# design_main.net
KiCad netlist of a schematic drawn in EAGLE
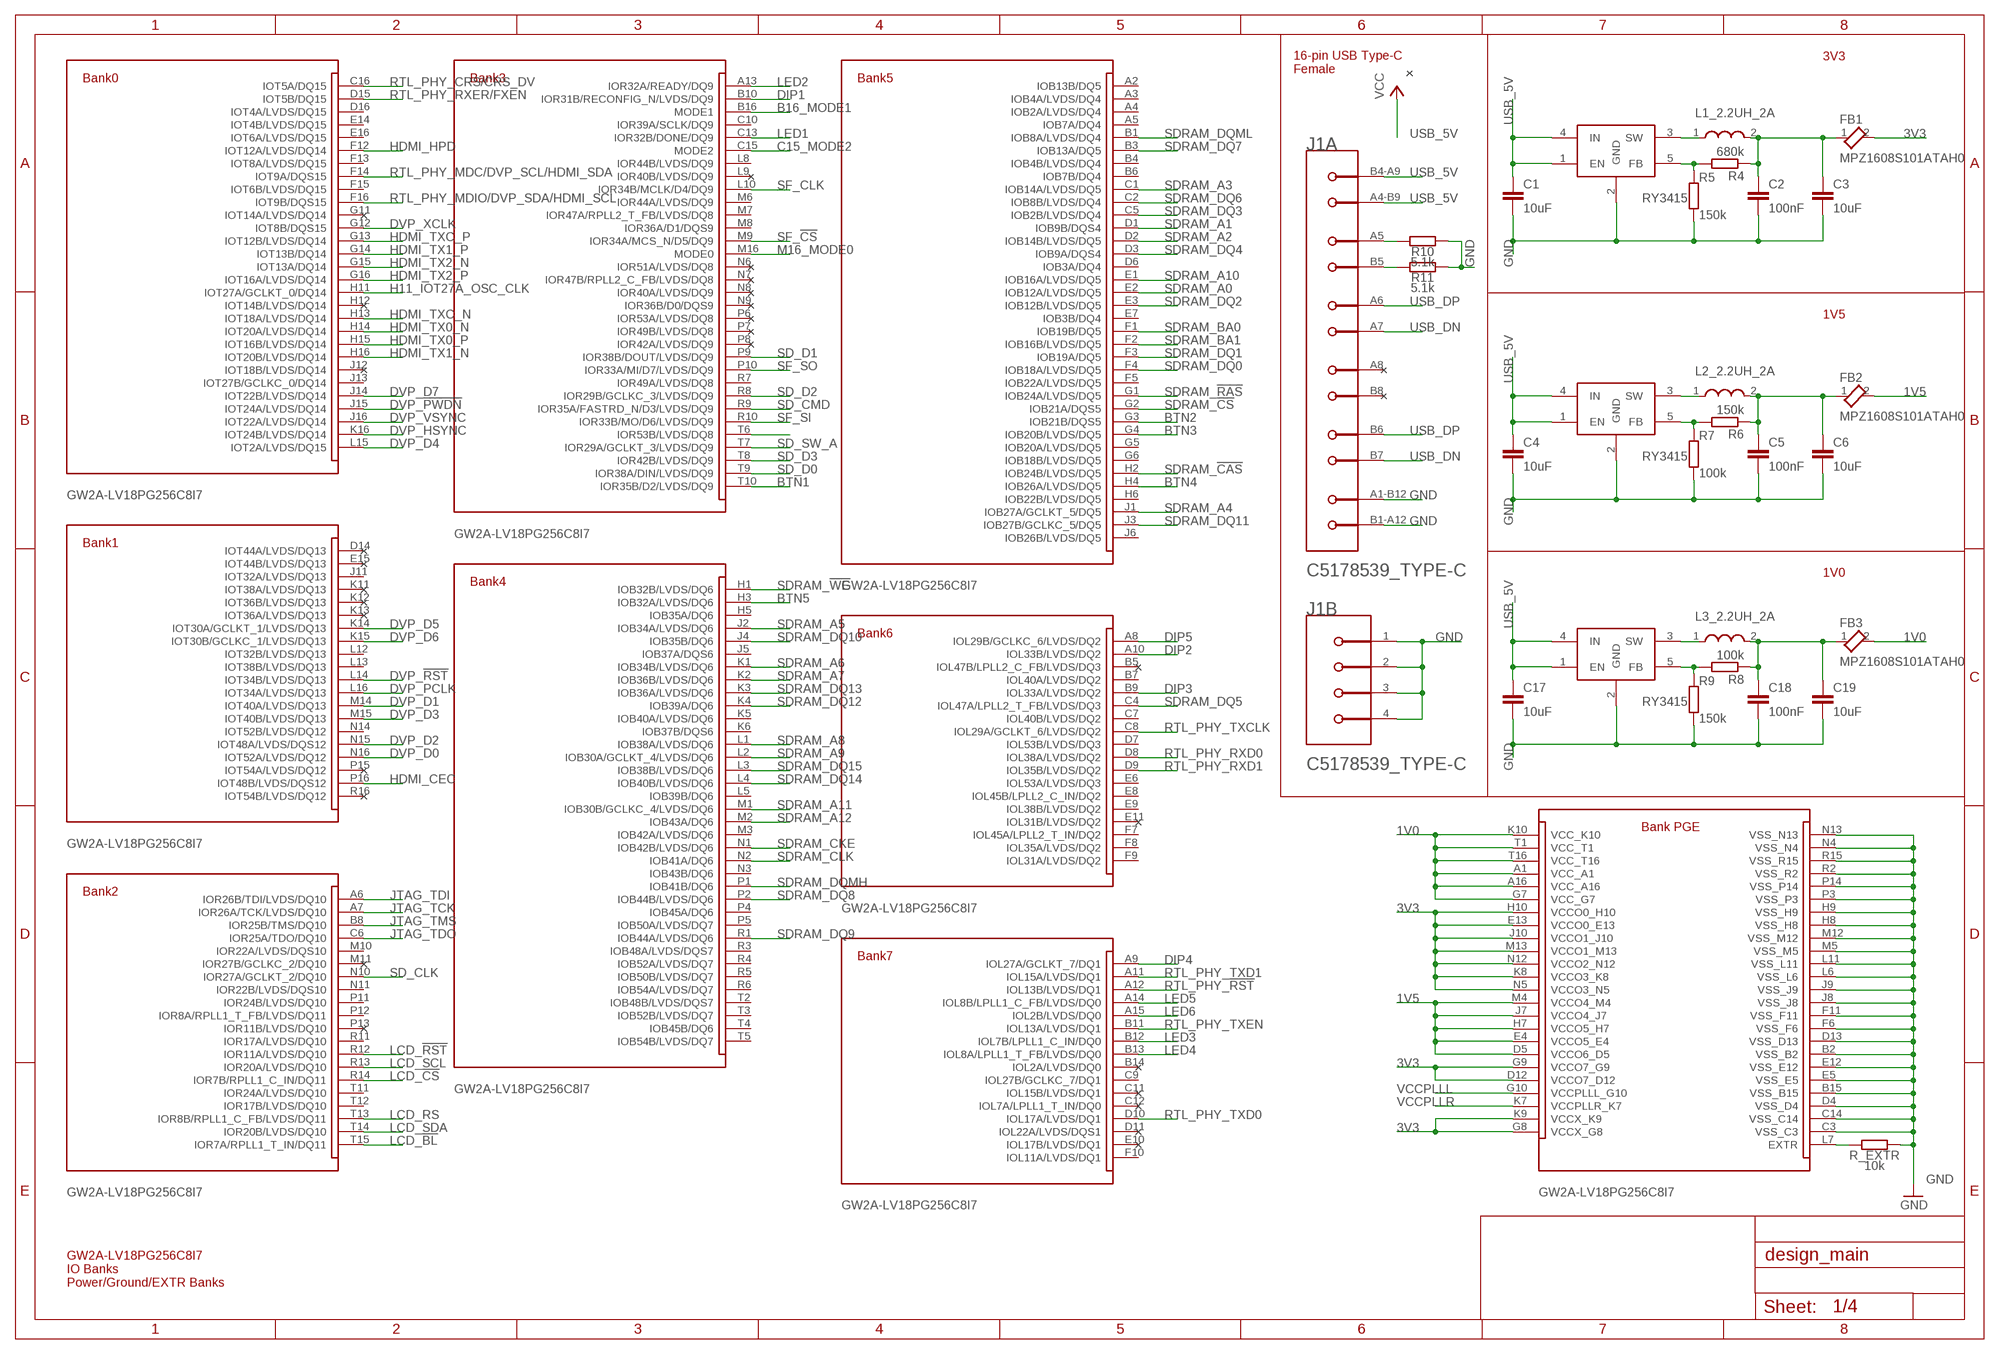
[diagram p0: schematic, sheet 1]
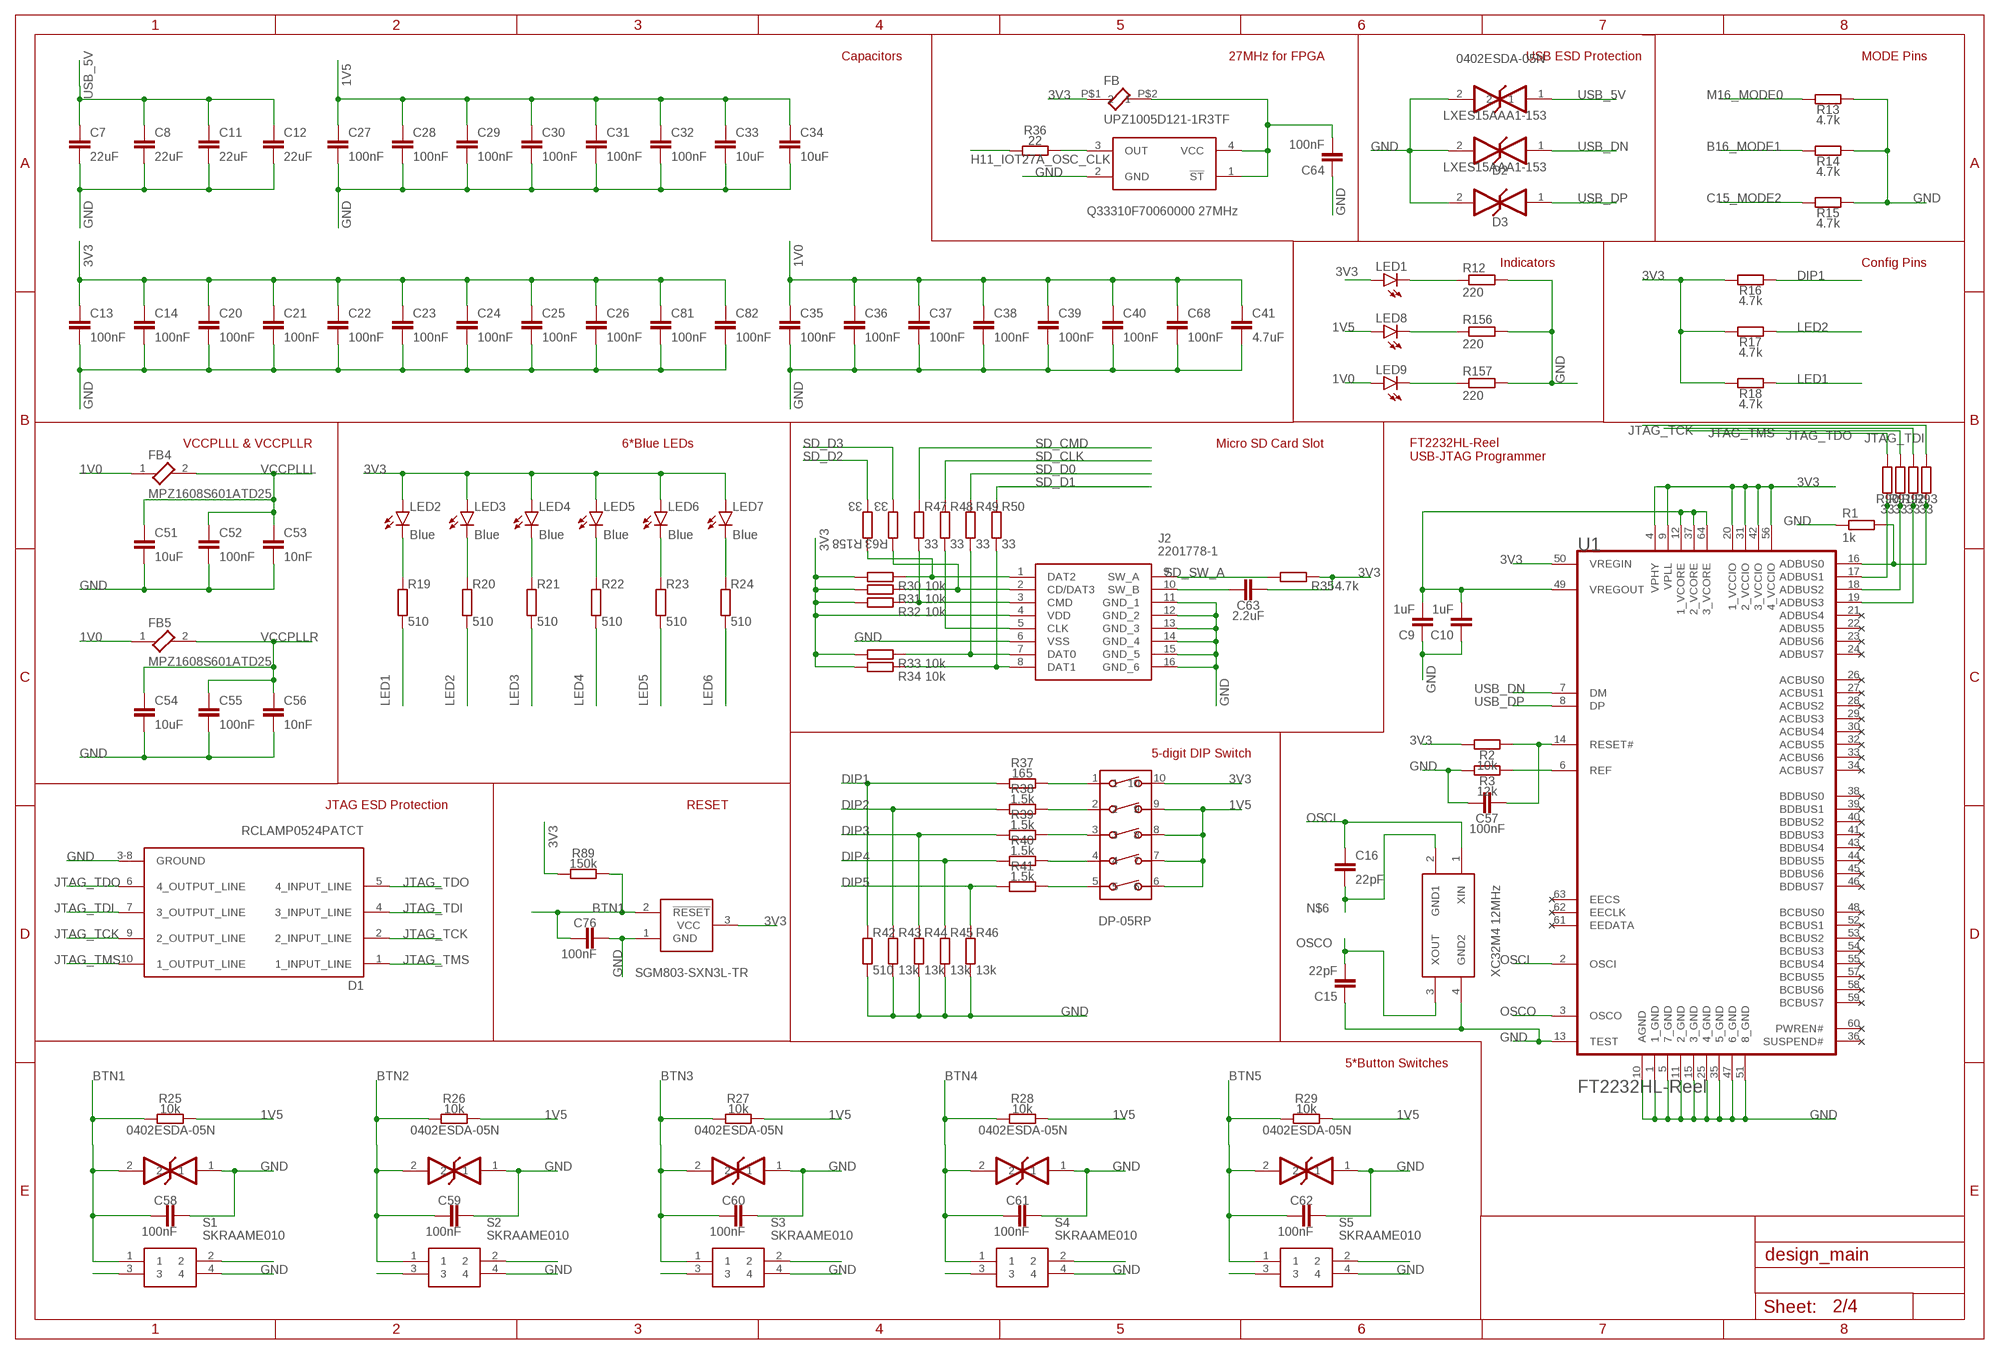
[diagram p1: schematic, sheet 2]
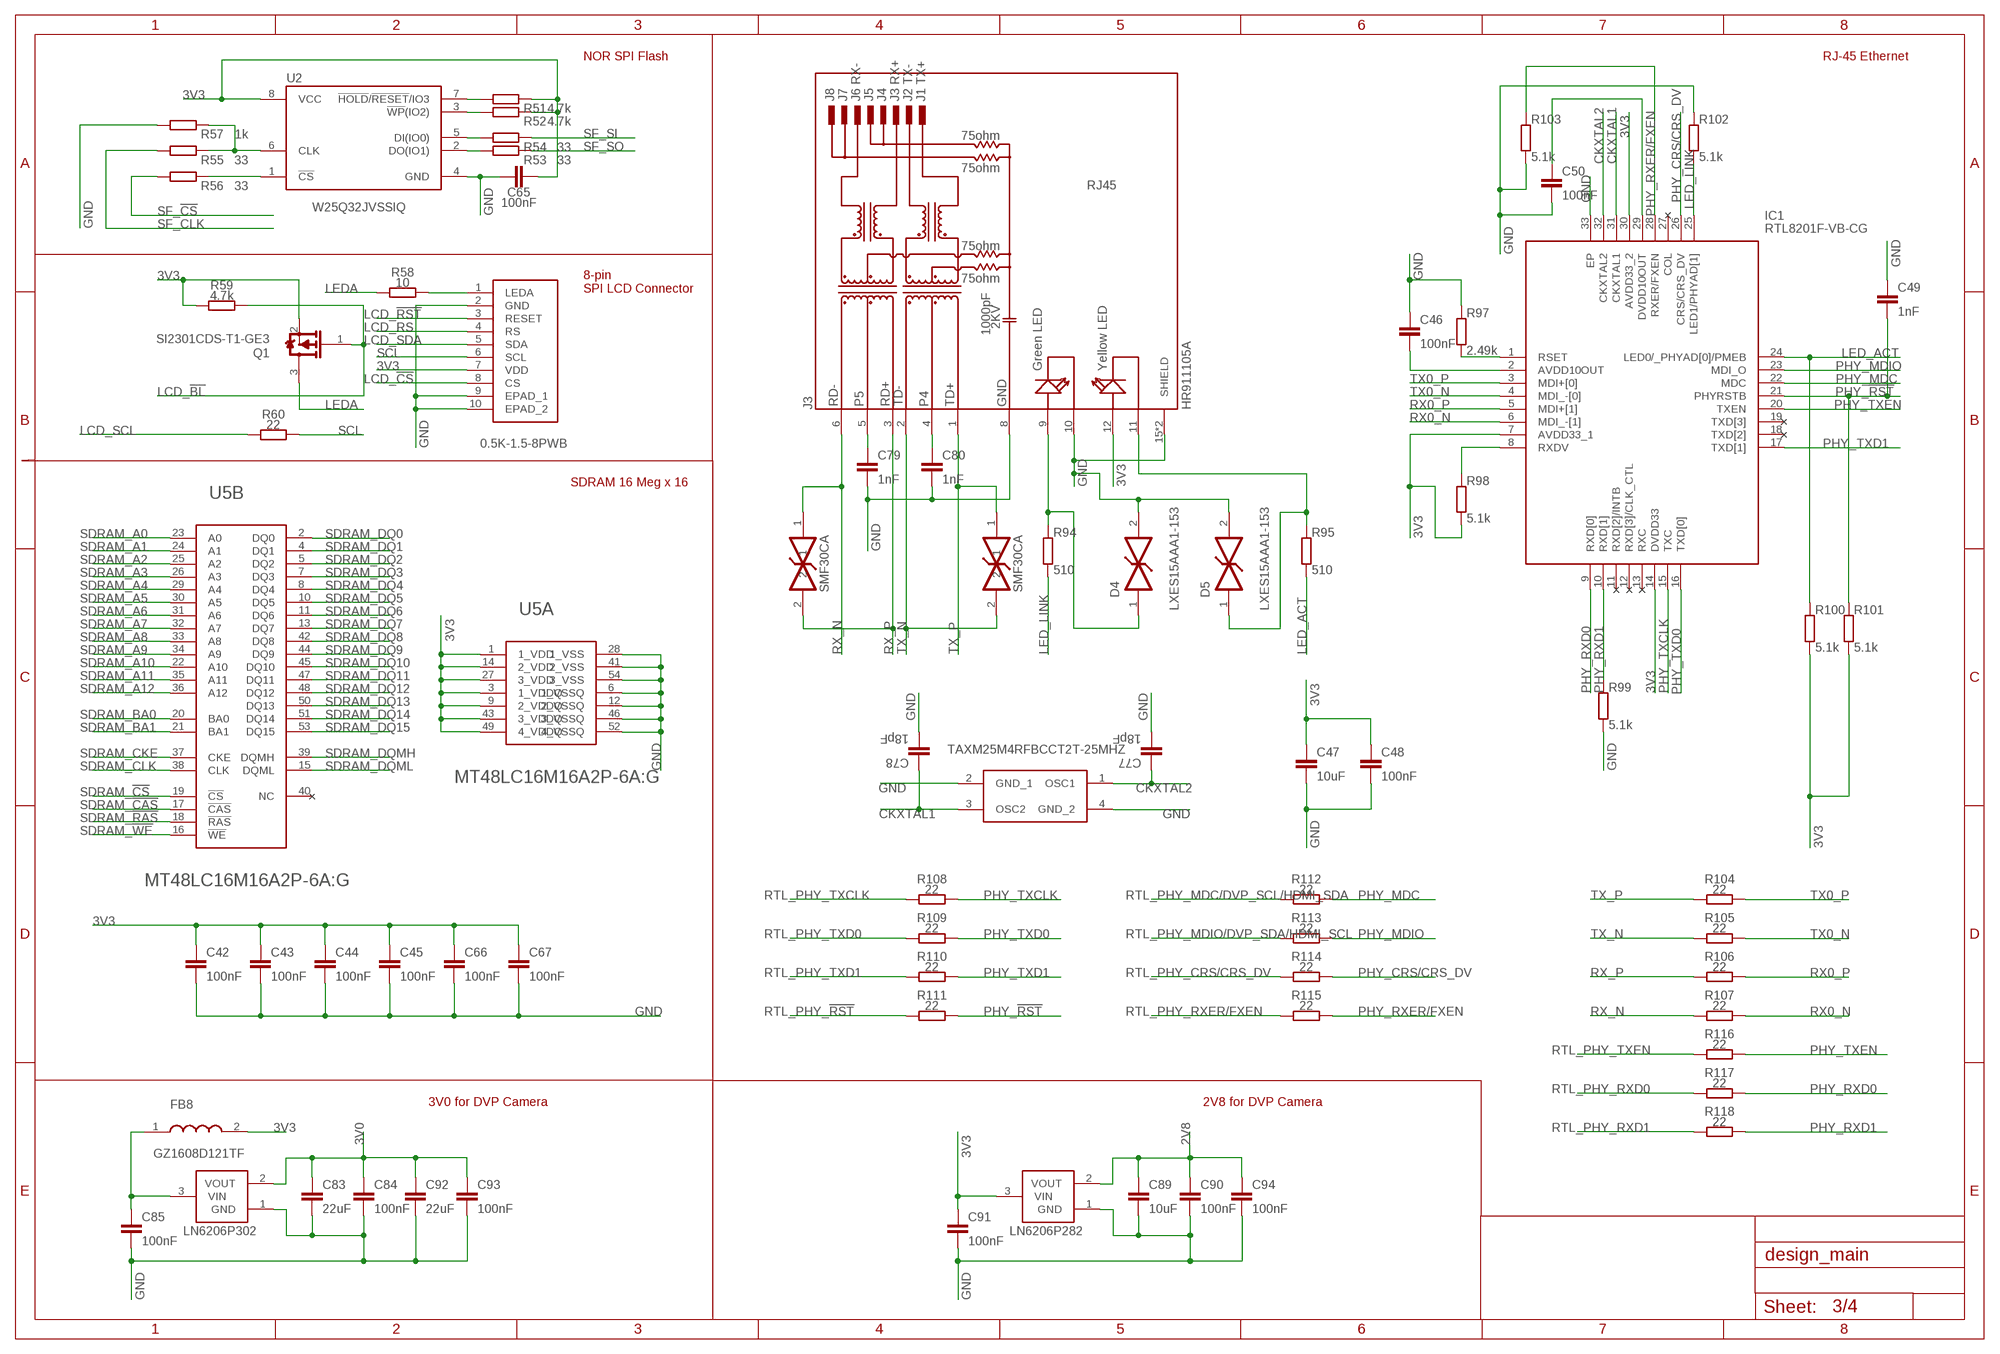
[diagram p2: schematic, sheet 3]
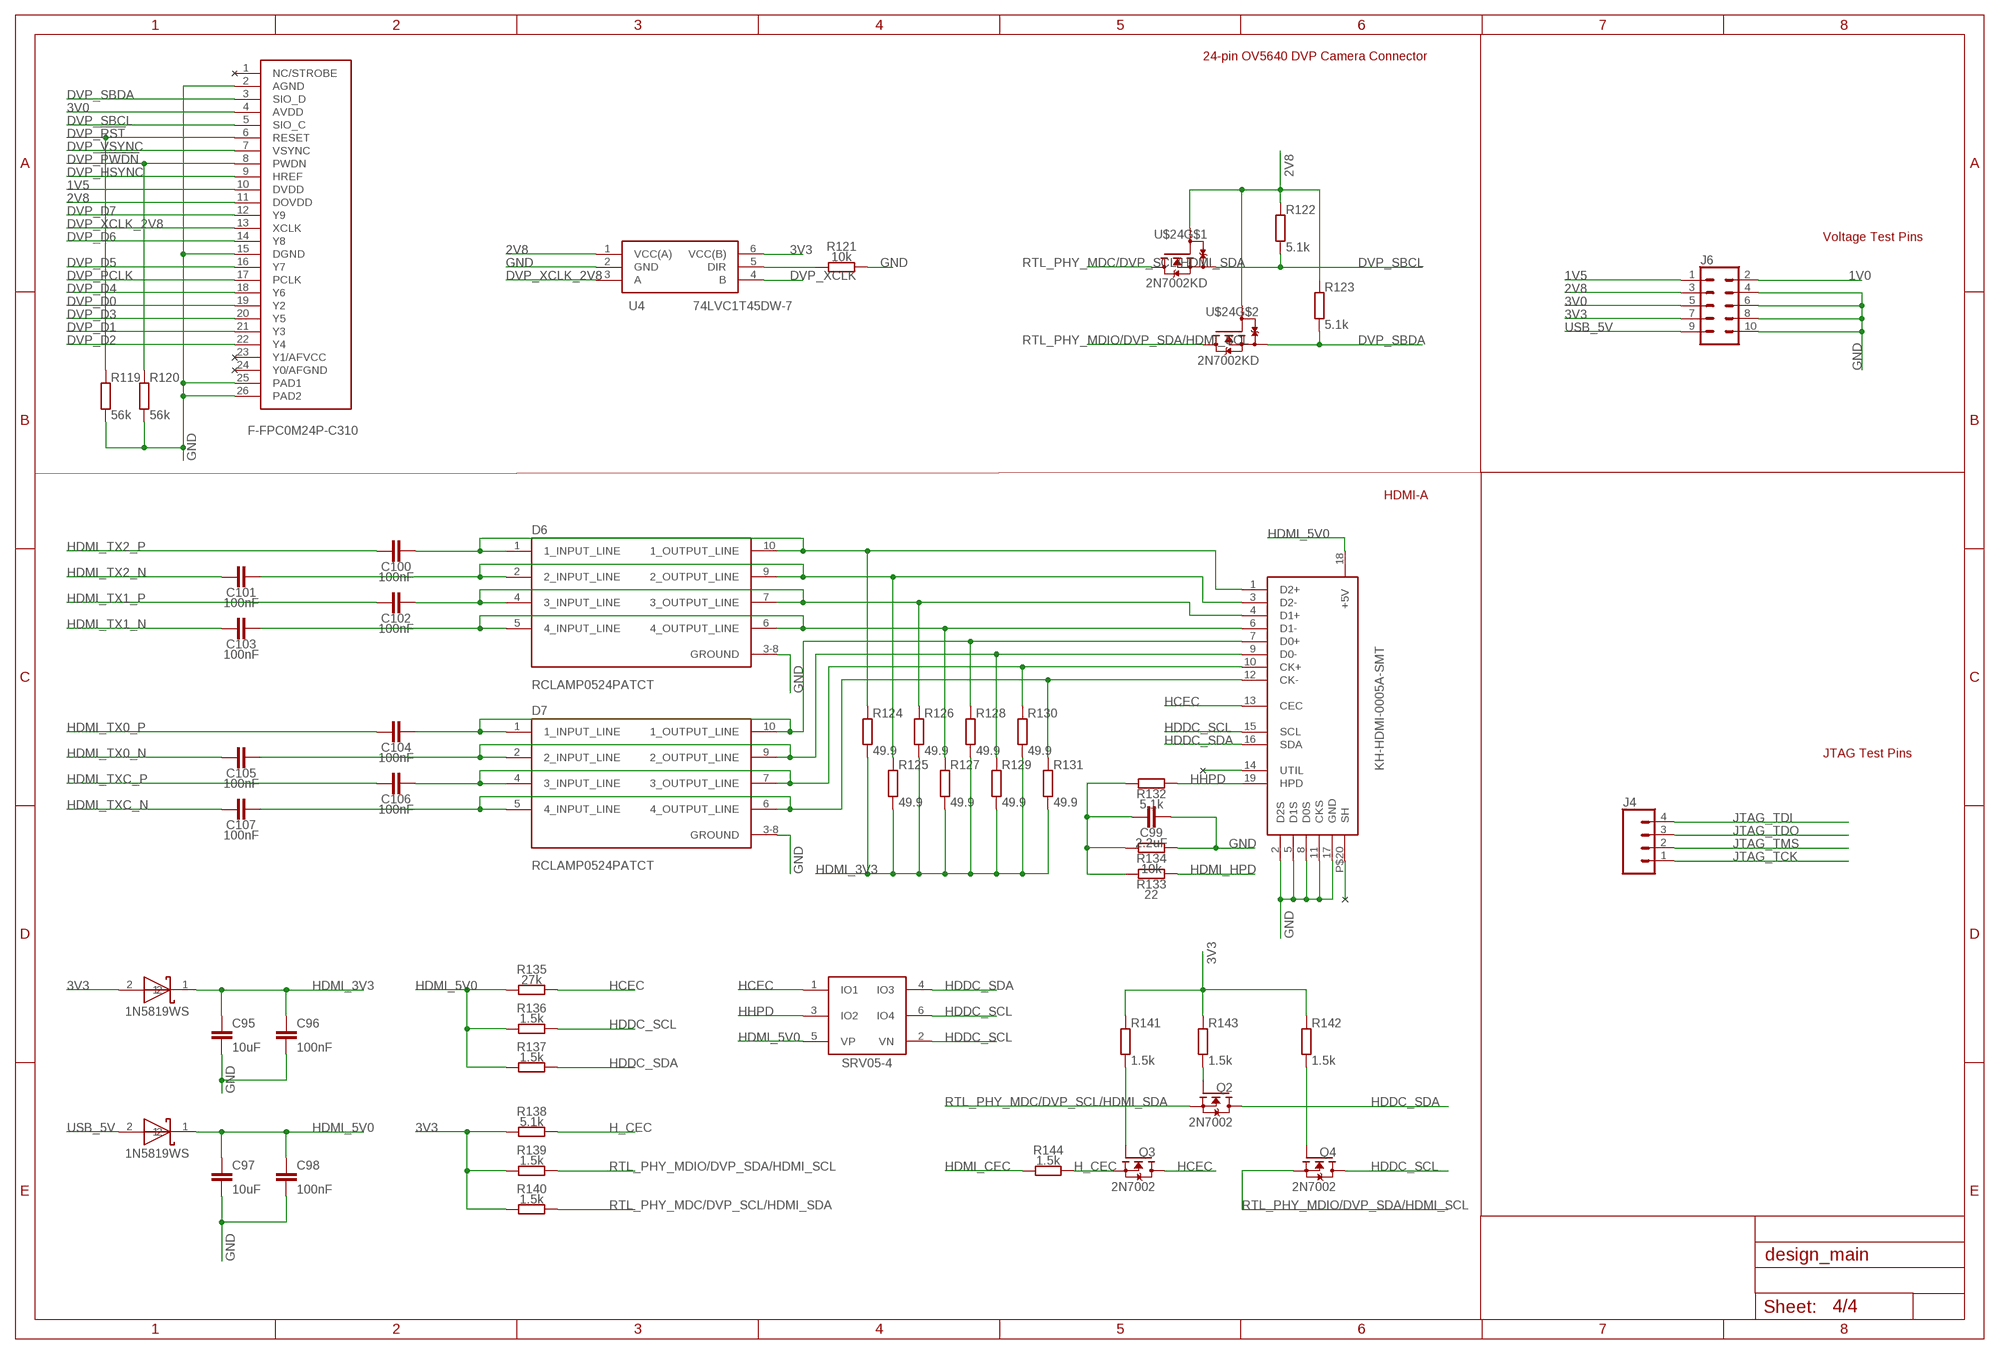
[diagram p3: schematic, sheet 4]

(export (version "E")
  (design (tool "Eeschema 10.0.6"))
  (components
    (comp (ref "C42")
      (value "100nF")
      (footprint "eagle-import:C0805")
      (libsource (lib "eagle-import") (part "C-EUC0805"))
    )
    (comp (ref "C43")
      (value "100nF")
      (footprint "eagle-import:C0805")
      (libsource (lib "eagle-import") (part "C-EUC0805"))
    )
    (comp (ref "C44")
      (value "100nF")
      (footprint "eagle-import:C0805")
      (libsource (lib "eagle-import") (part "C-EUC0805"))
    )
    (comp (ref "C45")
      (value "100nF")
      (footprint "eagle-import:C0805")
      (libsource (lib "eagle-import") (part "C-EUC0805"))
    )
    (comp (ref "C46")
      (value "100nF")
      (footprint "eagle-import:C0805")
      (libsource (lib "eagle-import") (part "C-EUC0805"))
    )
    (comp (ref "C47")
      (value "10uF")
      (footprint "eagle-import:C0805")
      (libsource (lib "eagle-import") (part "C-EUC0805"))
    )
    (comp (ref "C48")
      (value "100nF")
      (footprint "eagle-import:C0805")
      (libsource (lib "eagle-import") (part "C-EUC0805"))
    )
    (comp (ref "C49")
      (value "1nF")
      (footprint "eagle-import:C0805")
      (libsource (lib "eagle-import") (part "C-EUC0805"))
    )
    (comp (ref "C50")
      (value "100nF")
      (footprint "eagle-import:C0805")
      (libsource (lib "eagle-import") (part "C-EUC0805"))
    )
    (comp (ref "C65")
      (value "100nF")
      (footprint "eagle-import:C0805")
      (libsource (lib "eagle-import") (part "C-EUC0805"))
    )
    (comp (ref "C66")
      (value "100nF")
      (footprint "eagle-import:C0805")
      (libsource (lib "eagle-import") (part "C-EUC0805"))
    )
    (comp (ref "C67")
      (value "100nF")
      (footprint "eagle-import:C0805")
      (libsource (lib "eagle-import") (part "C-EUC0805"))
    )
    (comp (ref "C77")
      (value "18pF")
      (footprint "eagle-import:C0805")
      (libsource (lib "eagle-import") (part "C-EUC0805"))
    )
    (comp (ref "C78")
      (value "18pF")
      (footprint "eagle-import:C0805")
      (libsource (lib "eagle-import") (part "C-EUC0805"))
    )
    (comp (ref "C79")
      (value "1nF")
      (footprint "eagle-import:C0805")
      (libsource (lib "eagle-import") (part "C-EUC0805"))
    )
    (comp (ref "C80")
      (value "1nF")
      (footprint "eagle-import:C0805")
      (libsource (lib "eagle-import") (part "C-EUC0805"))
    )
    (comp (ref "C83")
      (value "22uF")
      (footprint "eagle-import:C0805")
      (libsource (lib "eagle-import") (part "C-EUC0805"))
    )
    (comp (ref "C84")
      (value "100nF")
      (footprint "eagle-import:C0805")
      (libsource (lib "eagle-import") (part "C-EUC0805"))
    )
    (comp (ref "C85")
      (value "100nF")
      (footprint "eagle-import:C0805")
      (libsource (lib "eagle-import") (part "C-EUC0805"))
    )
    (comp (ref "C89")
      (value "10uF")
      (footprint "eagle-import:C0805")
      (libsource (lib "eagle-import") (part "C-EUC0805"))
    )
    (comp (ref "C90")
      (value "100nF")
      (footprint "eagle-import:C0805")
      (libsource (lib "eagle-import") (part "C-EUC0805"))
    )
    (comp (ref "C91")
      (value "100nF")
      (footprint "eagle-import:C0805")
      (libsource (lib "eagle-import") (part "C-EUC0805"))
    )
    (comp (ref "C92")
      (value "22uF")
      (footprint "eagle-import:C0805")
      (libsource (lib "eagle-import") (part "C-EUC0805"))
    )
    (comp (ref "C93")
      (value "100nF")
      (footprint "eagle-import:C0805")
      (libsource (lib "eagle-import") (part "C-EUC0805"))
    )
    (comp (ref "C94")
      (value "100nF")
      (footprint "eagle-import:C0805")
      (libsource (lib "eagle-import") (part "C-EUC0805"))
    )
    (comp (ref "D4")
      (value "MURATA_LXES15AAA1-153MURATA_LXES15AAA1-153_0_0")
      (footprint "eagle-import:MURATA_LXES15AAA1-153_0")
      (fields
        (field (name "DIGIKEY_PART_NUMBER") "490-13210-1-ND")
        (field (name "MF") "Murata")
        (field (name "MOUSER_PART_NUMBER") "81-LXES15AAA1-153")
      )
      (libsource (lib "eagle-import") (part "MURATA_LXES15AAA1-153MURATA_LXES15AAA1-153_0_0"))
    )
    (comp (ref "D5")
      (value "MURATA_LXES15AAA1-153MURATA_LXES15AAA1-153_0_0")
      (footprint "eagle-import:MURATA_LXES15AAA1-153_0")
      (fields
        (field (name "DIGIKEY_PART_NUMBER") "490-13210-1-ND")
        (field (name "MF") "Murata")
        (field (name "MOUSER_PART_NUMBER") "81-LXES15AAA1-153")
      )
      (libsource (lib "eagle-import") (part "MURATA_LXES15AAA1-153MURATA_LXES15AAA1-153_0_0"))
    )
    (comp (ref "FB8")
      (value "SUNLORD_GZ1608D121TFSUNLORD_GZ1608D121TF_0_0")
      (footprint "eagle-import:SUNLORD_GZ1608D121TF_0")
      (fields (field (name "MF") "Sunlord") (field (name "MPN") "GZ1608D121TF"))
      (libsource (lib "eagle-import") (part "SUNLORD_GZ1608D121TFSUNLORD_GZ1608D121TF_0_0"))
    )
    (comp (ref "IC1")
      (value "RTL8201F-VB-CG")
      (footprint "eagle-import:QFN50P500X500X100-33N")
      (libsource (lib "eagle-import") (part "RTL8201F-VB-CG"))
    )
    (comp (ref "J3")
      (value "HR911105A")
      (footprint "eagle-import:HANRUN_HR911105A")
      (fields (field (name "MF") "hanrun"))
      (libsource (lib "eagle-import") (part "HR911105A"))
    )
    (comp (ref "Q1")
      (value "VISHAY_SI2301CDS-T1-GE3VISHAY_SI2301CDS-T1-GE3_0_0")
      (footprint "eagle-import:VISHAY_SI2301CDS-T1-GE3_0")
      (fields
        (field (name "DIGIKEY_PART_NUMBER") "SI2301CDS-T1-GE3CT-ND")
        (field (name "MF") "Vishay")
        (field (name "MOUSER_PART_NUMBER") "781-SI2301CDS-T1-GE3")
      )
      (libsource (lib "eagle-import") (part "VISHAY_SI2301CDS-T1-GE3VISHAY_SI2301CDS-T1-GE3_0_0"))
    )
    (comp (ref "R51")
      (value "4.7k")
      (footprint "eagle-import:R0805")
      (libsource (lib "eagle-import") (part "R-EU_R0805"))
    )
    (comp (ref "R52")
      (value "4.7k")
      (footprint "eagle-import:R0805")
      (libsource (lib "eagle-import") (part "R-EU_R0805"))
    )
    (comp (ref "R53")
      (value "33")
      (footprint "eagle-import:R0805")
      (libsource (lib "eagle-import") (part "R-EU_R0805"))
    )
    (comp (ref "R54")
      (value "33")
      (footprint "eagle-import:R0805")
      (libsource (lib "eagle-import") (part "R-EU_R0805"))
    )
    (comp (ref "R55")
      (value "33")
      (footprint "eagle-import:R0805")
      (libsource (lib "eagle-import") (part "R-EU_R0805"))
    )
    (comp (ref "R56")
      (value "33")
      (footprint "eagle-import:R0805")
      (libsource (lib "eagle-import") (part "R-EU_R0805"))
    )
    (comp (ref "R57")
      (value "1k")
      (footprint "eagle-import:R0805")
      (libsource (lib "eagle-import") (part "R-EU_R0805"))
    )
    (comp (ref "R58")
      (value "10")
      (footprint "eagle-import:R0805")
      (libsource (lib "eagle-import") (part "R-EU_R0805"))
    )
    (comp (ref "R59")
      (value "4.7k")
      (footprint "eagle-import:R0805")
      (libsource (lib "eagle-import") (part "R-EU_R0805"))
    )
    (comp (ref "R60")
      (value "22")
      (footprint "eagle-import:R0805")
      (libsource (lib "eagle-import") (part "R-EU_R0805"))
    )
    (comp (ref "R94")
      (value "510")
      (footprint "eagle-import:R0805")
      (libsource (lib "eagle-import") (part "R-EU_R0805"))
    )
    (comp (ref "R95")
      (value "510")
      (footprint "eagle-import:R0805")
      (libsource (lib "eagle-import") (part "R-EU_R0805"))
    )
    (comp (ref "R97")
      (value "2.49k")
      (footprint "eagle-import:R0805")
      (libsource (lib "eagle-import") (part "R-EU_R0805"))
    )
    (comp (ref "R98")
      (value "5.1k")
      (footprint "eagle-import:R0805")
      (libsource (lib "eagle-import") (part "R-EU_R0805"))
    )
    (comp (ref "R99")
      (value "5.1k")
      (footprint "eagle-import:R0805")
      (libsource (lib "eagle-import") (part "R-EU_R0805"))
    )
    (comp (ref "R100")
      (value "5.1k")
      (footprint "eagle-import:R0805")
      (libsource (lib "eagle-import") (part "R-EU_R0805"))
    )
    (comp (ref "R101")
      (value "5.1k")
      (footprint "eagle-import:R0805")
      (libsource (lib "eagle-import") (part "R-EU_R0805"))
    )
    (comp (ref "R102")
      (value "5.1k")
      (footprint "eagle-import:R0805")
      (libsource (lib "eagle-import") (part "R-EU_R0805"))
    )
    (comp (ref "R103")
      (value "5.1k")
      (footprint "eagle-import:R0805")
      (libsource (lib "eagle-import") (part "R-EU_R0805"))
    )
    (comp (ref "R104")
      (value "22")
      (footprint "eagle-import:R0805")
      (libsource (lib "eagle-import") (part "R-EU_R0805"))
    )
    (comp (ref "R105")
      (value "22")
      (footprint "eagle-import:R0805")
      (libsource (lib "eagle-import") (part "R-EU_R0805"))
    )
    (comp (ref "R106")
      (value "22")
      (footprint "eagle-import:R0805")
      (libsource (lib "eagle-import") (part "R-EU_R0805"))
    )
    (comp (ref "R107")
      (value "22")
      (footprint "eagle-import:R0805")
      (libsource (lib "eagle-import") (part "R-EU_R0805"))
    )
    (comp (ref "R108")
      (value "22")
      (footprint "eagle-import:R0805")
      (libsource (lib "eagle-import") (part "R-EU_R0805"))
    )
    (comp (ref "R109")
      (value "22")
      (footprint "eagle-import:R0805")
      (libsource (lib "eagle-import") (part "R-EU_R0805"))
    )
    (comp (ref "R110")
      (value "22")
      (footprint "eagle-import:R0805")
      (libsource (lib "eagle-import") (part "R-EU_R0805"))
    )
    (comp (ref "R111")
      (value "22")
      (footprint "eagle-import:R0805")
      (libsource (lib "eagle-import") (part "R-EU_R0805"))
    )
    (comp (ref "R112")
      (value "22")
      (footprint "eagle-import:R0805")
      (libsource (lib "eagle-import") (part "R-EU_R0805"))
    )
    (comp (ref "R113")
      (value "22")
      (footprint "eagle-import:R0805")
      (libsource (lib "eagle-import") (part "R-EU_R0805"))
    )
    (comp (ref "R114")
      (value "22")
      (footprint "eagle-import:R0805")
      (libsource (lib "eagle-import") (part "R-EU_R0805"))
    )
    (comp (ref "R115")
      (value "22")
      (footprint "eagle-import:R0805")
      (libsource (lib "eagle-import") (part "R-EU_R0805"))
    )
    (comp (ref "R116")
      (value "22")
      (footprint "eagle-import:R0805")
      (libsource (lib "eagle-import") (part "R-EU_R0805"))
    )
    (comp (ref "R117")
      (value "22")
      (footprint "eagle-import:R0805")
      (libsource (lib "eagle-import") (part "R-EU_R0805"))
    )
    (comp (ref "R118")
      (value "22")
      (footprint "eagle-import:R0805")
      (libsource (lib "eagle-import") (part "R-EU_R0805"))
    )
    (comp (ref "U$14")
      (value "0.5K-1.5-8PWB")
      (footprint "eagle-import:0.5K-1.5-8PWB")
      (libsource (lib "eagle-import") (part "0.5K-1.5-8PWB"))
    )
    (comp (ref "U$17")
      (value "TAXM25M4RFBCCT2T-25MHZ")
      (footprint "eagle-import:TAXM25M4RFBCCT2T-25MHZ")
      (libsource (lib "eagle-import") (part "TAXM25M4RFBCCT2T-25MHZ"))
    )
    (comp (ref "U$18")
      (value "SMF30CA")
      (footprint "eagle-import:SMF30CA")
      (libsource (lib "eagle-import") (part "SMF30CA"))
    )
    (comp (ref "U$19")
      (value "SMF30CA")
      (footprint "eagle-import:SMF30CA")
      (libsource (lib "eagle-import") (part "SMF30CA"))
    )
    (comp (ref "U$20")
      (value "LN6206P302")
      (footprint "eagle-import:LN6206P302")
      (libsource (lib "eagle-import") (part "LN6206P302"))
    )
    (comp (ref "U$22")
      (value "LN6206P282")
      (footprint "eagle-import:LN6206P282")
      (libsource (lib "eagle-import") (part "LN6206P282"))
    )
    (comp (ref "U2")
      (value "WINBOND_W25Q32JVSSIQWINBOND_W25Q32JVSSIQ_0_0")
      (footprint "eagle-import:WINBOND_W25Q32JVSSIQ_0")
      (fields
        (field (name "3DS_PART_NUMBER") "521-00004")
        (field (name "DIGIKEY_PART_NUMBER") "W25Q32JVSSIQ-ND")
        (field (name "MF") "Winbond")
      )
      (libsource (lib "eagle-import") (part "WINBOND_W25Q32JVSSIQWINBOND_W25Q32JVSSIQ_0_0"))
    )
    (comp (ref "U5")
      (value "MICRON_MT48LC16M16A2P-6A-GMICRON_MT48LC16M16A2P-6A-G_0_0")
      (footprint "eagle-import:MICRON_MT48LC16M16A2P-6A-G_0")
      (fields
        (field (name "DIGIKEY_PART_NUMBER") "MT48LC16M16A2P-6A:G-ND")
        (field (name "MF") "Micron")
        (field (name "MPN") "MT48LC16M16A2P-6A:G")
      )
      (libsource (lib "eagle-import") (part "MICRON_MT48LC16M16A2P-6A-GMICRON_MT48LC16M16A2P-6A-G_0_0"))
    )
    (comp (ref "C7")
      (value "22uF")
      (footprint "eagle-import:C0805")
      (libsource (lib "eagle-import") (part "C-EUC0805"))
    )
    (comp (ref "C8")
      (value "22uF")
      (footprint "eagle-import:C0805")
      (libsource (lib "eagle-import") (part "C-EUC0805"))
    )
    (comp (ref "C9")
      (value "1uF")
      (footprint "eagle-import:C0805")
      (libsource (lib "eagle-import") (part "C-EUC0805"))
    )
    (comp (ref "C10")
      (value "1uF")
      (footprint "eagle-import:C0805")
      (libsource (lib "eagle-import") (part "C-EUC0805"))
    )
    (comp (ref "C11")
      (value "22uF")
      (footprint "eagle-import:C0805")
      (libsource (lib "eagle-import") (part "C-EUC0805"))
    )
    (comp (ref "C12")
      (value "22uF")
      (footprint "eagle-import:C0805")
      (libsource (lib "eagle-import") (part "C-EUC0805"))
    )
    (comp (ref "C13")
      (value "100nF")
      (footprint "eagle-import:C0805")
      (libsource (lib "eagle-import") (part "C-EUC0805"))
    )
    (comp (ref "C14")
      (value "100nF")
      (footprint "eagle-import:C0805")
      (libsource (lib "eagle-import") (part "C-EUC0805"))
    )
    (comp (ref "C15")
      (value "22pF")
      (footprint "eagle-import:C0805")
      (libsource (lib "eagle-import") (part "C-EUC0805"))
    )
    (comp (ref "C16")
      (value "22pF")
      (footprint "eagle-import:C0805")
      (libsource (lib "eagle-import") (part "C-EUC0805"))
    )
    (comp (ref "C20")
      (value "100nF")
      (footprint "eagle-import:C0805")
      (libsource (lib "eagle-import") (part "C-EUC0805"))
    )
    (comp (ref "C21")
      (value "100nF")
      (footprint "eagle-import:C0805")
      (libsource (lib "eagle-import") (part "C-EUC0805"))
    )
    (comp (ref "C22")
      (value "100nF")
      (footprint "eagle-import:C0805")
      (libsource (lib "eagle-import") (part "C-EUC0805"))
    )
    (comp (ref "C23")
      (value "100nF")
      (footprint "eagle-import:C0805")
      (libsource (lib "eagle-import") (part "C-EUC0805"))
    )
    (comp (ref "C24")
      (value "100nF")
      (footprint "eagle-import:C0805")
      (libsource (lib "eagle-import") (part "C-EUC0805"))
    )
    (comp (ref "C25")
      (value "100nF")
      (footprint "eagle-import:C0805")
      (libsource (lib "eagle-import") (part "C-EUC0805"))
    )
    (comp (ref "C26")
      (value "100nF")
      (footprint "eagle-import:C0805")
      (libsource (lib "eagle-import") (part "C-EUC0805"))
    )
    (comp (ref "C27")
      (value "100nF")
      (footprint "eagle-import:C0805")
      (libsource (lib "eagle-import") (part "C-EUC0805"))
    )
    (comp (ref "C28")
      (value "100nF")
      (footprint "eagle-import:C0805")
      (libsource (lib "eagle-import") (part "C-EUC0805"))
    )
    (comp (ref "C29")
      (value "100nF")
      (footprint "eagle-import:C0805")
      (libsource (lib "eagle-import") (part "C-EUC0805"))
    )
    (comp (ref "C30")
      (value "100nF")
      (footprint "eagle-import:C0805")
      (libsource (lib "eagle-import") (part "C-EUC0805"))
    )
    (comp (ref "C31")
      (value "100nF")
      (footprint "eagle-import:C0805")
      (libsource (lib "eagle-import") (part "C-EUC0805"))
    )
    (comp (ref "C32")
      (value "100nF")
      (footprint "eagle-import:C0805")
      (libsource (lib "eagle-import") (part "C-EUC0805"))
    )
    (comp (ref "C33")
      (value "10uF")
      (footprint "eagle-import:C0805")
      (libsource (lib "eagle-import") (part "C-EUC0805"))
    )
    (comp (ref "C34")
      (value "10uF")
      (footprint "eagle-import:C0805")
      (libsource (lib "eagle-import") (part "C-EUC0805"))
    )
    (comp (ref "C35")
      (value "100nF")
      (footprint "eagle-import:C0805")
      (libsource (lib "eagle-import") (part "C-EUC0805"))
    )
    (comp (ref "C36")
      (value "100nF")
      (footprint "eagle-import:C0805")
      (libsource (lib "eagle-import") (part "C-EUC0805"))
    )
    (comp (ref "C37")
      (value "100nF")
      (footprint "eagle-import:C0805")
      (libsource (lib "eagle-import") (part "C-EUC0805"))
    )
    (comp (ref "C38")
      (value "100nF")
      (footprint "eagle-import:C0805")
      (libsource (lib "eagle-import") (part "C-EUC0805"))
    )
    (comp (ref "C39")
      (value "100nF")
      (footprint "eagle-import:C0805")
      (libsource (lib "eagle-import") (part "C-EUC0805"))
    )
    (comp (ref "C40")
      (value "100nF")
      (footprint "eagle-import:C0805")
      (libsource (lib "eagle-import") (part "C-EUC0805"))
    )
    (comp (ref "C41")
      (value "4.7uF")
      (footprint "eagle-import:C0805")
      (libsource (lib "eagle-import") (part "C-EUC0805"))
    )
    (comp (ref "C51")
      (value "10uF")
      (footprint "eagle-import:C0805")
      (libsource (lib "eagle-import") (part "C-EUC0805"))
    )
    (comp (ref "C52")
      (value "100nF")
      (footprint "eagle-import:C0805")
      (libsource (lib "eagle-import") (part "C-EUC0805"))
    )
    (comp (ref "C53")
      (value "10nF")
      (footprint "eagle-import:C0805")
      (libsource (lib "eagle-import") (part "C-EUC0805"))
    )
    (comp (ref "C54")
      (value "10uF")
      (footprint "eagle-import:C0805")
      (libsource (lib "eagle-import") (part "C-EUC0805"))
    )
    (comp (ref "C55")
      (value "100nF")
      (footprint "eagle-import:C0805")
      (libsource (lib "eagle-import") (part "C-EUC0805"))
    )
    (comp (ref "C56")
      (value "10nF")
      (footprint "eagle-import:C0805")
      (libsource (lib "eagle-import") (part "C-EUC0805"))
    )
    (comp (ref "C57")
      (value "100nF")
      (footprint "eagle-import:C0805")
      (libsource (lib "eagle-import") (part "C-EUC0805"))
    )
    (comp (ref "C58")
      (value "100nF")
      (footprint "eagle-import:C0805")
      (libsource (lib "eagle-import") (part "C-EUC0805"))
    )
    (comp (ref "C59")
      (value "100nF")
      (footprint "eagle-import:C0805")
      (libsource (lib "eagle-import") (part "C-EUC0805"))
    )
    (comp (ref "C60")
      (value "100nF")
      (footprint "eagle-import:C0805")
      (libsource (lib "eagle-import") (part "C-EUC0805"))
    )
    (comp (ref "C61")
      (value "100nF")
      (footprint "eagle-import:C0805")
      (libsource (lib "eagle-import") (part "C-EUC0805"))
    )
    (comp (ref "C62")
      (value "100nF")
      (footprint "eagle-import:C0805")
      (libsource (lib "eagle-import") (part "C-EUC0805"))
    )
    (comp (ref "C63")
      (value "2.2uF")
      (footprint "eagle-import:C0805")
      (libsource (lib "eagle-import") (part "C-EUC0805"))
    )
    (comp (ref "C64")
      (value "100nF")
      (footprint "eagle-import:C0805")
      (libsource (lib "eagle-import") (part "C-EUC0805"))
    )
    (comp (ref "C68")
      (value "100nF")
      (footprint "eagle-import:C0805")
      (libsource (lib "eagle-import") (part "C-EUC0805"))
    )
    (comp (ref "C76")
      (value "100nF")
      (footprint "eagle-import:C0805")
      (libsource (lib "eagle-import") (part "C-EUC0805"))
    )
    (comp (ref "C81")
      (value "100nF")
      (footprint "eagle-import:C0805")
      (libsource (lib "eagle-import") (part "C-EUC0805"))
    )
    (comp (ref "C82")
      (value "100nF")
      (footprint "eagle-import:C0805")
      (libsource (lib "eagle-import") (part "C-EUC0805"))
    )
    (comp (ref "D1")
      (value "SEMTECH_RCLAMP0524PATCTSEMTECH_RCLAMP0524PATCT_0_0")
      (footprint "eagle-import:SEMTECH_RCLAMP0524PATCT_0")
      (fields
        (field (name "DIGIKEY_PART_NUMBER") "RCLAMP0524PACT-ND")
        (field (name "MF") "Semtech")
        (field (name "MOUSER_PART_NUMBER") "947-RCLAMP0524PATCT")
      )
      (libsource (lib "eagle-import") (part "SEMTECH_RCLAMP0524PATCTSEMTECH_RCLAMP0524PATCT_0_0"))
    )
    (comp (ref "D2")
      (value "MURATA_LXES15AAA1-153MURATA_LXES15AAA1-153_0_0")
      (footprint "eagle-import:MURATA_LXES15AAA1-153_0")
      (fields
        (field (name "DIGIKEY_PART_NUMBER") "490-13210-1-ND")
        (field (name "MF") "Murata")
        (field (name "MOUSER_PART_NUMBER") "81-LXES15AAA1-153")
      )
      (libsource (lib "eagle-import") (part "MURATA_LXES15AAA1-153MURATA_LXES15AAA1-153_0_0"))
    )
    (comp (ref "D3")
      (value "MURATA_LXES15AAA1-153MURATA_LXES15AAA1-153_0_0")
      (footprint "eagle-import:MURATA_LXES15AAA1-153_0")
      (fields
        (field (name "DIGIKEY_PART_NUMBER") "490-13210-1-ND")
        (field (name "MF") "Murata")
        (field (name "MOUSER_PART_NUMBER") "81-LXES15AAA1-153")
      )
      (libsource (lib "eagle-import") (part "MURATA_LXES15AAA1-153MURATA_LXES15AAA1-153_0_0"))
    )
    (comp (ref "FB")
      (value "UPZ1005D121-1R3TF")
      (footprint "eagle-import:UPZ1005D121-1R3TF")
      (libsource (lib "eagle-import") (part "UPZ1005D121-1R3TF"))
    )
    (comp (ref "FB4")
      (value "TDK_MPZ1608S601ATD25TDK_MPZ1608S601ATD25_0_0")
      (footprint "eagle-import:TDK_MPZ1608S601ATD25_0")
      (fields
        (field (name "MF") "TDK")
        (field (name "MPN") "MPZ1608S601ATD25")
        (field (name "TOLERANCE") "25%")
      )
      (libsource (lib "eagle-import") (part "TDK_MPZ1608S601ATD25TDK_MPZ1608S601ATD25_0_0"))
    )
    (comp (ref "FB5")
      (value "TDK_MPZ1608S601ATD25TDK_MPZ1608S601ATD25_0_0")
      (footprint "eagle-import:TDK_MPZ1608S601ATD25_0")
      (fields
        (field (name "MF") "TDK")
        (field (name "MPN") "MPZ1608S601ATD25")
        (field (name "TOLERANCE") "25%")
      )
      (libsource (lib "eagle-import") (part "TDK_MPZ1608S601ATD25TDK_MPZ1608S601ATD25_0_0"))
    )
    (comp (ref "J2")
      (value "2201778-1")
      (footprint "eagle-import:22017781")
      (fields (field (name "MOUSER_PART_NUMBER") "571-2201778-1"))
      (libsource (lib "eagle-import") (part "2201778-1"))
    )
    (comp (ref "LED1")
      (value "LEDSML0805")
      (footprint "eagle-import:SML0805")
      (libsource (lib "eagle-import") (part "LEDSML0805"))
    )
    (comp (ref "LED2")
      (value "Blue")
      (footprint "eagle-import:SML0805")
      (libsource (lib "eagle-import") (part "LEDSML0805"))
    )
    (comp (ref "LED3")
      (value "Blue")
      (footprint "eagle-import:SML0805")
      (libsource (lib "eagle-import") (part "LEDSML0805"))
    )
    (comp (ref "LED4")
      (value "Blue")
      (footprint "eagle-import:SML0805")
      (libsource (lib "eagle-import") (part "LEDSML0805"))
    )
    (comp (ref "LED5")
      (value "Blue")
      (footprint "eagle-import:SML0805")
      (libsource (lib "eagle-import") (part "LEDSML0805"))
    )
    (comp (ref "LED6")
      (value "Blue")
      (footprint "eagle-import:SML0805")
      (libsource (lib "eagle-import") (part "LEDSML0805"))
    )
    (comp (ref "LED7")
      (value "Blue")
      (footprint "eagle-import:SML0805")
      (libsource (lib "eagle-import") (part "LEDSML0805"))
    )
    (comp (ref "LED8")
      (value "LEDSML0805")
      (footprint "eagle-import:SML0805")
      (libsource (lib "eagle-import") (part "LEDSML0805"))
    )
    (comp (ref "LED9")
      (value "LEDSML0805")
      (footprint "eagle-import:SML0805")
      (libsource (lib "eagle-import") (part "LEDSML0805"))
    )
    (comp (ref "R1")
      (value "1k")
      (footprint "eagle-import:R0805")
      (libsource (lib "eagle-import") (part "R-EU_R0805"))
    )
    (comp (ref "R2")
      (value "10k")
      (footprint "eagle-import:R0805")
      (libsource (lib "eagle-import") (part "R-EU_R0805"))
    )
    (comp (ref "R3")
      (value "12k")
      (footprint "eagle-import:R0805")
      (libsource (lib "eagle-import") (part "R-EU_R0805"))
    )
    (comp (ref "R12")
      (value "220")
      (footprint "eagle-import:R0805")
      (libsource (lib "eagle-import") (part "R-EU_R0805"))
    )
    (comp (ref "R13")
      (value "4.7k")
      (footprint "eagle-import:R0805")
      (libsource (lib "eagle-import") (part "R-EU_R0805"))
    )
    (comp (ref "R14")
      (value "4.7k")
      (footprint "eagle-import:R0805")
      (libsource (lib "eagle-import") (part "R-EU_R0805"))
    )
    (comp (ref "R15")
      (value "4.7k")
      (footprint "eagle-import:R0805")
      (libsource (lib "eagle-import") (part "R-EU_R0805"))
    )
    (comp (ref "R16")
      (value "4.7k")
      (footprint "eagle-import:R0805")
      (libsource (lib "eagle-import") (part "R-EU_R0805"))
    )
    (comp (ref "R17")
      (value "4.7k")
      (footprint "eagle-import:R0805")
      (libsource (lib "eagle-import") (part "R-EU_R0805"))
    )
    (comp (ref "R18")
      (value "4.7k")
      (footprint "eagle-import:R0805")
      (libsource (lib "eagle-import") (part "R-EU_R0805"))
    )
    (comp (ref "R19")
      (value "510")
      (footprint "eagle-import:R0805")
      (libsource (lib "eagle-import") (part "R-EU_R0805"))
    )
    (comp (ref "R20")
      (value "510")
      (footprint "eagle-import:R0805")
      (libsource (lib "eagle-import") (part "R-EU_R0805"))
    )
    (comp (ref "R21")
      (value "510")
      (footprint "eagle-import:R0805")
      (libsource (lib "eagle-import") (part "R-EU_R0805"))
    )
    (comp (ref "R22")
      (value "510")
      (footprint "eagle-import:R0805")
      (libsource (lib "eagle-import") (part "R-EU_R0805"))
    )
    (comp (ref "R23")
      (value "510")
      (footprint "eagle-import:R0805")
      (libsource (lib "eagle-import") (part "R-EU_R0805"))
    )
    (comp (ref "R24")
      (value "510")
      (footprint "eagle-import:R0805")
      (libsource (lib "eagle-import") (part "R-EU_R0805"))
    )
    (comp (ref "R25")
      (value "10k")
      (footprint "eagle-import:R0805")
      (libsource (lib "eagle-import") (part "R-EU_R0805"))
    )
    (comp (ref "R26")
      (value "10k")
      (footprint "eagle-import:R0805")
      (libsource (lib "eagle-import") (part "R-EU_R0805"))
    )
    (comp (ref "R27")
      (value "10k")
      (footprint "eagle-import:R0805")
      (libsource (lib "eagle-import") (part "R-EU_R0805"))
    )
    (comp (ref "R28")
      (value "10k")
      (footprint "eagle-import:R0805")
      (libsource (lib "eagle-import") (part "R-EU_R0805"))
    )
    (comp (ref "R29")
      (value "10k")
      (footprint "eagle-import:R0805")
      (libsource (lib "eagle-import") (part "R-EU_R0805"))
    )
    (comp (ref "R30")
      (value "10k")
      (footprint "eagle-import:R0805")
      (libsource (lib "eagle-import") (part "R-EU_R0805"))
    )
    (comp (ref "R31")
      (value "10k")
      (footprint "eagle-import:R0805")
      (libsource (lib "eagle-import") (part "R-EU_R0805"))
    )
    (comp (ref "R32")
      (value "10k")
      (footprint "eagle-import:R0805")
      (libsource (lib "eagle-import") (part "R-EU_R0805"))
    )
    (comp (ref "R33")
      (value "10k")
      (footprint "eagle-import:R0805")
      (libsource (lib "eagle-import") (part "R-EU_R0805"))
    )
    (comp (ref "R34")
      (value "10k")
      (footprint "eagle-import:R0805")
      (libsource (lib "eagle-import") (part "R-EU_R0805"))
    )
    (comp (ref "R35")
      (value "4.7k")
      (footprint "eagle-import:R0805")
      (libsource (lib "eagle-import") (part "R-EU_R0805"))
    )
    (comp (ref "R36")
      (value "22")
      (footprint "eagle-import:R0805")
      (libsource (lib "eagle-import") (part "R-EU_R0805"))
    )
    (comp (ref "R37")
      (value "165")
      (footprint "eagle-import:R0805")
      (libsource (lib "eagle-import") (part "R-EU_R0805"))
    )
    (comp (ref "R38")
      (value "1.5k")
      (footprint "eagle-import:R0805")
      (libsource (lib "eagle-import") (part "R-EU_R0805"))
    )
    (comp (ref "R39")
      (value "1.5k")
      (footprint "eagle-import:R0805")
      (libsource (lib "eagle-import") (part "R-EU_R0805"))
    )
    (comp (ref "R40")
      (value "1.5k")
      (footprint "eagle-import:R0805")
      (libsource (lib "eagle-import") (part "R-EU_R0805"))
    )
    (comp (ref "R41")
      (value "1.5k")
      (footprint "eagle-import:R0805")
      (libsource (lib "eagle-import") (part "R-EU_R0805"))
    )
    (comp (ref "R42")
      (value "510")
      (footprint "eagle-import:R0805")
      (libsource (lib "eagle-import") (part "R-EU_R0805"))
    )
    (comp (ref "R43")
      (value "13k")
      (footprint "eagle-import:R0805")
      (libsource (lib "eagle-import") (part "R-EU_R0805"))
    )
    (comp (ref "R44")
      (value "13k")
      (footprint "eagle-import:R0805")
      (libsource (lib "eagle-import") (part "R-EU_R0805"))
    )
    (comp (ref "R45")
      (value "13k")
      (footprint "eagle-import:R0805")
      (libsource (lib "eagle-import") (part "R-EU_R0805"))
    )
    (comp (ref "R46")
      (value "13k")
      (footprint "eagle-import:R0805")
      (libsource (lib "eagle-import") (part "R-EU_R0805"))
    )
    (comp (ref "R47")
      (value "33")
      (footprint "eagle-import:R0805")
      (libsource (lib "eagle-import") (part "R-EU_R0805"))
    )
    (comp (ref "R48")
      (value "33")
      (footprint "eagle-import:R0805")
      (libsource (lib "eagle-import") (part "R-EU_R0805"))
    )
    (comp (ref "R49")
      (value "33")
      (footprint "eagle-import:R0805")
      (libsource (lib "eagle-import") (part "R-EU_R0805"))
    )
    (comp (ref "R50")
      (value "33")
      (footprint "eagle-import:R0805")
      (libsource (lib "eagle-import") (part "R-EU_R0805"))
    )
    (comp (ref "R63")
      (value "33")
      (footprint "eagle-import:R0805")
      (libsource (lib "eagle-import") (part "R-EU_R0805"))
    )
    (comp (ref "R89")
      (value "150k")
      (footprint "eagle-import:R0805")
      (libsource (lib "eagle-import") (part "R-EU_R0805"))
    )
    (comp (ref "R90")
      (value "33")
      (footprint "eagle-import:R0805")
      (libsource (lib "eagle-import") (part "R-EU_R0805"))
    )
    (comp (ref "R91")
      (value "33")
      (footprint "eagle-import:R0805")
      (libsource (lib "eagle-import") (part "R-EU_R0805"))
    )
    (comp (ref "R92")
      (value "33")
      (footprint "eagle-import:R0805")
      (libsource (lib "eagle-import") (part "R-EU_R0805"))
    )
    (comp (ref "R93")
      (value "33")
      (footprint "eagle-import:R0805")
      (libsource (lib "eagle-import") (part "R-EU_R0805"))
    )
    (comp (ref "R156")
      (value "220")
      (footprint "eagle-import:R0805")
      (libsource (lib "eagle-import") (part "R-EU_R0805"))
    )
    (comp (ref "R157")
      (value "220")
      (footprint "eagle-import:R0805")
      (libsource (lib "eagle-import") (part "R-EU_R0805"))
    )
    (comp (ref "R158")
      (value "33")
      (footprint "eagle-import:R0805")
      (libsource (lib "eagle-import") (part "R-EU_R0805"))
    )
    (comp (ref "S1")
      (value "SKRAAME010")
      (footprint "eagle-import:SKRAAME010")
      (fields (field (name "MOUSER_PART_NUMBER") "688-SKRAAME010"))
      (libsource (lib "eagle-import") (part "SKRAAME010"))
    )
    (comp (ref "S2")
      (value "SKRAAME010")
      (footprint "eagle-import:SKRAAME010")
      (fields (field (name "MOUSER_PART_NUMBER") "688-SKRAAME010"))
      (libsource (lib "eagle-import") (part "SKRAAME010"))
    )
    (comp (ref "S3")
      (value "SKRAAME010")
      (footprint "eagle-import:SKRAAME010")
      (fields (field (name "MOUSER_PART_NUMBER") "688-SKRAAME010"))
      (libsource (lib "eagle-import") (part "SKRAAME010"))
    )
    (comp (ref "S4")
      (value "SKRAAME010")
      (footprint "eagle-import:SKRAAME010")
      (fields (field (name "MOUSER_PART_NUMBER") "688-SKRAAME010"))
      (libsource (lib "eagle-import") (part "SKRAAME010"))
    )
    (comp (ref "S5")
      (value "SKRAAME010")
      (footprint "eagle-import:SKRAAME010")
      (fields (field (name "MOUSER_PART_NUMBER") "688-SKRAAME010"))
      (libsource (lib "eagle-import") (part "SKRAAME010"))
    )
    (comp (ref "U$2")
      (value "XC32M4-12MHZ")
      (footprint "eagle-import:XC32M4-12MHZ")
      (libsource (lib "eagle-import") (part "XC32M4-12MHZ"))
    )
    (comp (ref "U$6")
      (value "0402ESDA-05N")
      (footprint "eagle-import:0402ESDA-05N")
      (libsource (lib "eagle-import") (part "0402ESDA-05N"))
    )
    (comp (ref "U$7")
      (value "0402ESDA-05N")
      (footprint "eagle-import:0402ESDA-05N")
      (libsource (lib "eagle-import") (part "0402ESDA-05N"))
    )
    (comp (ref "U$8")
      (value "0402ESDA-05N")
      (footprint "eagle-import:0402ESDA-05N")
      (libsource (lib "eagle-import") (part "0402ESDA-05N"))
    )
    (comp (ref "U$9")
      (value "0402ESDA-05N")
      (footprint "eagle-import:0402ESDA-05N")
      (libsource (lib "eagle-import") (part "0402ESDA-05N"))
    )
    (comp (ref "U$10")
      (value "0402ESDA-05N")
      (footprint "eagle-import:0402ESDA-05N")
      (libsource (lib "eagle-import") (part "0402ESDA-05N"))
    )
    (comp (ref "U$11")
      (value "0402ESDA-05N")
      (footprint "eagle-import:0402ESDA-05N")
      (libsource (lib "eagle-import") (part "0402ESDA-05N"))
    )
    (comp (ref "U$13")
      (value "DP-05RP")
      (footprint "eagle-import:DP-05RP")
      (libsource (lib "eagle-import") (part "DP-05RP"))
    )
    (comp (ref "U$15")
      (value "Q33310F70060000-27MHZ")
      (footprint "eagle-import:Q33310F70060000-27MHZ")
      (libsource (lib "eagle-import") (part "Q33310F70060000-27MHZ"))
    )
    (comp (ref "U$16")
      (value "SGM803-SXN3L-TR")
      (footprint "eagle-import:SGM803-SXN3L-TR")
      (libsource (lib "eagle-import") (part "SGM803-SXN3L-TR"))
    )
    (comp (ref "U1")
      (value "FTDI_FT2232HL-REELFTDI_FT2232HL-REEL_0_0")
      (footprint "eagle-import:FTDI_FT2232HL-REEL_0")
      (fields (field (name "MF") "FTDI") (field (name "MPN") "FT2232HL-Reel"))
      (libsource (lib "eagle-import") (part "FTDI_FT2232HL-REELFTDI_FT2232HL-REEL_0_0"))
    )
    (comp (ref "C95")
      (value "10uF")
      (footprint "eagle-import:C0805")
      (libsource (lib "eagle-import") (part "C-EUC0805"))
    )
    (comp (ref "C96")
      (value "100nF")
      (footprint "eagle-import:C0805")
      (libsource (lib "eagle-import") (part "C-EUC0805"))
    )
    (comp (ref "C97")
      (value "10uF")
      (footprint "eagle-import:C0805")
      (libsource (lib "eagle-import") (part "C-EUC0805"))
    )
    (comp (ref "C98")
      (value "100nF")
      (footprint "eagle-import:C0805")
      (libsource (lib "eagle-import") (part "C-EUC0805"))
    )
    (comp (ref "C99")
      (value "2.2uF")
      (footprint "eagle-import:C0805")
      (libsource (lib "eagle-import") (part "C-EUC0805"))
    )
    (comp (ref "C100")
      (value "100nF")
      (footprint "eagle-import:C0805")
      (libsource (lib "eagle-import") (part "C-EUC0805"))
    )
    (comp (ref "C101")
      (value "100nF")
      (footprint "eagle-import:C0805")
      (libsource (lib "eagle-import") (part "C-EUC0805"))
    )
    (comp (ref "C102")
      (value "100nF")
      (footprint "eagle-import:C0805")
      (libsource (lib "eagle-import") (part "C-EUC0805"))
    )
    (comp (ref "C103")
      (value "100nF")
      (footprint "eagle-import:C0805")
      (libsource (lib "eagle-import") (part "C-EUC0805"))
    )
    (comp (ref "C104")
      (value "100nF")
      (footprint "eagle-import:C0805")
      (libsource (lib "eagle-import") (part "C-EUC0805"))
    )
    (comp (ref "C105")
      (value "100nF")
      (footprint "eagle-import:C0805")
      (libsource (lib "eagle-import") (part "C-EUC0805"))
    )
    (comp (ref "C106")
      (value "100nF")
      (footprint "eagle-import:C0805")
      (libsource (lib "eagle-import") (part "C-EUC0805"))
    )
    (comp (ref "C107")
      (value "100nF")
      (footprint "eagle-import:C0805")
      (libsource (lib "eagle-import") (part "C-EUC0805"))
    )
    (comp (ref "D6")
      (value "SEMTECH_RCLAMP0524PATCTSEMTECH_RCLAMP0524PATCT_0_0")
      (footprint "eagle-import:SEMTECH_RCLAMP0524PATCT_0")
      (fields
        (field (name "DIGIKEY_PART_NUMBER") "RCLAMP0524PACT-ND")
        (field (name "MF") "Semtech")
        (field (name "MOUSER_PART_NUMBER") "947-RCLAMP0524PATCT")
      )
      (libsource (lib "eagle-import") (part "SEMTECH_RCLAMP0524PATCTSEMTECH_RCLAMP0524PATCT_0_0"))
    )
    (comp (ref "D7")
      (value "SEMTECH_RCLAMP0524PATCTSEMTECH_RCLAMP0524PATCT_0_0")
      (footprint "eagle-import:SEMTECH_RCLAMP0524PATCT_0")
      (fields
        (field (name "DIGIKEY_PART_NUMBER") "RCLAMP0524PACT-ND")
        (field (name "MF") "Semtech")
        (field (name "MOUSER_PART_NUMBER") "947-RCLAMP0524PATCT")
      )
      (libsource (lib "eagle-import") (part "SEMTECH_RCLAMP0524PATCTSEMTECH_RCLAMP0524PATCT_0_0"))
    )
    (comp (ref "J4")
      (value "CONN_04PTH")
      (footprint "eagle-import:1X04")
      (libsource (lib "eagle-import") (part "CONN_04PTH"))
    )
    (comp (ref "J6")
      (value "CONN_05X2PTH")
      (footprint "eagle-import:2X5")
      (libsource (lib "eagle-import") (part "CONN_05X2PTH"))
    )
    (comp (ref "Q2")
      (value "2N7002")
      (footprint "eagle-import:SOT95P240X111-3N")
      (fields (field (name "MF") "Diotec Semiconductor"))
      (libsource (lib "eagle-import") (part "2N7002"))
    )
    (comp (ref "Q3")
      (value "2N7002")
      (footprint "eagle-import:SOT95P240X111-3N")
      (fields (field (name "MF") "Diotec Semiconductor"))
      (libsource (lib "eagle-import") (part "2N7002"))
    )
    (comp (ref "Q4")
      (value "2N7002")
      (footprint "eagle-import:SOT95P240X111-3N")
      (fields (field (name "MF") "Diotec Semiconductor"))
      (libsource (lib "eagle-import") (part "2N7002"))
    )
    (comp (ref "R119")
      (value "56k")
      (footprint "eagle-import:R0805")
      (libsource (lib "eagle-import") (part "R-EU_R0805"))
    )
    (comp (ref "R120")
      (value "56k")
      (footprint "eagle-import:R0805")
      (libsource (lib "eagle-import") (part "R-EU_R0805"))
    )
    (comp (ref "R121")
      (value "10k")
      (footprint "eagle-import:R0805")
      (libsource (lib "eagle-import") (part "R-EU_R0805"))
    )
    (comp (ref "R122")
      (value "5.1k")
      (footprint "eagle-import:R0805")
      (libsource (lib "eagle-import") (part "R-EU_R0805"))
    )
    (comp (ref "R123")
      (value "5.1k")
      (footprint "eagle-import:R0805")
      (libsource (lib "eagle-import") (part "R-EU_R0805"))
    )
    (comp (ref "R124")
      (value "49.9")
      (footprint "eagle-import:R0805")
      (libsource (lib "eagle-import") (part "R-EU_R0805"))
    )
    (comp (ref "R125")
      (value "49.9")
      (footprint "eagle-import:R0805")
      (libsource (lib "eagle-import") (part "R-EU_R0805"))
    )
    (comp (ref "R126")
      (value "49.9")
      (footprint "eagle-import:R0805")
      (libsource (lib "eagle-import") (part "R-EU_R0805"))
    )
    (comp (ref "R127")
      (value "49.9")
      (footprint "eagle-import:R0805")
      (libsource (lib "eagle-import") (part "R-EU_R0805"))
    )
    (comp (ref "R128")
      (value "49.9")
      (footprint "eagle-import:R0805")
      (libsource (lib "eagle-import") (part "R-EU_R0805"))
    )
    (comp (ref "R129")
      (value "49.9")
      (footprint "eagle-import:R0805")
      (libsource (lib "eagle-import") (part "R-EU_R0805"))
    )
    (comp (ref "R130")
      (value "49.9")
      (footprint "eagle-import:R0805")
      (libsource (lib "eagle-import") (part "R-EU_R0805"))
    )
    (comp (ref "R131")
      (value "49.9")
      (footprint "eagle-import:R0805")
      (libsource (lib "eagle-import") (part "R-EU_R0805"))
    )
    (comp (ref "R132")
      (value "5.1k")
      (footprint "eagle-import:R0805")
      (libsource (lib "eagle-import") (part "R-EU_R0805"))
    )
    (comp (ref "R133")
      (value "22")
      (footprint "eagle-import:R0805")
      (libsource (lib "eagle-import") (part "R-EU_R0805"))
    )
    (comp (ref "R134")
      (value "10k")
      (footprint "eagle-import:R0805")
      (libsource (lib "eagle-import") (part "R-EU_R0805"))
    )
    (comp (ref "R135")
      (value "27k")
      (footprint "eagle-import:R0805")
      (libsource (lib "eagle-import") (part "R-EU_R0805"))
    )
    (comp (ref "R136")
      (value "1.5k")
      (footprint "eagle-import:R0805")
      (libsource (lib "eagle-import") (part "R-EU_R0805"))
    )
    (comp (ref "R137")
      (value "1.5k")
      (footprint "eagle-import:R0805")
      (libsource (lib "eagle-import") (part "R-EU_R0805"))
    )
    (comp (ref "R138")
      (value "5.1k")
      (footprint "eagle-import:R0805")
      (libsource (lib "eagle-import") (part "R-EU_R0805"))
    )
    (comp (ref "R139")
      (value "1.5k")
      (footprint "eagle-import:R0805")
      (libsource (lib "eagle-import") (part "R-EU_R0805"))
    )
    (comp (ref "R140")
      (value "1.5k")
      (footprint "eagle-import:R0805")
      (libsource (lib "eagle-import") (part "R-EU_R0805"))
    )
    (comp (ref "R141")
      (value "1.5k")
      (footprint "eagle-import:R0805")
      (libsource (lib "eagle-import") (part "R-EU_R0805"))
    )
    (comp (ref "R142")
      (value "1.5k")
      (footprint "eagle-import:R0805")
      (libsource (lib "eagle-import") (part "R-EU_R0805"))
    )
    (comp (ref "R143")
      (value "1.5k")
      (footprint "eagle-import:R0805")
      (libsource (lib "eagle-import") (part "R-EU_R0805"))
    )
    (comp (ref "R144")
      (value "1.5k")
      (footprint "eagle-import:R0805")
      (libsource (lib "eagle-import") (part "R-EU_R0805"))
    )
    (comp (ref "U$23")
      (value "F-FPC0M24P-C310")
      (footprint "eagle-import:F-FPC0M24P-C310")
      (libsource (lib "eagle-import") (part "F-FPC0M24P-C310"))
    )
    (comp (ref "U$24")
      (value "2N7002KD")
      (footprint "eagle-import:2N7002KD")
      (libsource (lib "eagle-import") (part "2N7002KD"))
    )
    (comp (ref "U$25")
      (value "1N5819WS")
      (footprint "eagle-import:1N5819WS")
      (libsource (lib "eagle-import") (part "1N5819WS"))
    )
    (comp (ref "U$26")
      (value "1N5819WS")
      (footprint "eagle-import:1N5819WS")
      (libsource (lib "eagle-import") (part "1N5819WS"))
    )
    (comp (ref "U$27")
      (value "KH-HDMI-0005A-SMT")
      (footprint "eagle-import:KH-HDMI-0005A-SMT")
      (libsource (lib "eagle-import") (part "KH-HDMI-0005A-SMT"))
    )
    (comp (ref "U$28")
      (value "SRV05-4")
      (footprint "eagle-import:SRV05-4")
      (libsource (lib "eagle-import") (part "SRV05-4"))
    )
    (comp (ref "U4")
      (value "74LVC1T45DW-7")
      (footprint "eagle-import:SOT65P210X110-6N")
      (fields (field (name "MOUSER_PART_NUMBER") "621-74LVC1T45DW-7"))
      (libsource (lib "eagle-import") (part "74LVC1T45DW-7"))
    )
    (comp (ref "C1")
      (value "10uF")
      (footprint "eagle-import:C0805")
      (libsource (lib "eagle-import") (part "C-EUC0805"))
    )
    (comp (ref "C2")
      (value "100nF")
      (footprint "eagle-import:C0805")
      (libsource (lib "eagle-import") (part "C-EUC0805"))
    )
    (comp (ref "C3")
      (value "10uF")
      (footprint "eagle-import:C0805")
      (libsource (lib "eagle-import") (part "C-EUC0805"))
    )
    (comp (ref "C4")
      (value "10uF")
      (footprint "eagle-import:C0805")
      (libsource (lib "eagle-import") (part "C-EUC0805"))
    )
    (comp (ref "C5")
      (value "100nF")
      (footprint "eagle-import:C0805")
      (libsource (lib "eagle-import") (part "C-EUC0805"))
    )
    (comp (ref "C6")
      (value "10uF")
      (footprint "eagle-import:C0805")
      (libsource (lib "eagle-import") (part "C-EUC0805"))
    )
    (comp (ref "C17")
      (value "10uF")
      (footprint "eagle-import:C0805")
      (libsource (lib "eagle-import") (part "C-EUC0805"))
    )
    (comp (ref "C18")
      (value "100nF")
      (footprint "eagle-import:C0805")
      (libsource (lib "eagle-import") (part "C-EUC0805"))
    )
    (comp (ref "C19")
      (value "10uF")
      (footprint "eagle-import:C0805")
      (libsource (lib "eagle-import") (part "C-EUC0805"))
    )
    (comp (ref "FB1")
      (value "TDK_MPZ1608S101ATAH0TDK_MPZ1608S101ATAH0_0_0")
      (footprint "eagle-import:TDK_MPZ1608S101ATAH0_0")
      (fields
        (field (name "DIGIKEY_PART_NUMBER") "445-1564-1-ND")
        (field (name "MF") "TDK")
        (field (name "MOUSER_PART_NUMBER") "810-MPZ1608S101ATAH0")
      )
      (libsource (lib "eagle-import") (part "TDK_MPZ1608S101ATAH0TDK_MPZ1608S101ATAH0_0_0"))
    )
    (comp (ref "FB2")
      (value "TDK_MPZ1608S101ATAH0TDK_MPZ1608S101ATAH0_0_0")
      (footprint "eagle-import:TDK_MPZ1608S101ATAH0_0")
      (fields
        (field (name "DIGIKEY_PART_NUMBER") "445-1564-1-ND")
        (field (name "MF") "TDK")
        (field (name "MOUSER_PART_NUMBER") "810-MPZ1608S101ATAH0")
      )
      (libsource (lib "eagle-import") (part "TDK_MPZ1608S101ATAH0TDK_MPZ1608S101ATAH0_0_0"))
    )
    (comp (ref "FB3")
      (value "TDK_MPZ1608S101ATAH0TDK_MPZ1608S101ATAH0_0_0")
      (footprint "eagle-import:TDK_MPZ1608S101ATAH0_0")
      (fields
        (field (name "DIGIKEY_PART_NUMBER") "445-1564-1-ND")
        (field (name "MF") "TDK")
        (field (name "MOUSER_PART_NUMBER") "810-MPZ1608S101ATAH0")
      )
      (libsource (lib "eagle-import") (part "TDK_MPZ1608S101ATAH0TDK_MPZ1608S101ATAH0_0_0"))
    )
    (comp (ref "J1")
      (value "C5178539_TYPE-CMOLEX_217179-0001_0_0")
      (footprint "eagle-import:C5178539_TYPE-C")
      (fields
        (field (name "DIGIKEY_PART_NUMBER") "900-2171790001CT-ND")
        (field (name "MF") "Molex")
        (field (name "MOUSER_PART_NUMBER") "538-217179-0001")
      )
      (libsource (lib "eagle-import") (part "C5178539_TYPE-CMOLEX_217179-0001_0_0"))
    )
    (comp (ref "L1_2.2UH_2A")
      (value "L_0805TDK_MLZ2012N6R8LT000_0_0")
      (footprint "eagle-import:TDK_MLZ2012N6R8LT000_0")
      (fields
        (field (name "MF") "TDK")
        (field (name "MPN") "MLZ2012N6R8LT000")
        (field (name "TOLERANCE") "20%")
      )
      (libsource (lib "eagle-import") (part "L_0805TDK_MLZ2012N6R8LT000_0_0"))
    )
    (comp (ref "L2_2.2UH_2A")
      (value "2.2uH 2A")
      (footprint "eagle-import:TDK_MLZ2012N6R8LT000_0")
      (fields
        (field (name "MF") "TDK")
        (field (name "MPN") "MLZ2012N6R8LT000")
        (field (name "TOLERANCE") "20%")
      )
      (libsource (lib "eagle-import") (part "L_0805TDK_MLZ2012N6R8LT000_0_0"))
    )
    (comp (ref "L3_2.2UH_2A")
      (value "2.2uH 2A")
      (footprint "eagle-import:TDK_MLZ2012N6R8LT000_0")
      (fields
        (field (name "MF") "TDK")
        (field (name "MPN") "MLZ2012N6R8LT000")
        (field (name "TOLERANCE") "20%")
      )
      (libsource (lib "eagle-import") (part "L_0805TDK_MLZ2012N6R8LT000_0_0"))
    )
    (comp (ref "R4")
      (value "680k")
      (footprint "eagle-import:R0805")
      (libsource (lib "eagle-import") (part "R-EU_R0805"))
    )
    (comp (ref "R5")
      (value "150k")
      (footprint "eagle-import:R0805")
      (libsource (lib "eagle-import") (part "R-EU_R0805"))
    )
    (comp (ref "R6")
      (value "150k")
      (footprint "eagle-import:R0805")
      (libsource (lib "eagle-import") (part "R-EU_R0805"))
    )
    (comp (ref "R7")
      (value "100k")
      (footprint "eagle-import:R0805")
      (libsource (lib "eagle-import") (part "R-EU_R0805"))
    )
    (comp (ref "R8")
      (value "100k")
      (footprint "eagle-import:R0805")
      (libsource (lib "eagle-import") (part "R-EU_R0805"))
    )
    (comp (ref "R9")
      (value "150k")
      (footprint "eagle-import:R0805")
      (libsource (lib "eagle-import") (part "R-EU_R0805"))
    )
    (comp (ref "R10")
      (value "5.1k")
      (footprint "eagle-import:R0805")
      (libsource (lib "eagle-import") (part "R-EU_R0805"))
    )
    (comp (ref "R11")
      (value "5.1k")
      (footprint "eagle-import:R0805")
      (libsource (lib "eagle-import") (part "R-EU_R0805"))
    )
    (comp (ref "R_EXTR")
      (value "10k")
      (footprint "eagle-import:R0805")
      (libsource (lib "eagle-import") (part "R-EU_R0805"))
    )
    (comp (ref "U$1")
      (value "GW2A-LV18PG256C8I7")
      (footprint "eagle-import:BGA256C100P16X16_1700X1700X155")
      (libsource (lib "eagle-import") (part "GW2A-LV18PG256C8I7"))
    )
    (comp (ref "U$3")
      (value "RY3415")
      (footprint "eagle-import:RY3415")
      (libsource (lib "eagle-import") (part "RY3415"))
    )
    (comp (ref "U$4")
      (value "RY3415")
      (footprint "eagle-import:RY3415")
      (libsource (lib "eagle-import") (part "RY3415"))
    )
    (comp (ref "U$5")
      (value "RY3415")
      (footprint "eagle-import:RY3415")
      (libsource (lib "eagle-import") (part "RY3415"))
    )
  )
  (nets
    (net (code "1") (name "1V0") (class "Default")
      (node (ref "C35") (pin "2") (pinfunction "2_2") (pintype "passive"))
      (node (ref "C36") (pin "2") (pinfunction "2_2") (pintype "passive"))
      (node (ref "C37") (pin "2") (pinfunction "2_2") (pintype "passive"))
      (node (ref "C38") (pin "2") (pinfunction "2_2") (pintype "passive"))
      (node (ref "C39") (pin "2") (pinfunction "2_2") (pintype "passive"))
      (node (ref "C40") (pin "2") (pinfunction "2_2") (pintype "passive"))
      (node (ref "C41") (pin "2") (pinfunction "2_2") (pintype "passive"))
      (node (ref "C68") (pin "2") (pinfunction "2_2") (pintype "passive"))
      (node (ref "FB3") (pin "2") (pinfunction "2_2") (pintype "passive"))
      (node (ref "FB4") (pin "1") (pinfunction "1_1") (pintype "passive"))
      (node (ref "FB5") (pin "1") (pinfunction "1_1") (pintype "passive"))
      (node (ref "J6") (pin "2") (pinfunction "2_2") (pintype "passive"))
      (node (ref "LED9") (pin "A") (pinfunction "A_A") (pintype "passive"))
      (node (ref "U$1") (pin "A1") (pinfunction "VCC_A1_A1") (pintype "power_in"))
      (node (ref "U$1") (pin "A16") (pinfunction "VCC_A16_A16") (pintype "power_in"))
      (node (ref "U$1") (pin "G7") (pinfunction "VCC_G7_G7") (pintype "power_in"))
      (node (ref "U$1") (pin "K10") (pinfunction "VCC_K10_K10") (pintype "power_in"))
      (node (ref "U$1") (pin "T1") (pinfunction "VCC_T1_T1") (pintype "power_in"))
      (node (ref "U$1") (pin "T16") (pinfunction "VCC_T16_T16") (pintype "power_in"))
    )
    (net (code "2") (name "1V5") (class "Default")
      (node (ref "C27") (pin "2") (pinfunction "2_2") (pintype "passive"))
      (node (ref "C28") (pin "2") (pinfunction "2_2") (pintype "passive"))
      (node (ref "C29") (pin "2") (pinfunction "2_2") (pintype "passive"))
      (node (ref "C30") (pin "2") (pinfunction "2_2") (pintype "passive"))
      (node (ref "C31") (pin "2") (pinfunction "2_2") (pintype "passive"))
      (node (ref "C32") (pin "2") (pinfunction "2_2") (pintype "passive"))
      (node (ref "C33") (pin "2") (pinfunction "2_2") (pintype "passive"))
      (node (ref "C34") (pin "2") (pinfunction "2_2") (pintype "passive"))
      (node (ref "FB2") (pin "2") (pinfunction "2_2") (pintype "passive"))
      (node (ref "J6") (pin "1") (pinfunction "1_1") (pintype "passive"))
      (node (ref "LED8") (pin "A") (pinfunction "A_A") (pintype "passive"))
      (node (ref "R25") (pin "2") (pinfunction "2_2") (pintype "passive"))
      (node (ref "R26") (pin "2") (pinfunction "2_2") (pintype "passive"))
      (node (ref "R27") (pin "2") (pinfunction "2_2") (pintype "passive"))
      (node (ref "R28") (pin "2") (pinfunction "2_2") (pintype "passive"))
      (node (ref "R29") (pin "2") (pinfunction "2_2") (pintype "passive"))
      (node (ref "U$1") (pin "D5") (pinfunction "VCCO6_D5_D5") (pintype "power_in"))
      (node (ref "U$1") (pin "E4") (pinfunction "VCCO5_E4_E4") (pintype "power_in"))
      (node (ref "U$1") (pin "H7") (pinfunction "VCCO5_H7_H7") (pintype "power_in"))
      (node (ref "U$1") (pin "J7") (pinfunction "VCCO4_J7_J7") (pintype "power_in"))
      (node (ref "U$1") (pin "M4") (pinfunction "VCCO4_M4_M4") (pintype "power_in"))
      (node (ref "U$13") (pin "6") (pinfunction "6_6") (pintype "passive"))
      (node (ref "U$13") (pin "7") (pinfunction "7_7") (pintype "passive"))
      (node (ref "U$13") (pin "8") (pinfunction "8_8") (pintype "passive"))
      (node (ref "U$13") (pin "9") (pinfunction "9_9") (pintype "passive"))
      (node (ref "U$23") (pin "10") (pinfunction "DVDD_10") (pintype "bidirectional"))
    )
    (net (code "3") (name "2V8") (class "Default")
      (node (ref "C89") (pin "2") (pinfunction "2_2") (pintype "passive"))
      (node (ref "C90") (pin "2") (pinfunction "2_2") (pintype "passive"))
      (node (ref "C94") (pin "2") (pinfunction "2_2") (pintype "passive"))
      (node (ref "J6") (pin "3") (pinfunction "3_3") (pintype "passive"))
      (node (ref "R122") (pin "2") (pinfunction "2_2") (pintype "passive"))
      (node (ref "R123") (pin "2") (pinfunction "2_2") (pintype "passive"))
      (node (ref "U$22") (pin "2") (pinfunction "VOUT_2") (pintype "bidirectional"))
      (node (ref "U$23") (pin "11") (pinfunction "DOVDD_11") (pintype "bidirectional"))
      (node (ref "U$24") (pin "P$2") (pinfunction "G1_P$2") (pintype "passive"))
      (node (ref "U$24") (pin "P$5") (pinfunction "G2_P$5") (pintype "passive"))
      (node (ref "U4") (pin "1") (pinfunction "VCC(A)_1") (pintype "bidirectional"))
    )
    (net (code "4") (name "3V0") (class "Default")
      (node (ref "C83") (pin "2") (pinfunction "2_2") (pintype "passive"))
      (node (ref "C84") (pin "2") (pinfunction "2_2") (pintype "passive"))
      (node (ref "C92") (pin "2") (pinfunction "2_2") (pintype "passive"))
      (node (ref "C93") (pin "2") (pinfunction "2_2") (pintype "passive"))
      (node (ref "J6") (pin "5") (pinfunction "5_5") (pintype "passive"))
      (node (ref "U$20") (pin "2") (pinfunction "VOUT_2") (pintype "bidirectional"))
      (node (ref "U$23") (pin "4") (pinfunction "AVDD_4") (pintype "bidirectional"))
    )
    (net (code "5") (name "3V3") (class "Default")
      (node (ref "C13") (pin "2") (pinfunction "2_2") (pintype "passive"))
      (node (ref "C14") (pin "2") (pinfunction "2_2") (pintype "passive"))
      (node (ref "C20") (pin "2") (pinfunction "2_2") (pintype "passive"))
      (node (ref "C21") (pin "2") (pinfunction "2_2") (pintype "passive"))
      (node (ref "C22") (pin "2") (pinfunction "2_2") (pintype "passive"))
      (node (ref "C23") (pin "2") (pinfunction "2_2") (pintype "passive"))
      (node (ref "C24") (pin "2") (pinfunction "2_2") (pintype "passive"))
      (node (ref "C25") (pin "2") (pinfunction "2_2") (pintype "passive"))
      (node (ref "C26") (pin "2") (pinfunction "2_2") (pintype "passive"))
      (node (ref "C42") (pin "2") (pinfunction "2_2") (pintype "passive"))
      (node (ref "C43") (pin "2") (pinfunction "2_2") (pintype "passive"))
      (node (ref "C44") (pin "2") (pinfunction "2_2") (pintype "passive"))
      (node (ref "C45") (pin "2") (pinfunction "2_2") (pintype "passive"))
      (node (ref "C47") (pin "2") (pinfunction "2_2") (pintype "passive"))
      (node (ref "C48") (pin "2") (pinfunction "2_2") (pintype "passive"))
      (node (ref "C63") (pin "1") (pinfunction "1_1") (pintype "passive"))
      (node (ref "C65") (pin "1") (pinfunction "1_1") (pintype "passive"))
      (node (ref "C66") (pin "2") (pinfunction "2_2") (pintype "passive"))
      (node (ref "C67") (pin "2") (pinfunction "2_2") (pintype "passive"))
      (node (ref "C81") (pin "2") (pinfunction "2_2") (pintype "passive"))
      (node (ref "C82") (pin "2") (pinfunction "2_2") (pintype "passive"))
      (node (ref "C91") (pin "2") (pinfunction "2_2") (pintype "passive"))
      (node (ref "FB") (pin "P$1") (pinfunction "1_P$1") (pintype "bidirectional"))
      (node (ref "FB1") (pin "2") (pinfunction "2_2") (pintype "passive"))
      (node (ref "FB8") (pin "2") (pinfunction "2_2") (pintype "passive"))
      (node (ref "IC1") (pin "14") (pinfunction "DVDD33_14") (pintype "bidirectional"))
      (node (ref "IC1") (pin "30") (pinfunction "AVDD33_2_30") (pintype "bidirectional"))
      (node (ref "IC1") (pin "7") (pinfunction "AVDD33_1_7") (pintype "bidirectional"))
      (node (ref "J2") (pin "4") (pinfunction "VDD_4") (pintype "bidirectional"))
      (node (ref "J3") (pin "12") (pinfunction "YA_12") (pintype "passive"))
      (node (ref "J6") (pin "7") (pinfunction "7_7") (pintype "passive"))
      (node (ref "LED1") (pin "A") (pinfunction "A_A") (pintype "passive"))
      (node (ref "LED2") (pin "A") (pinfunction "A_A") (pintype "passive"))
      (node (ref "LED3") (pin "A") (pinfunction "A_A") (pintype "passive"))
      (node (ref "LED4") (pin "A") (pinfunction "A_A") (pintype "passive"))
      (node (ref "LED5") (pin "A") (pinfunction "A_A") (pintype "passive"))
      (node (ref "LED6") (pin "A") (pinfunction "A_A") (pintype "passive"))
      (node (ref "LED7") (pin "A") (pinfunction "A_A") (pintype "passive"))
      (node (ref "Q1") (pin "2") (pinfunction "S_2") (pintype "passive"))
      (node (ref "R100") (pin "1") (pinfunction "1_1") (pintype "passive"))
      (node (ref "R101") (pin "1") (pinfunction "1_1") (pintype "passive"))
      (node (ref "R138") (pin "1") (pinfunction "1_1") (pintype "passive"))
      (node (ref "R139") (pin "1") (pinfunction "1_1") (pintype "passive"))
      (node (ref "R140") (pin "1") (pinfunction "1_1") (pintype "passive"))
      (node (ref "R141") (pin "1") (pinfunction "1_1") (pintype "passive"))
      (node (ref "R142") (pin "1") (pinfunction "1_1") (pintype "passive"))
      (node (ref "R143") (pin "1") (pinfunction "1_1") (pintype "passive"))
      (node (ref "R16") (pin "2") (pinfunction "2_2") (pintype "passive"))
      (node (ref "R17") (pin "2") (pinfunction "2_2") (pintype "passive"))
      (node (ref "R18") (pin "2") (pinfunction "2_2") (pintype "passive"))
      (node (ref "R2") (pin "1") (pinfunction "1_1") (pintype "passive"))
      (node (ref "R30") (pin "1") (pinfunction "1_1") (pintype "passive"))
      (node (ref "R31") (pin "1") (pinfunction "1_1") (pintype "passive"))
      (node (ref "R32") (pin "1") (pinfunction "1_1") (pintype "passive"))
      (node (ref "R33") (pin "1") (pinfunction "1_1") (pintype "passive"))
      (node (ref "R34") (pin "1") (pinfunction "1_1") (pintype "passive"))
      (node (ref "R35") (pin "2") (pinfunction "2_2") (pintype "passive"))
      (node (ref "R51") (pin "2") (pinfunction "2_2") (pintype "passive"))
      (node (ref "R52") (pin "2") (pinfunction "2_2") (pintype "passive"))
      (node (ref "R59") (pin "1") (pinfunction "1_1") (pintype "passive"))
      (node (ref "R89") (pin "1") (pinfunction "1_1") (pintype "passive"))
      (node (ref "R98") (pin "1") (pinfunction "1_1") (pintype "passive"))
      (node (ref "U$1") (pin "D12") (pinfunction "VCCO7_D12_D12") (pintype "power_in"))
      (node (ref "U$1") (pin "E13") (pinfunction "VCCO0_E13_E13") (pintype "power_in"))
      (node (ref "U$1") (pin "G8") (pinfunction "VCCX_G8_G8") (pintype "power_in"))
      (node (ref "U$1") (pin "G9") (pinfunction "VCCO7_G9_G9") (pintype "power_in"))
      (node (ref "U$1") (pin "H10") (pinfunction "VCCO0_H10_H10") (pintype "power_in"))
      (node (ref "U$1") (pin "J10") (pinfunction "VCCO1_J10_J10") (pintype "power_in"))
      (node (ref "U$1") (pin "K8") (pinfunction "VCCO3_K8_K8") (pintype "power_in"))
      (node (ref "U$1") (pin "K9") (pinfunction "VCCX_K9_K9") (pintype "power_in"))
      (node (ref "U$1") (pin "M13") (pinfunction "VCCO1_M13_M13") (pintype "power_in"))
      (node (ref "U$1") (pin "N12") (pinfunction "VCCO2_N12_N12") (pintype "power_in"))
      (node (ref "U$1") (pin "N5") (pinfunction "VCCO3_N5_N5") (pintype "power_in"))
      (node (ref "U$13") (pin "10") (pinfunction "10_10") (pintype "passive"))
      (node (ref "U$14") (pin "7") (pinfunction "VDD_7") (pintype "passive"))
      (node (ref "U$16") (pin "3") (pinfunction "VCC_3") (pintype "power_in"))
      (node (ref "U$22") (pin "3") (pinfunction "VIN_3") (pintype "bidirectional"))
      (node (ref "U$25") (pin "2") (pinfunction "2_2") (pintype "bidirectional"))
      (node (ref "U1") (pin "20") (pinfunction "1_VCCIO_20") (pintype "power_in"))
      (node (ref "U1") (pin "31") (pinfunction "2_VCCIO_31") (pintype "power_in"))
      (node (ref "U1") (pin "4") (pinfunction "VPHY_4") (pintype "power_in"))
      (node (ref "U1") (pin "42") (pinfunction "3_VCCIO_42") (pintype "power_in"))
      (node (ref "U1") (pin "50") (pinfunction "VREGIN_50") (pintype "power_in"))
      (node (ref "U1") (pin "56") (pinfunction "4_VCCIO_56") (pintype "power_in"))
      (node (ref "U1") (pin "9") (pinfunction "VPLL_9") (pintype "power_in"))
      (node (ref "U2") (pin "8") (pinfunction "VCC_8") (pintype "power_in"))
      (node (ref "U4") (pin "6") (pinfunction "VCC(B)_6") (pintype "bidirectional"))
      (node (ref "U5") (pin "1") (pinfunction "1_VDD_1") (pintype "power_in"))
      (node (ref "U5") (pin "14") (pinfunction "2_VDD_14") (pintype "power_in"))
      (node (ref "U5") (pin "27") (pinfunction "3_VDD_27") (pintype "power_in"))
      (node (ref "U5") (pin "3") (pinfunction "1_VDDQ_3") (pintype "power_in"))
      (node (ref "U5") (pin "43") (pinfunction "3_VDDQ_43") (pintype "power_in"))
      (node (ref "U5") (pin "49") (pinfunction "4_VDDQ_49") (pintype "power_in"))
      (node (ref "U5") (pin "9") (pinfunction "2_VDDQ_9") (pintype "power_in"))
    )
    (net (code "6") (name "B16_MODE1") (class "Default")
      (node (ref "R14") (pin "2") (pinfunction "2_2") (pintype "passive"))
      (node (ref "U$1") (pin "B16") (pinfunction "MODE1_B16") (pintype "bidirectional"))
    )
    (net (code "7") (name "BTN1") (class "Default")
      (node (ref "C58") (pin "2") (pinfunction "2_2") (pintype "passive"))
      (node (ref "C76") (pin "2") (pinfunction "2_2") (pintype "passive"))
      (node (ref "R25") (pin "1") (pinfunction "1_1") (pintype "passive"))
      (node (ref "R89") (pin "2") (pinfunction "2_2") (pintype "passive"))
      (node (ref "S1") (pin "1") (pinfunction "1_1") (pintype "bidirectional"))
      (node (ref "U$1") (pin "T10") (pinfunction "IOR35B/D2/LVDS/DQ9_T10") (pintype "bidirectional"))
      (node (ref "U$16") (pin "2") (pinfunction "~{RESET}_2") (pintype "bidirectional"))
      (node (ref "U$7") (pin "2") (pinfunction "2_2") (pintype "passive"))
    )
    (net (code "8") (name "BTN2") (class "Default")
      (node (ref "C59") (pin "2") (pinfunction "2_2") (pintype "passive"))
      (node (ref "R26") (pin "1") (pinfunction "1_1") (pintype "passive"))
      (node (ref "S2") (pin "1") (pinfunction "1_1") (pintype "bidirectional"))
      (node (ref "U$1") (pin "G3") (pinfunction "IOB21B/DQS5_G3") (pintype "bidirectional"))
      (node (ref "U$8") (pin "2") (pinfunction "2_2") (pintype "passive"))
    )
    (net (code "9") (name "BTN3") (class "Default")
      (node (ref "C60") (pin "2") (pinfunction "2_2") (pintype "passive"))
      (node (ref "R27") (pin "1") (pinfunction "1_1") (pintype "passive"))
      (node (ref "S3") (pin "1") (pinfunction "1_1") (pintype "bidirectional"))
      (node (ref "U$1") (pin "G4") (pinfunction "IOB20B/LVDS/DQ5_G4") (pintype "bidirectional"))
      (node (ref "U$9") (pin "2") (pinfunction "2_2") (pintype "passive"))
    )
    (net (code "10") (name "BTN4") (class "Default")
      (node (ref "C61") (pin "2") (pinfunction "2_2") (pintype "passive"))
      (node (ref "R28") (pin "1") (pinfunction "1_1") (pintype "passive"))
      (node (ref "S4") (pin "1") (pinfunction "1_1") (pintype "bidirectional"))
      (node (ref "U$1") (pin "H4") (pinfunction "IOB26A/LVDS/DQ5_H4") (pintype "bidirectional"))
      (node (ref "U$10") (pin "2") (pinfunction "2_2") (pintype "passive"))
    )
    (net (code "11") (name "BTN5") (class "Default")
      (node (ref "C62") (pin "2") (pinfunction "2_2") (pintype "passive"))
      (node (ref "R29") (pin "1") (pinfunction "1_1") (pintype "passive"))
      (node (ref "S5") (pin "1") (pinfunction "1_1") (pintype "bidirectional"))
      (node (ref "U$1") (pin "H3") (pinfunction "IOB32A/LVDS/DQ6_H3") (pintype "bidirectional"))
      (node (ref "U$11") (pin "2") (pinfunction "2_2") (pintype "passive"))
    )
    (net (code "12") (name "C15_MODE2") (class "Default")
      (node (ref "R15") (pin "2") (pinfunction "2_2") (pintype "passive"))
      (node (ref "U$1") (pin "C15") (pinfunction "MODE2_C15") (pintype "bidirectional"))
    )
    (net (code "13") (name "CKXTAL1") (class "Default")
      (node (ref "C78") (pin "2") (pinfunction "2_2") (pintype "passive"))
      (node (ref "IC1") (pin "31") (pinfunction "CKXTAL1_31") (pintype "bidirectional"))
      (node (ref "U$17") (pin "3") (pinfunction "OSC2_3") (pintype "bidirectional"))
    )
    (net (code "14") (name "CKXTAL2") (class "Default")
      (node (ref "C77") (pin "2") (pinfunction "2_2") (pintype "passive"))
      (node (ref "IC1") (pin "32") (pinfunction "CKXTAL2_32") (pintype "bidirectional"))
      (node (ref "U$17") (pin "1") (pinfunction "OSC1_1") (pintype "bidirectional"))
    )
    (net (code "15") (name "DIP1") (class "Default")
      (node (ref "R16") (pin "1") (pinfunction "1_1") (pintype "passive"))
      (node (ref "R37") (pin "1") (pinfunction "1_1") (pintype "passive"))
      (node (ref "R42") (pin "2") (pinfunction "2_2") (pintype "passive"))
      (node (ref "U$1") (pin "B10") (pinfunction "IOR31B/RECONFIG_N/LVDS/DQ9_B10") (pintype "bidirectional"))
    )
    (net (code "16") (name "DIP2") (class "Default")
      (node (ref "R38") (pin "1") (pinfunction "1_1") (pintype "passive"))
      (node (ref "R43") (pin "2") (pinfunction "2_2") (pintype "passive"))
      (node (ref "U$1") (pin "A10") (pinfunction "IOL33B/LVDS/DQ2_A10") (pintype "bidirectional"))
    )
    (net (code "17") (name "DIP3") (class "Default")
      (node (ref "R39") (pin "1") (pinfunction "1_1") (pintype "passive"))
      (node (ref "R44") (pin "2") (pinfunction "2_2") (pintype "passive"))
      (node (ref "U$1") (pin "B9") (pinfunction "IOL33A/LVDS/DQ2_B9") (pintype "bidirectional"))
    )
    (net (code "18") (name "DIP4") (class "Default")
      (node (ref "R40") (pin "1") (pinfunction "1_1") (pintype "passive"))
      (node (ref "R45") (pin "2") (pinfunction "2_2") (pintype "passive"))
      (node (ref "U$1") (pin "A9") (pinfunction "IOL27A/GCLKT_7/DQ1_A9") (pintype "bidirectional"))
    )
    (net (code "19") (name "DIP5") (class "Default")
      (node (ref "R41") (pin "1") (pinfunction "1_1") (pintype "passive"))
      (node (ref "R46") (pin "2") (pinfunction "2_2") (pintype "passive"))
      (node (ref "U$1") (pin "A8") (pinfunction "IOL29B/GCLKC_6/LVDS/DQ2_A8") (pintype "bidirectional"))
    )
    (net (code "20") (name "DVP_D0") (class "Default")
      (node (ref "U$1") (pin "N16") (pinfunction "IOT52A/LVDS/DQ12_N16") (pintype "bidirectional"))
      (node (ref "U$23") (pin "19") (pinfunction "Y2_19") (pintype "bidirectional"))
    )
    (net (code "21") (name "DVP_D1") (class "Default")
      (node (ref "U$1") (pin "M14") (pinfunction "IOT40A/LVDS/DQ13_M14") (pintype "bidirectional"))
      (node (ref "U$23") (pin "21") (pinfunction "Y3_21") (pintype "bidirectional"))
    )
    (net (code "22") (name "DVP_D2") (class "Default")
      (node (ref "U$1") (pin "N15") (pinfunction "IOT48A/LVDS/DQS12_N15") (pintype "bidirectional"))
      (node (ref "U$23") (pin "22") (pinfunction "Y4_22") (pintype "bidirectional"))
    )
    (net (code "23") (name "DVP_D3") (class "Default")
      (node (ref "U$1") (pin "M15") (pinfunction "IOT40B/LVDS/DQ13_M15") (pintype "bidirectional"))
      (node (ref "U$23") (pin "20") (pinfunction "Y5_20") (pintype "bidirectional"))
    )
    (net (code "24") (name "DVP_D4") (class "Default")
      (node (ref "U$1") (pin "L15") (pinfunction "IOT2A/LVDS/DQ15_L15") (pintype "bidirectional"))
      (node (ref "U$23") (pin "18") (pinfunction "Y6_18") (pintype "bidirectional"))
    )
    (net (code "25") (name "DVP_D5") (class "Default")
      (node (ref "U$1") (pin "K14") (pinfunction "IOT30A/GCLKT_1/LVDS/DQ13_K14") (pintype "bidirectional"))
      (node (ref "U$23") (pin "16") (pinfunction "Y7_16") (pintype "bidirectional"))
    )
    (net (code "26") (name "DVP_D6") (class "Default")
      (node (ref "U$1") (pin "K15") (pinfunction "IOT30B/GCLKC_1/LVDS/DQ13_K15") (pintype "bidirectional"))
      (node (ref "U$23") (pin "14") (pinfunction "Y8_14") (pintype "bidirectional"))
    )
    (net (code "27") (name "DVP_D7") (class "Default")
      (node (ref "U$1") (pin "J14") (pinfunction "IOT22B/LVDS/DQ14_J14") (pintype "bidirectional"))
      (node (ref "U$23") (pin "12") (pinfunction "Y9_12") (pintype "bidirectional"))
    )
    (net (code "28") (name "DVP_HSYNC") (class "Default")
      (node (ref "U$1") (pin "K16") (pinfunction "IOT24B/LVDS/DQ14_K16") (pintype "bidirectional"))
      (node (ref "U$23") (pin "9") (pinfunction "HREF_9") (pintype "bidirectional"))
    )
    (net (code "29") (name "DVP_PCLK") (class "Default")
      (node (ref "U$1") (pin "L16") (pinfunction "IOT34A/LVDS/DQ13_L16") (pintype "bidirectional"))
      (node (ref "U$23") (pin "17") (pinfunction "PCLK_17") (pintype "bidirectional"))
    )
    (net (code "30") (name "DVP_SBCL") (class "Default")
      (node (ref "R122") (pin "1") (pinfunction "1_1") (pintype "passive"))
      (node (ref "U$23") (pin "5") (pinfunction "SIO_C_5") (pintype "bidirectional"))
      (node (ref "U$24") (pin "P$1") (pinfunction "S1_P$1") (pintype "passive"))
    )
    (net (code "31") (name "DVP_SBDA") (class "Default")
      (node (ref "R123") (pin "1") (pinfunction "1_1") (pintype "passive"))
      (node (ref "U$23") (pin "3") (pinfunction "SIO_D_3") (pintype "bidirectional"))
      (node (ref "U$24") (pin "P$4") (pinfunction "S2_P$4") (pintype "passive"))
    )
    (net (code "32") (name "DVP_VSYNC") (class "Default")
      (node (ref "U$1") (pin "J16") (pinfunction "IOT22A/LVDS/DQ14_J16") (pintype "bidirectional"))
      (node (ref "U$23") (pin "7") (pinfunction "VSYNC_7") (pintype "bidirectional"))
    )
    (net (code "33") (name "DVP_XCLK") (class "Default")
      (node (ref "U$1") (pin "G12") (pinfunction "IOT8B/DQS15_G12") (pintype "bidirectional"))
      (node (ref "U4") (pin "4") (pinfunction "B_4") (pintype "bidirectional"))
    )
    (net (code "34") (name "DVP_XCLK_2V8") (class "Default")
      (node (ref "U$23") (pin "13") (pinfunction "XCLK_13") (pintype "bidirectional"))
      (node (ref "U4") (pin "3") (pinfunction "A_3") (pintype "bidirectional"))
    )
    (net (code "35") (name "DVP_~{PWDN}") (class "Default")
      (node (ref "R120") (pin "1") (pinfunction "1_1") (pintype "passive"))
      (node (ref "U$1") (pin "J15") (pinfunction "IOT24A/LVDS/DQ14_J15") (pintype "bidirectional"))
      (node (ref "U$23") (pin "8") (pinfunction "PWDN_8") (pintype "bidirectional"))
    )
    (net (code "36") (name "DVP_~{RST}") (class "Default")
      (node (ref "R119") (pin "1") (pinfunction "1_1") (pintype "passive"))
      (node (ref "U$1") (pin "L14") (pinfunction "IOT34B/LVDS/DQ13_L14") (pintype "bidirectional"))
      (node (ref "U$23") (pin "6") (pinfunction "RESET_6") (pintype "bidirectional"))
    )
    (net (code "37") (name "GND") (class "Default")
      (node (ref "C1") (pin "1") (pinfunction "1_1") (pintype "passive"))
      (node (ref "C10") (pin "1") (pinfunction "1_1") (pintype "passive"))
      (node (ref "C11") (pin "1") (pinfunction "1_1") (pintype "passive"))
      (node (ref "C12") (pin "1") (pinfunction "1_1") (pintype "passive"))
      (node (ref "C13") (pin "1") (pinfunction "1_1") (pintype "passive"))
      (node (ref "C14") (pin "1") (pinfunction "1_1") (pintype "passive"))
      (node (ref "C15") (pin "1") (pinfunction "1_1") (pintype "passive"))
      (node (ref "C17") (pin "1") (pinfunction "1_1") (pintype "passive"))
      (node (ref "C18") (pin "1") (pinfunction "1_1") (pintype "passive"))
      (node (ref "C19") (pin "1") (pinfunction "1_1") (pintype "passive"))
      (node (ref "C2") (pin "1") (pinfunction "1_1") (pintype "passive"))
      (node (ref "C20") (pin "1") (pinfunction "1_1") (pintype "passive"))
      (node (ref "C21") (pin "1") (pinfunction "1_1") (pintype "passive"))
      (node (ref "C22") (pin "1") (pinfunction "1_1") (pintype "passive"))
      (node (ref "C23") (pin "1") (pinfunction "1_1") (pintype "passive"))
      (node (ref "C24") (pin "1") (pinfunction "1_1") (pintype "passive"))
      (node (ref "C25") (pin "1") (pinfunction "1_1") (pintype "passive"))
      (node (ref "C26") (pin "1") (pinfunction "1_1") (pintype "passive"))
      (node (ref "C27") (pin "1") (pinfunction "1_1") (pintype "passive"))
      (node (ref "C28") (pin "1") (pinfunction "1_1") (pintype "passive"))
      (node (ref "C29") (pin "1") (pinfunction "1_1") (pintype "passive"))
      (node (ref "C3") (pin "1") (pinfunction "1_1") (pintype "passive"))
      (node (ref "C30") (pin "1") (pinfunction "1_1") (pintype "passive"))
      (node (ref "C31") (pin "1") (pinfunction "1_1") (pintype "passive"))
      (node (ref "C32") (pin "1") (pinfunction "1_1") (pintype "passive"))
      (node (ref "C33") (pin "1") (pinfunction "1_1") (pintype "passive"))
      (node (ref "C34") (pin "1") (pinfunction "1_1") (pintype "passive"))
      (node (ref "C35") (pin "1") (pinfunction "1_1") (pintype "passive"))
      (node (ref "C36") (pin "1") (pinfunction "1_1") (pintype "passive"))
      (node (ref "C37") (pin "1") (pinfunction "1_1") (pintype "passive"))
      (node (ref "C38") (pin "1") (pinfunction "1_1") (pintype "passive"))
      (node (ref "C39") (pin "1") (pinfunction "1_1") (pintype "passive"))
      (node (ref "C4") (pin "1") (pinfunction "1_1") (pintype "passive"))
      (node (ref "C40") (pin "1") (pinfunction "1_1") (pintype "passive"))
      (node (ref "C41") (pin "1") (pinfunction "1_1") (pintype "passive"))
      (node (ref "C42") (pin "1") (pinfunction "1_1") (pintype "passive"))
      (node (ref "C43") (pin "1") (pinfunction "1_1") (pintype "passive"))
      (node (ref "C44") (pin "1") (pinfunction "1_1") (pintype "passive"))
      (node (ref "C45") (pin "1") (pinfunction "1_1") (pintype "passive"))
      (node (ref "C46") (pin "2") (pinfunction "2_2") (pintype "passive"))
      (node (ref "C47") (pin "1") (pinfunction "1_1") (pintype "passive"))
      (node (ref "C48") (pin "1") (pinfunction "1_1") (pintype "passive"))
      (node (ref "C49") (pin "2") (pinfunction "2_2") (pintype "passive"))
      (node (ref "C5") (pin "1") (pinfunction "1_1") (pintype "passive"))
      (node (ref "C50") (pin "1") (pinfunction "1_1") (pintype "passive"))
      (node (ref "C51") (pin "1") (pinfunction "1_1") (pintype "passive"))
      (node (ref "C52") (pin "1") (pinfunction "1_1") (pintype "passive"))
      (node (ref "C53") (pin "1") (pinfunction "1_1") (pintype "passive"))
      (node (ref "C54") (pin "1") (pinfunction "1_1") (pintype "passive"))
      (node (ref "C55") (pin "1") (pinfunction "1_1") (pintype "passive"))
      (node (ref "C56") (pin "1") (pinfunction "1_1") (pintype "passive"))
      (node (ref "C57") (pin "2") (pinfunction "2_2") (pintype "passive"))
      (node (ref "C58") (pin "1") (pinfunction "1_1") (pintype "passive"))
      (node (ref "C59") (pin "1") (pinfunction "1_1") (pintype "passive"))
      (node (ref "C6") (pin "1") (pinfunction "1_1") (pintype "passive"))
      (node (ref "C60") (pin "1") (pinfunction "1_1") (pintype "passive"))
      (node (ref "C61") (pin "1") (pinfunction "1_1") (pintype "passive"))
      (node (ref "C62") (pin "1") (pinfunction "1_1") (pintype "passive"))
      (node (ref "C64") (pin "1") (pinfunction "1_1") (pintype "passive"))
      (node (ref "C65") (pin "2") (pinfunction "2_2") (pintype "passive"))
      (node (ref "C66") (pin "1") (pinfunction "1_1") (pintype "passive"))
      (node (ref "C67") (pin "1") (pinfunction "1_1") (pintype "passive"))
      (node (ref "C68") (pin "1") (pinfunction "1_1") (pintype "passive"))
      (node (ref "C7") (pin "1") (pinfunction "1_1") (pintype "passive"))
      (node (ref "C76") (pin "1") (pinfunction "1_1") (pintype "passive"))
      (node (ref "C77") (pin "1") (pinfunction "1_1") (pintype "passive"))
      (node (ref "C78") (pin "1") (pinfunction "1_1") (pintype "passive"))
      (node (ref "C79") (pin "1") (pinfunction "1_1") (pintype "passive"))
      (node (ref "C8") (pin "1") (pinfunction "1_1") (pintype "passive"))
      (node (ref "C80") (pin "1") (pinfunction "1_1") (pintype "passive"))
      (node (ref "C81") (pin "1") (pinfunction "1_1") (pintype "passive"))
      (node (ref "C82") (pin "1") (pinfunction "1_1") (pintype "passive"))
      (node (ref "C83") (pin "1") (pinfunction "1_1") (pintype "passive"))
      (node (ref "C84") (pin "1") (pinfunction "1_1") (pintype "passive"))
      (node (ref "C85") (pin "1") (pinfunction "1_1") (pintype "passive"))
      (node (ref "C89") (pin "1") (pinfunction "1_1") (pintype "passive"))
      (node (ref "C9") (pin "1") (pinfunction "1_1") (pintype "passive"))
      (node (ref "C90") (pin "1") (pinfunction "1_1") (pintype "passive"))
      (node (ref "C91") (pin "1") (pinfunction "1_1") (pintype "passive"))
      (node (ref "C92") (pin "1") (pinfunction "1_1") (pintype "passive"))
      (node (ref "C93") (pin "1") (pinfunction "1_1") (pintype "passive"))
      (node (ref "C94") (pin "1") (pinfunction "1_1") (pintype "passive"))
      (node (ref "C95") (pin "1") (pinfunction "1_1") (pintype "passive"))
      (node (ref "C96") (pin "1") (pinfunction "1_1") (pintype "passive"))
      (node (ref "C97") (pin "1") (pinfunction "1_1") (pintype "passive"))
      (node (ref "C98") (pin "1") (pinfunction "1_1") (pintype "passive"))
      (node (ref "C99") (pin "1") (pinfunction "1_1") (pintype "passive"))
      (node (ref "D1") (pin "3-8") (pinfunction "GROUND_3-8") (pintype "power_in"))
      (node (ref "D2") (pin "2") (pinfunction "2_2") (pintype "passive"))
      (node (ref "D3") (pin "2") (pinfunction "2_2") (pintype "passive"))
      (node (ref "D4") (pin "2") (pinfunction "2_2") (pintype "passive"))
      (node (ref "D5") (pin "2") (pinfunction "2_2") (pintype "passive"))
      (node (ref "D6") (pin "3-8") (pinfunction "GROUND_3-8") (pintype "power_in"))
      (node (ref "D7") (pin "3-8") (pinfunction "GROUND_3-8") (pintype "power_in"))
      (node (ref "IC1") (pin "33") (pinfunction "EP_33") (pintype "bidirectional"))
      (node (ref "J1") (pin "1") (pinfunction "MNT_1_1") (pintype "passive"))
      (node (ref "J1") (pin "2") (pinfunction "MNT_2_2") (pintype "passive"))
      (node (ref "J1") (pin "3") (pinfunction "MNT_3_3") (pintype "passive"))
      (node (ref "J1") (pin "4") (pinfunction "MNT_4_4") (pintype "passive"))
      (node (ref "J1") (pin "A1-B12") (pinfunction "1_GND_A1-B12") (pintype "power_in"))
      (node (ref "J1") (pin "B1-A12") (pinfunction "2_GND_B1-A12") (pintype "power_in"))
      (node (ref "J2") (pin "11") (pinfunction "GND_1_11") (pintype "bidirectional"))
      (node (ref "J2") (pin "12") (pinfunction "GND_2_12") (pintype "bidirectional"))
      (node (ref "J2") (pin "13") (pinfunction "GND_3_13") (pintype "bidirectional"))
      (node (ref "J2") (pin "14") (pinfunction "GND_4_14") (pintype "bidirectional"))
      (node (ref "J2") (pin "15") (pinfunction "GND_5_15") (pintype "bidirectional"))
      (node (ref "J2") (pin "16") (pinfunction "GND_6_16") (pintype "bidirectional"))
      (node (ref "J2") (pin "6") (pinfunction "VSS_6") (pintype "bidirectional"))
      (node (ref "J3") (pin "10") (pinfunction "GC_10") (pintype "passive"))
      (node (ref "J3") (pin "15") (pinfunction "SHIELD_15") (pintype "passive"))
      (node (ref "J3") (pin "16") (pinfunction "SHIELD_16") (pintype "passive"))
      (node (ref "J3") (pin "8") (pinfunction "GND_8") (pintype "power_in"))
      (node (ref "J6") (pin "10") (pinfunction "10_10") (pintype "passive"))
      (node (ref "J6") (pin "4") (pinfunction "4_4") (pintype "passive"))
      (node (ref "J6") (pin "6") (pinfunction "6_6") (pintype "passive"))
      (node (ref "J6") (pin "8") (pinfunction "8_8") (pintype "passive"))
      (node (ref "R1") (pin "1") (pinfunction "1_1") (pintype "passive"))
      (node (ref "R10") (pin "1") (pinfunction "1_1") (pintype "passive"))
      (node (ref "R102") (pin "1") (pinfunction "1_1") (pintype "passive"))
      (node (ref "R103") (pin "2") (pinfunction "2_2") (pintype "passive"))
      (node (ref "R11") (pin "1") (pinfunction "1_1") (pintype "passive"))
      (node (ref "R119") (pin "2") (pinfunction "2_2") (pintype "passive"))
      (node (ref "R12") (pin "2") (pinfunction "2_2") (pintype "passive"))
      (node (ref "R120") (pin "2") (pinfunction "2_2") (pintype "passive"))
      (node (ref "R121") (pin "2") (pinfunction "2_2") (pintype "passive"))
      (node (ref "R13") (pin "1") (pinfunction "1_1") (pintype "passive"))
      (node (ref "R134") (pin "2") (pinfunction "2_2") (pintype "passive"))
      (node (ref "R14") (pin "1") (pinfunction "1_1") (pintype "passive"))
      (node (ref "R15") (pin "1") (pinfunction "1_1") (pintype "passive"))
      (node (ref "R156") (pin "2") (pinfunction "2_2") (pintype "passive"))
      (node (ref "R157") (pin "2") (pinfunction "2_2") (pintype "passive"))
      (node (ref "R3") (pin "1") (pinfunction "1_1") (pintype "passive"))
      (node (ref "R42") (pin "1") (pinfunction "1_1") (pintype "passive"))
      (node (ref "R43") (pin "1") (pinfunction "1_1") (pintype "passive"))
      (node (ref "R44") (pin "1") (pinfunction "1_1") (pintype "passive"))
      (node (ref "R45") (pin "1") (pinfunction "1_1") (pintype "passive"))
      (node (ref "R46") (pin "1") (pinfunction "1_1") (pintype "passive"))
      (node (ref "R5") (pin "2") (pinfunction "2_2") (pintype "passive"))
      (node (ref "R57") (pin "1") (pinfunction "1_1") (pintype "passive"))
      (node (ref "R7") (pin "2") (pinfunction "2_2") (pintype "passive"))
      (node (ref "R9") (pin "2") (pinfunction "2_2") (pintype "passive"))
      (node (ref "R97") (pin "1") (pinfunction "1_1") (pintype "passive"))
      (node (ref "R99") (pin "1") (pinfunction "1_1") (pintype "passive"))
      (node (ref "R_EXTR") (pin "2") (pinfunction "2_2") (pintype "passive"))
      (node (ref "S1") (pin "4") (pinfunction "4_4") (pintype "bidirectional"))
      (node (ref "S2") (pin "4") (pinfunction "4_4") (pintype "bidirectional"))
      (node (ref "S3") (pin "4") (pinfunction "4_4") (pintype "bidirectional"))
      (node (ref "S4") (pin "4") (pinfunction "4_4") (pintype "bidirectional"))
      (node (ref "S5") (pin "4") (pinfunction "4_4") (pintype "bidirectional"))
      (node (ref "U$1") (pin "B15") (pinfunction "VSS_B15_B15") (pintype "power_in"))
      (node (ref "U$1") (pin "B2") (pinfunction "VSS_B2_B2") (pintype "power_in"))
      (node (ref "U$1") (pin "C14") (pinfunction "VSS_C14_C14") (pintype "power_in"))
      (node (ref "U$1") (pin "C3") (pinfunction "VSS_C3_C3") (pintype "power_in"))
      (node (ref "U$1") (pin "D13") (pinfunction "VSS_D13_D13") (pintype "power_in"))
      (node (ref "U$1") (pin "D4") (pinfunction "VSS_D4_D4") (pintype "power_in"))
      (node (ref "U$1") (pin "E12") (pinfunction "VSS_E12_E12") (pintype "power_in"))
      (node (ref "U$1") (pin "E5") (pinfunction "VSS_E5_E5") (pintype "power_in"))
      (node (ref "U$1") (pin "F11") (pinfunction "VSS_F11_F11") (pintype "power_in"))
      (node (ref "U$1") (pin "F6") (pinfunction "VSS_F6_F6") (pintype "power_in"))
      (node (ref "U$1") (pin "H8") (pinfunction "VSS_H8_H8") (pintype "power_in"))
      (node (ref "U$1") (pin "H9") (pinfunction "VSS_H9_H9") (pintype "power_in"))
      (node (ref "U$1") (pin "J8") (pinfunction "VSS_J8_J8") (pintype "power_in"))
      (node (ref "U$1") (pin "J9") (pinfunction "VSS_J9_J9") (pintype "power_in"))
      (node (ref "U$1") (pin "L11") (pinfunction "VSS_L11_L11") (pintype "power_in"))
      (node (ref "U$1") (pin "L6") (pinfunction "VSS_L6_L6") (pintype "power_in"))
      (node (ref "U$1") (pin "M12") (pinfunction "VSS_M12_M12") (pintype "power_in"))
      (node (ref "U$1") (pin "M5") (pinfunction "VSS_M5_M5") (pintype "power_in"))
      (node (ref "U$1") (pin "N13") (pinfunction "VSS_N13_N13") (pintype "power_in"))
      (node (ref "U$1") (pin "N4") (pinfunction "VSS_N4_N4") (pintype "power_in"))
      (node (ref "U$1") (pin "P14") (pinfunction "VSS_P14_P14") (pintype "power_in"))
      (node (ref "U$1") (pin "P3") (pinfunction "VSS_P3_P3") (pintype "power_in"))
      (node (ref "U$1") (pin "R15") (pinfunction "VSS_R15_R15") (pintype "power_in"))
      (node (ref "U$1") (pin "R2") (pinfunction "VSS_R2_R2") (pintype "power_in"))
      (node (ref "U$10") (pin "1") (pinfunction "1_1") (pintype "passive"))
      (node (ref "U$11") (pin "1") (pinfunction "1_1") (pintype "passive"))
      (node (ref "U$14") (pin "10") (pinfunction "EPAD_2_10") (pintype "passive"))
      (node (ref "U$14") (pin "2") (pinfunction "GND_2") (pintype "passive"))
      (node (ref "U$14") (pin "9") (pinfunction "EPAD_1_9") (pintype "passive"))
      (node (ref "U$15") (pin "2") (pinfunction "GND_2") (pintype "bidirectional"))
      (node (ref "U$16") (pin "1") (pinfunction "GND_1") (pintype "power_in"))
      (node (ref "U$17") (pin "2") (pinfunction "GND_1_2") (pintype "power_in"))
      (node (ref "U$17") (pin "4") (pinfunction "GND_2_4") (pintype "power_in"))
      (node (ref "U$2") (pin "4") (pinfunction "GND2_4") (pintype "bidirectional"))
      (node (ref "U$20") (pin "1") (pinfunction "GND_1") (pintype "bidirectional"))
      (node (ref "U$22") (pin "1") (pinfunction "GND_1") (pintype "bidirectional"))
      (node (ref "U$23") (pin "15") (pinfunction "DGND_15") (pintype "bidirectional"))
      (node (ref "U$23") (pin "2") (pinfunction "AGND_2") (pintype "bidirectional"))
      (node (ref "U$23") (pin "25") (pinfunction "PAD1_25") (pintype "bidirectional"))
      (node (ref "U$23") (pin "26") (pinfunction "PAD2_26") (pintype "bidirectional"))
      (node (ref "U$27") (pin "11") (pinfunction "CKS_11") (pintype "bidirectional"))
      (node (ref "U$27") (pin "17") (pinfunction "GND_17") (pintype "bidirectional"))
      (node (ref "U$27") (pin "2") (pinfunction "D2S_2") (pintype "bidirectional"))
      (node (ref "U$27") (pin "5") (pinfunction "D1S_5") (pintype "bidirectional"))
      (node (ref "U$27") (pin "8") (pinfunction "D0S_8") (pintype "bidirectional"))
      (node (ref "U$3") (pin "2") (pinfunction "GND_2") (pintype "power_in"))
      (node (ref "U$4") (pin "2") (pinfunction "GND_2") (pintype "power_in"))
      (node (ref "U$5") (pin "2") (pinfunction "GND_2") (pintype "power_in"))
      (node (ref "U$6") (pin "2") (pinfunction "2_2") (pintype "passive"))
      (node (ref "U$7") (pin "1") (pinfunction "1_1") (pintype "passive"))
      (node (ref "U$8") (pin "1") (pinfunction "1_1") (pintype "passive"))
      (node (ref "U$9") (pin "1") (pinfunction "1_1") (pintype "passive"))
      (node (ref "U1") (pin "1") (pinfunction "1_GND_1") (pintype "power_in"))
      (node (ref "U1") (pin "10") (pinfunction "AGND_10") (pintype "power_in"))
      (node (ref "U1") (pin "11") (pinfunction "2_GND_11") (pintype "power_in"))
      (node (ref "U1") (pin "13") (pinfunction "TEST_13") (pintype "input"))
      (node (ref "U1") (pin "15") (pinfunction "3_GND_15") (pintype "power_in"))
      (node (ref "U1") (pin "25") (pinfunction "4_GND_25") (pintype "power_in"))
      (node (ref "U1") (pin "35") (pinfunction "5_GND_35") (pintype "power_in"))
      (node (ref "U1") (pin "47") (pinfunction "6_GND_47") (pintype "power_in"))
      (node (ref "U1") (pin "5") (pinfunction "7_GND_5") (pintype "power_in"))
      (node (ref "U1") (pin "51") (pinfunction "8_GND_51") (pintype "power_in"))
      (node (ref "U2") (pin "4") (pinfunction "GND_4") (pintype "power_in"))
      (node (ref "U4") (pin "2") (pinfunction "GND_2") (pintype "bidirectional"))
      (node (ref "U5") (pin "12") (pinfunction "2_VSSQ_12") (pintype "power_in"))
      (node (ref "U5") (pin "28") (pinfunction "1_VSS_28") (pintype "power_in"))
      (node (ref "U5") (pin "41") (pinfunction "2_VSS_41") (pintype "power_in"))
      (node (ref "U5") (pin "46") (pinfunction "3_VSSQ_46") (pintype "power_in"))
      (node (ref "U5") (pin "52") (pinfunction "4_VSSQ_52") (pintype "power_in"))
      (node (ref "U5") (pin "54") (pinfunction "3_VSS_54") (pintype "power_in"))
      (node (ref "U5") (pin "6") (pinfunction "1_VSSQ_6") (pintype "power_in"))
    )
    (net (code "38") (name "H11_IOT27A_OSC_CLK") (class "Default")
      (node (ref "R36") (pin "2") (pinfunction "2_2") (pintype "passive"))
      (node (ref "U$1") (pin "H11") (pinfunction "IOT27A/GCLKT_0/DQ14_H11") (pintype "bidirectional"))
    )
    (net (code "39") (name "HCEC") (class "Default")
      (node (ref "Q3") (pin "3") (pinfunction "D_3") (pintype "passive"))
      (node (ref "R135") (pin "2") (pinfunction "2_2") (pintype "passive"))
      (node (ref "U$27") (pin "13") (pinfunction "CEC_13") (pintype "bidirectional"))
      (node (ref "U$28") (pin "1") (pinfunction "IO1_1") (pintype "bidirectional"))
    )
    (net (code "40") (name "HDDC_SCL") (class "Default")
      (node (ref "Q4") (pin "3") (pinfunction "D_3") (pintype "passive"))
      (node (ref "R136") (pin "2") (pinfunction "2_2") (pintype "passive"))
      (node (ref "U$27") (pin "15") (pinfunction "SCL_15") (pintype "bidirectional"))
      (node (ref "U$28") (pin "2") (pinfunction "VN_2") (pintype "bidirectional"))
      (node (ref "U$28") (pin "6") (pinfunction "IO4_6") (pintype "bidirectional"))
    )
    (net (code "41") (name "HDDC_SDA") (class "Default")
      (node (ref "Q2") (pin "3") (pinfunction "D_3") (pintype "passive"))
      (node (ref "R137") (pin "2") (pinfunction "2_2") (pintype "passive"))
      (node (ref "U$27") (pin "16") (pinfunction "SDA_16") (pintype "bidirectional"))
      (node (ref "U$28") (pin "4") (pinfunction "IO3_4") (pintype "bidirectional"))
    )
    (net (code "42") (name "HDMI_3V3") (class "Default")
      (node (ref "C95") (pin "2") (pinfunction "2_2") (pintype "passive"))
      (node (ref "C96") (pin "2") (pinfunction "2_2") (pintype "passive"))
      (node (ref "R124") (pin "2") (pinfunction "2_2") (pintype "passive"))
      (node (ref "R125") (pin "2") (pinfunction "2_2") (pintype "passive"))
      (node (ref "R126") (pin "2") (pinfunction "2_2") (pintype "passive"))
      (node (ref "R127") (pin "2") (pinfunction "2_2") (pintype "passive"))
      (node (ref "R128") (pin "2") (pinfunction "2_2") (pintype "passive"))
      (node (ref "R129") (pin "2") (pinfunction "2_2") (pintype "passive"))
      (node (ref "R130") (pin "2") (pinfunction "2_2") (pintype "passive"))
      (node (ref "R131") (pin "2") (pinfunction "2_2") (pintype "passive"))
      (node (ref "U$25") (pin "1") (pinfunction "1_1") (pintype "bidirectional"))
    )
    (net (code "43") (name "HDMI_5V0") (class "Default")
      (node (ref "C97") (pin "2") (pinfunction "2_2") (pintype "passive"))
      (node (ref "C98") (pin "2") (pinfunction "2_2") (pintype "passive"))
      (node (ref "R135") (pin "1") (pinfunction "1_1") (pintype "passive"))
      (node (ref "R136") (pin "1") (pinfunction "1_1") (pintype "passive"))
      (node (ref "R137") (pin "1") (pinfunction "1_1") (pintype "passive"))
      (node (ref "U$26") (pin "1") (pinfunction "1_1") (pintype "bidirectional"))
      (node (ref "U$27") (pin "18") (pinfunction "+5V_18") (pintype "bidirectional"))
      (node (ref "U$28") (pin "5") (pinfunction "VP_5") (pintype "bidirectional"))
    )
    (net (code "44") (name "HDMI_CEC") (class "Default")
      (node (ref "R144") (pin "1") (pinfunction "1_1") (pintype "passive"))
      (node (ref "U$1") (pin "P16") (pinfunction "IOT48B/LVDS/DQS12_P16") (pintype "bidirectional"))
    )
    (net (code "45") (name "HDMI_HPD") (class "Default")
      (node (ref "R133") (pin "2") (pinfunction "2_2") (pintype "passive"))
      (node (ref "U$1") (pin "F12") (pinfunction "IOT12A/LVDS/DQ14_F12") (pintype "bidirectional"))
    )
    (net (code "46") (name "HDMI_TX0_N") (class "Default")
      (node (ref "C105") (pin "2") (pinfunction "2_2") (pintype "passive"))
      (node (ref "U$1") (pin "H14") (pinfunction "IOT20A/LVDS/DQ14_H14") (pintype "bidirectional"))
    )
    (net (code "47") (name "HDMI_TX0_P") (class "Default")
      (node (ref "C104") (pin "2") (pinfunction "2_2") (pintype "passive"))
      (node (ref "U$1") (pin "H15") (pinfunction "IOT16B/LVDS/DQ14_H15") (pintype "bidirectional"))
    )
    (net (code "48") (name "HDMI_TX1_N") (class "Default")
      (node (ref "C103") (pin "2") (pinfunction "2_2") (pintype "passive"))
      (node (ref "U$1") (pin "H16") (pinfunction "IOT20B/LVDS/DQ14_H16") (pintype "bidirectional"))
    )
    (net (code "49") (name "HDMI_TX1_P") (class "Default")
      (node (ref "C102") (pin "2") (pinfunction "2_2") (pintype "passive"))
      (node (ref "U$1") (pin "G14") (pinfunction "IOT13B/DQ14_G14") (pintype "bidirectional"))
    )
    (net (code "50") (name "HDMI_TX2_N") (class "Default")
      (node (ref "C101") (pin "2") (pinfunction "2_2") (pintype "passive"))
      (node (ref "U$1") (pin "G15") (pinfunction "IOT13A/DQ14_G15") (pintype "bidirectional"))
    )
    (net (code "51") (name "HDMI_TX2_P") (class "Default")
      (node (ref "C100") (pin "2") (pinfunction "2_2") (pintype "passive"))
      (node (ref "U$1") (pin "G16") (pinfunction "IOT16A/LVDS/DQ14_G16") (pintype "bidirectional"))
    )
    (net (code "52") (name "HDMI_TXC_N") (class "Default")
      (node (ref "C107") (pin "2") (pinfunction "2_2") (pintype "passive"))
      (node (ref "U$1") (pin "H13") (pinfunction "IOT18A/LVDS/DQ14_H13") (pintype "bidirectional"))
    )
    (net (code "53") (name "HDMI_TXC_P") (class "Default")
      (node (ref "C106") (pin "2") (pinfunction "2_2") (pintype "passive"))
      (node (ref "U$1") (pin "G13") (pinfunction "IOT12B/LVDS/DQ14_G13") (pintype "bidirectional"))
    )
    (net (code "54") (name "HHPD") (class "Default")
      (node (ref "R132") (pin "2") (pinfunction "2_2") (pintype "passive"))
      (node (ref "U$27") (pin "19") (pinfunction "HPD_19") (pintype "bidirectional"))
      (node (ref "U$28") (pin "3") (pinfunction "IO2_3") (pintype "bidirectional"))
    )
    (net (code "55") (name "H_CEC") (class "Default")
      (node (ref "Q3") (pin "2") (pinfunction "S_2") (pintype "passive"))
      (node (ref "R138") (pin "2") (pinfunction "2_2") (pintype "passive"))
      (node (ref "R144") (pin "2") (pinfunction "2_2") (pintype "passive"))
    )
    (net (code "56") (name "JTAG_TCK") (class "Default")
      (node (ref "D1") (pin "2") (pinfunction "2_INPUT_LINE_2") (pintype "passive"))
      (node (ref "D1") (pin "9") (pinfunction "2_OUTPUT_LINE_9") (pintype "passive"))
      (node (ref "J4") (pin "1") (pinfunction "1_1") (pintype "passive"))
      (node (ref "R93") (pin "1") (pinfunction "1_1") (pintype "passive"))
      (node (ref "U$1") (pin "A7") (pinfunction "IOR26A/TCK/LVDS/DQ10_A7") (pintype "bidirectional"))
    )
    (net (code "57") (name "JTAG_TDI") (class "Default")
      (node (ref "D1") (pin "4") (pinfunction "3_INPUT_LINE_4") (pintype "passive"))
      (node (ref "D1") (pin "7") (pinfunction "3_OUTPUT_LINE_7") (pintype "passive"))
      (node (ref "J4") (pin "4") (pinfunction "4_4") (pintype "passive"))
      (node (ref "R90") (pin "1") (pinfunction "1_1") (pintype "passive"))
      (node (ref "U$1") (pin "A6") (pinfunction "IOR26B/TDI/LVDS/DQ10_A6") (pintype "bidirectional"))
    )
    (net (code "58") (name "JTAG_TDO") (class "Default")
      (node (ref "D1") (pin "5") (pinfunction "4_INPUT_LINE_5") (pintype "passive"))
      (node (ref "D1") (pin "6") (pinfunction "4_OUTPUT_LINE_6") (pintype "passive"))
      (node (ref "J4") (pin "3") (pinfunction "3_3") (pintype "passive"))
      (node (ref "R91") (pin "1") (pinfunction "1_1") (pintype "passive"))
      (node (ref "U$1") (pin "C6") (pinfunction "IOR25A/TDO/DQ10_C6") (pintype "bidirectional"))
    )
    (net (code "59") (name "JTAG_TMS") (class "Default")
      (node (ref "D1") (pin "1") (pinfunction "1_INPUT_LINE_1") (pintype "passive"))
      (node (ref "D1") (pin "10") (pinfunction "1_OUTPUT_LINE_10") (pintype "passive"))
      (node (ref "J4") (pin "2") (pinfunction "2_2") (pintype "passive"))
      (node (ref "R92") (pin "1") (pinfunction "1_1") (pintype "passive"))
      (node (ref "U$1") (pin "B8") (pinfunction "IOR25B/TMS/DQ10_B8") (pintype "bidirectional"))
    )
    (net (code "60") (name "LCD_RS") (class "Default")
      (node (ref "U$1") (pin "T13") (pinfunction "IOR8B/RPLL1_C_FB/LVDS/DQ11_T13") (pintype "bidirectional"))
      (node (ref "U$14") (pin "4") (pinfunction "RS_4") (pintype "passive"))
    )
    (net (code "61") (name "LCD_SCL") (class "Default")
      (node (ref "R60") (pin "1") (pinfunction "1_1") (pintype "passive"))
      (node (ref "U$1") (pin "R13") (pinfunction "IOR20A/LVDS/DQ10_R13") (pintype "bidirectional"))
    )
    (net (code "62") (name "LCD_SDA") (class "Default")
      (node (ref "U$1") (pin "T14") (pinfunction "IOR20B/LVDS/DQ10_T14") (pintype "bidirectional"))
      (node (ref "U$14") (pin "5") (pinfunction "SDA_5") (pintype "passive"))
    )
    (net (code "63") (name "LCD_~{BL}") (class "Default")
      (node (ref "Q1") (pin "1") (pinfunction "G_1") (pintype "passive"))
      (node (ref "R59") (pin "2") (pinfunction "2_2") (pintype "passive"))
      (node (ref "U$1") (pin "T15") (pinfunction "IOR7A/RPLL1_T_IN/DQ11_T15") (pintype "bidirectional"))
    )
    (net (code "64") (name "LCD_~{CS}") (class "Default")
      (node (ref "U$1") (pin "R14") (pinfunction "IOR7B/RPLL1_C_IN/DQ11_R14") (pintype "bidirectional"))
      (node (ref "U$14") (pin "8") (pinfunction "CS_8") (pintype "passive"))
    )
    (net (code "65") (name "LCD_~{RST}") (class "Default")
      (node (ref "U$1") (pin "R12") (pinfunction "IOR11A/LVDS/DQ10_R12") (pintype "bidirectional"))
      (node (ref "U$14") (pin "3") (pinfunction "RESET_3") (pintype "passive"))
    )
    (net (code "66") (name "LED1") (class "Default")
      (node (ref "R18") (pin "1") (pinfunction "1_1") (pintype "passive"))
      (node (ref "R19") (pin "2") (pinfunction "2_2") (pintype "passive"))
      (node (ref "U$1") (pin "C13") (pinfunction "IOR32B/DONE/DQ9_C13") (pintype "bidirectional"))
    )
    (net (code "67") (name "LED2") (class "Default")
      (node (ref "R17") (pin "1") (pinfunction "1_1") (pintype "passive"))
      (node (ref "R20") (pin "2") (pinfunction "2_2") (pintype "passive"))
      (node (ref "U$1") (pin "A13") (pinfunction "IOR32A/READY/DQ9_A13") (pintype "bidirectional"))
    )
    (net (code "68") (name "LED3") (class "Default")
      (node (ref "R21") (pin "2") (pinfunction "2_2") (pintype "passive"))
      (node (ref "U$1") (pin "B12") (pinfunction "IOL7B/LPLL1_C_IN/DQ0_B12") (pintype "bidirectional"))
    )
    (net (code "69") (name "LED4") (class "Default")
      (node (ref "R22") (pin "2") (pinfunction "2_2") (pintype "passive"))
      (node (ref "U$1") (pin "B13") (pinfunction "IOL8A/LPLL1_T_FB/LVDS/DQ0_B13") (pintype "bidirectional"))
    )
    (net (code "70") (name "LED5") (class "Default")
      (node (ref "R23") (pin "2") (pinfunction "2_2") (pintype "passive"))
      (node (ref "U$1") (pin "A14") (pinfunction "IOL8B/LPLL1_C_FB/LVDS/DQ0_A14") (pintype "bidirectional"))
    )
    (net (code "71") (name "LED6") (class "Default")
      (node (ref "R24") (pin "2") (pinfunction "2_2") (pintype "passive"))
      (node (ref "U$1") (pin "A15") (pinfunction "IOL2B/LVDS/DQ0_A15") (pintype "bidirectional"))
    )
    (net (code "72") (name "LEDA") (class "Default")
      (node (ref "Q1") (pin "3") (pinfunction "D_3") (pintype "passive"))
      (node (ref "R58") (pin "1") (pinfunction "1_1") (pintype "passive"))
    )
    (net (code "73") (name "LED_ACT") (class "Default")
      (node (ref "IC1") (pin "24") (pinfunction "LED0/_PHYAD[0]/PMEB_24") (pintype "bidirectional"))
      (node (ref "R100") (pin "2") (pinfunction "2_2") (pintype "passive"))
      (node (ref "R95") (pin "2") (pinfunction "2_2") (pintype "passive"))
    )
    (net (code "74") (name "LED_LINK") (class "Default")
      (node (ref "IC1") (pin "25") (pinfunction "LED1/PHYAD[1]_25") (pintype "bidirectional"))
      (node (ref "R102") (pin "2") (pinfunction "2_2") (pintype "passive"))
      (node (ref "R94") (pin "2") (pinfunction "2_2") (pintype "passive"))
    )
    (net (code "75") (name "M16_MODE0") (class "Default")
      (node (ref "R13") (pin "2") (pinfunction "2_2") (pintype "passive"))
      (node (ref "U$1") (pin "M16") (pinfunction "MODE0_M16") (pintype "bidirectional"))
    )
    (net (code "76") (name "N$6") (class "Default")
      (node (ref "C16") (pin "1") (pinfunction "1_1") (pintype "passive"))
      (node (ref "U$2") (pin "2") (pinfunction "GND1_2") (pintype "bidirectional"))
    )
    (net (code "77") (name "Net-(C2-Pad2)") (class "Default")
      (node (ref "C2") (pin "2") (pinfunction "2_2") (pintype "passive"))
      (node (ref "C3") (pin "2") (pinfunction "2_2") (pintype "passive"))
      (node (ref "FB1") (pin "1") (pinfunction "1_1") (pintype "passive"))
      (node (ref "L1_2.2UH_2A") (pin "2") (pinfunction "2_2") (pintype "passive"))
      (node (ref "R4") (pin "1") (pinfunction "1_1") (pintype "passive"))
    )
    (net (code "78") (name "Net-(C5-Pad2)") (class "Default")
      (node (ref "C5") (pin "2") (pinfunction "2_2") (pintype "passive"))
      (node (ref "C6") (pin "2") (pinfunction "2_2") (pintype "passive"))
      (node (ref "FB2") (pin "1") (pinfunction "1_1") (pintype "passive"))
      (node (ref "L2_2.2UH_2A") (pin "2") (pinfunction "2_2") (pintype "passive"))
      (node (ref "R6") (pin "1") (pinfunction "1_1") (pintype "passive"))
    )
    (net (code "79") (name "Net-(C18-Pad2)") (class "Default")
      (node (ref "C18") (pin "2") (pinfunction "2_2") (pintype "passive"))
      (node (ref "C19") (pin "2") (pinfunction "2_2") (pintype "passive"))
      (node (ref "FB3") (pin "1") (pinfunction "1_1") (pintype "passive"))
      (node (ref "L3_2.2UH_2A") (pin "2") (pinfunction "2_2") (pintype "passive"))
      (node (ref "R8") (pin "1") (pinfunction "1_1") (pintype "passive"))
    )
    (net (code "80") (name "Net-(C99-Pad2)") (class "Default")
      (node (ref "C99") (pin "2") (pinfunction "2_2") (pintype "passive"))
      (node (ref "R132") (pin "1") (pinfunction "1_1") (pintype "passive"))
      (node (ref "R133") (pin "1") (pinfunction "1_1") (pintype "passive"))
      (node (ref "R134") (pin "1") (pinfunction "1_1") (pintype "passive"))
    )
    (net (code "81") (name "Net-(D6-1_INPUT_LINE)") (class "Default")
      (node (ref "C100") (pin "1") (pinfunction "1_1") (pintype "passive"))
      (node (ref "D6") (pin "1") (pinfunction "1_INPUT_LINE_1") (pintype "passive"))
      (node (ref "D6") (pin "10") (pinfunction "1_OUTPUT_LINE_10") (pintype "passive"))
      (node (ref "R124") (pin "1") (pinfunction "1_1") (pintype "passive"))
      (node (ref "U$27") (pin "1") (pinfunction "D2+_1") (pintype "bidirectional"))
    )
    (net (code "82") (name "Net-(D6-2_INPUT_LINE)") (class "Default")
      (node (ref "C101") (pin "1") (pinfunction "1_1") (pintype "passive"))
      (node (ref "D6") (pin "2") (pinfunction "2_INPUT_LINE_2") (pintype "passive"))
      (node (ref "D6") (pin "9") (pinfunction "2_OUTPUT_LINE_9") (pintype "passive"))
      (node (ref "R125") (pin "1") (pinfunction "1_1") (pintype "passive"))
      (node (ref "U$27") (pin "3") (pinfunction "D2-_3") (pintype "bidirectional"))
    )
    (net (code "83") (name "Net-(D6-3_INPUT_LINE)") (class "Default")
      (node (ref "C102") (pin "1") (pinfunction "1_1") (pintype "passive"))
      (node (ref "D6") (pin "4") (pinfunction "3_INPUT_LINE_4") (pintype "passive"))
      (node (ref "D6") (pin "7") (pinfunction "3_OUTPUT_LINE_7") (pintype "passive"))
      (node (ref "R126") (pin "1") (pinfunction "1_1") (pintype "passive"))
      (node (ref "U$27") (pin "4") (pinfunction "D1+_4") (pintype "bidirectional"))
    )
    (net (code "84") (name "Net-(D6-4_INPUT_LINE)") (class "Default")
      (node (ref "C103") (pin "1") (pinfunction "1_1") (pintype "passive"))
      (node (ref "D6") (pin "5") (pinfunction "4_INPUT_LINE_5") (pintype "passive"))
      (node (ref "D6") (pin "6") (pinfunction "4_OUTPUT_LINE_6") (pintype "passive"))
      (node (ref "R127") (pin "1") (pinfunction "1_1") (pintype "passive"))
      (node (ref "U$27") (pin "6") (pinfunction "D1-_6") (pintype "bidirectional"))
    )
    (net (code "85") (name "Net-(D7-1_INPUT_LINE)") (class "Default")
      (node (ref "C104") (pin "1") (pinfunction "1_1") (pintype "passive"))
      (node (ref "D7") (pin "1") (pinfunction "1_INPUT_LINE_1") (pintype "passive"))
      (node (ref "D7") (pin "10") (pinfunction "1_OUTPUT_LINE_10") (pintype "passive"))
      (node (ref "R128") (pin "1") (pinfunction "1_1") (pintype "passive"))
      (node (ref "U$27") (pin "7") (pinfunction "D0+_7") (pintype "bidirectional"))
    )
    (net (code "86") (name "Net-(D7-2_INPUT_LINE)") (class "Default")
      (node (ref "C105") (pin "1") (pinfunction "1_1") (pintype "passive"))
      (node (ref "D7") (pin "2") (pinfunction "2_INPUT_LINE_2") (pintype "passive"))
      (node (ref "D7") (pin "9") (pinfunction "2_OUTPUT_LINE_9") (pintype "passive"))
      (node (ref "R129") (pin "1") (pinfunction "1_1") (pintype "passive"))
      (node (ref "U$27") (pin "9") (pinfunction "D0-_9") (pintype "bidirectional"))
    )
    (net (code "87") (name "Net-(D7-3_INPUT_LINE)") (class "Default")
      (node (ref "C106") (pin "1") (pinfunction "1_1") (pintype "passive"))
      (node (ref "D7") (pin "4") (pinfunction "3_INPUT_LINE_4") (pintype "passive"))
      (node (ref "D7") (pin "7") (pinfunction "3_OUTPUT_LINE_7") (pintype "passive"))
      (node (ref "R130") (pin "1") (pinfunction "1_1") (pintype "passive"))
      (node (ref "U$27") (pin "10") (pinfunction "CK+_10") (pintype "bidirectional"))
    )
    (net (code "88") (name "Net-(D7-4_INPUT_LINE)") (class "Default")
      (node (ref "C107") (pin "1") (pinfunction "1_1") (pintype "passive"))
      (node (ref "D7") (pin "5") (pinfunction "4_INPUT_LINE_5") (pintype "passive"))
      (node (ref "D7") (pin "6") (pinfunction "4_OUTPUT_LINE_6") (pintype "passive"))
      (node (ref "R131") (pin "1") (pinfunction "1_1") (pintype "passive"))
      (node (ref "U$27") (pin "12") (pinfunction "CK-_12") (pintype "bidirectional"))
    )
    (net (code "89") (name "Net-(FB-2)") (class "Default")
      (node (ref "C64") (pin "2") (pinfunction "2_2") (pintype "passive"))
      (node (ref "FB") (pin "P$2") (pinfunction "2_P$2") (pintype "bidirectional"))
      (node (ref "U$15") (pin "1") (pinfunction "~{ST}_1") (pintype "bidirectional"))
      (node (ref "U$15") (pin "4") (pinfunction "VCC_4") (pintype "bidirectional"))
    )
    (net (code "90") (name "Net-(IC1-AVDD10OUT)") (class "Default")
      (node (ref "C46") (pin "1") (pinfunction "1_1") (pintype "passive"))
      (node (ref "IC1") (pin "2") (pinfunction "AVDD10OUT_2") (pintype "bidirectional"))
    )
    (net (code "91") (name "Net-(IC1-DVDD10OUT)") (class "Default")
      (node (ref "C50") (pin "2") (pinfunction "2_2") (pintype "passive"))
      (node (ref "IC1") (pin "29") (pinfunction "DVDD10OUT_29") (pintype "bidirectional"))
    )
    (net (code "92") (name "Net-(IC1-RSET)") (class "Default")
      (node (ref "IC1") (pin "1") (pinfunction "RSET_1") (pintype "bidirectional"))
      (node (ref "R97") (pin "2") (pinfunction "2_2") (pintype "passive"))
    )
    (net (code "93") (name "Net-(IC1-RXDV)") (class "Default")
      (node (ref "IC1") (pin "8") (pinfunction "RXDV_8") (pintype "bidirectional"))
      (node (ref "R98") (pin "2") (pinfunction "2_2") (pintype "passive"))
    )
    (net (code "94") (name "Net-(J1A-CC1)") (class "Default")
      (node (ref "J1") (pin "A5") (pinfunction "CC1_A5") (pintype "passive"))
      (node (ref "R10") (pin "2") (pinfunction "2_2") (pintype "passive"))
    )
    (net (code "95") (name "Net-(J1A-CC2)") (class "Default")
      (node (ref "J1") (pin "B5") (pinfunction "CC2_B5") (pintype "passive"))
      (node (ref "R11") (pin "2") (pinfunction "2_2") (pintype "passive"))
    )
    (net (code "96") (name "Net-(J2-CD{slash}DAT3)") (class "Default")
      (node (ref "J2") (pin "2") (pinfunction "CD/DAT3_2") (pintype "bidirectional"))
      (node (ref "R31") (pin "2") (pinfunction "2_2") (pintype "passive"))
      (node (ref "R63") (pin "1") (pinfunction "1_1") (pintype "passive"))
    )
    (net (code "97") (name "Net-(J2-CLK)") (class "Default")
      (node (ref "J2") (pin "5") (pinfunction "CLK_5") (pintype "bidirectional"))
      (node (ref "R48") (pin "2") (pinfunction "2_2") (pintype "passive"))
    )
    (net (code "98") (name "Net-(J2-CMD)") (class "Default")
      (node (ref "J2") (pin "3") (pinfunction "CMD_3") (pintype "bidirectional"))
      (node (ref "R32") (pin "2") (pinfunction "2_2") (pintype "passive"))
      (node (ref "R47") (pin "2") (pinfunction "2_2") (pintype "passive"))
    )
    (net (code "99") (name "Net-(J2-DAT0)") (class "Default")
      (node (ref "J2") (pin "7") (pinfunction "DAT0_7") (pintype "bidirectional"))
      (node (ref "R33") (pin "2") (pinfunction "2_2") (pintype "passive"))
      (node (ref "R49") (pin "2") (pinfunction "2_2") (pintype "passive"))
    )
    (net (code "100") (name "Net-(J2-DAT1)") (class "Default")
      (node (ref "J2") (pin "8") (pinfunction "DAT1_8") (pintype "bidirectional"))
      (node (ref "R34") (pin "2") (pinfunction "2_2") (pintype "passive"))
      (node (ref "R50") (pin "2") (pinfunction "2_2") (pintype "passive"))
    )
    (net (code "101") (name "Net-(J2-DAT2)") (class "Default")
      (node (ref "J2") (pin "1") (pinfunction "DAT2_1") (pintype "bidirectional"))
      (node (ref "R158") (pin "1") (pinfunction "1_1") (pintype "passive"))
      (node (ref "R30") (pin "2") (pinfunction "2_2") (pintype "passive"))
    )
    (net (code "102") (name "Net-(J2-SW_B)") (class "Default")
      (node (ref "C63") (pin "2") (pinfunction "2_2") (pintype "passive"))
      (node (ref "J2") (pin "10") (pinfunction "SW_B_10") (pintype "bidirectional"))
    )
    (net (code "103") (name "Net-(J3-GA)") (class "Default")
      (node (ref "D4") (pin "1") (pinfunction "1_1") (pintype "passive"))
      (node (ref "J3") (pin "9") (pinfunction "GA_9") (pintype "passive"))
      (node (ref "R94") (pin "1") (pinfunction "1_1") (pintype "passive"))
    )
    (net (code "104") (name "Net-(J3-P4)") (class "Default")
      (node (ref "C80") (pin "2") (pinfunction "2_2") (pintype "passive"))
      (node (ref "J3") (pin "4") (pinfunction "P4_4") (pintype "passive"))
    )
    (net (code "105") (name "Net-(J3-P5)") (class "Default")
      (node (ref "C79") (pin "2") (pinfunction "2_2") (pintype "passive"))
      (node (ref "J3") (pin "5") (pinfunction "P5_5") (pintype "passive"))
    )
    (net (code "106") (name "Net-(J3-YC)") (class "Default")
      (node (ref "D5") (pin "1") (pinfunction "1_1") (pintype "passive"))
      (node (ref "J3") (pin "11") (pinfunction "YC_11") (pintype "passive"))
      (node (ref "R95") (pin "1") (pinfunction "1_1") (pintype "passive"))
    )
    (net (code "107") (name "Net-(LED1-PadC)") (class "Default")
      (node (ref "LED1") (pin "C") (pinfunction "C_C") (pintype "passive"))
      (node (ref "R12") (pin "1") (pinfunction "1_1") (pintype "passive"))
    )
    (net (code "108") (name "Net-(LED2-PadC)") (class "Default")
      (node (ref "LED2") (pin "C") (pinfunction "C_C") (pintype "passive"))
      (node (ref "R19") (pin "1") (pinfunction "1_1") (pintype "passive"))
    )
    (net (code "109") (name "Net-(LED3-PadC)") (class "Default")
      (node (ref "LED3") (pin "C") (pinfunction "C_C") (pintype "passive"))
      (node (ref "R20") (pin "1") (pinfunction "1_1") (pintype "passive"))
    )
    (net (code "110") (name "Net-(LED4-PadC)") (class "Default")
      (node (ref "LED4") (pin "C") (pinfunction "C_C") (pintype "passive"))
      (node (ref "R21") (pin "1") (pinfunction "1_1") (pintype "passive"))
    )
    (net (code "111") (name "Net-(LED5-PadC)") (class "Default")
      (node (ref "LED5") (pin "C") (pinfunction "C_C") (pintype "passive"))
      (node (ref "R22") (pin "1") (pinfunction "1_1") (pintype "passive"))
    )
    (net (code "112") (name "Net-(LED6-PadC)") (class "Default")
      (node (ref "LED6") (pin "C") (pinfunction "C_C") (pintype "passive"))
      (node (ref "R23") (pin "1") (pinfunction "1_1") (pintype "passive"))
    )
    (net (code "113") (name "Net-(LED7-PadC)") (class "Default")
      (node (ref "LED7") (pin "C") (pinfunction "C_C") (pintype "passive"))
      (node (ref "R24") (pin "1") (pinfunction "1_1") (pintype "passive"))
    )
    (net (code "114") (name "Net-(LED8-PadC)") (class "Default")
      (node (ref "LED8") (pin "C") (pinfunction "C_C") (pintype "passive"))
      (node (ref "R156") (pin "1") (pinfunction "1_1") (pintype "passive"))
    )
    (net (code "115") (name "Net-(LED9-PadC)") (class "Default")
      (node (ref "LED9") (pin "C") (pinfunction "C_C") (pintype "passive"))
      (node (ref "R157") (pin "1") (pinfunction "1_1") (pintype "passive"))
    )
    (net (code "116") (name "Net-(Q2-G)") (class "Default")
      (node (ref "Q2") (pin "1") (pinfunction "G_1") (pintype "passive"))
      (node (ref "R143") (pin "2") (pinfunction "2_2") (pintype "passive"))
    )
    (net (code "117") (name "Net-(Q3-G)") (class "Default")
      (node (ref "Q3") (pin "1") (pinfunction "G_1") (pintype "passive"))
      (node (ref "R141") (pin "2") (pinfunction "2_2") (pintype "passive"))
    )
    (net (code "118") (name "Net-(Q4-G)") (class "Default")
      (node (ref "Q4") (pin "1") (pinfunction "G_1") (pintype "passive"))
      (node (ref "R142") (pin "2") (pinfunction "2_2") (pintype "passive"))
    )
    (net (code "119") (name "Net-(R37-Pad2)") (class "Default")
      (node (ref "R37") (pin "2") (pinfunction "2_2") (pintype "passive"))
      (node (ref "U$13") (pin "1") (pinfunction "1_1") (pintype "passive"))
    )
    (net (code "120") (name "Net-(R38-Pad2)") (class "Default")
      (node (ref "R38") (pin "2") (pinfunction "2_2") (pintype "passive"))
      (node (ref "U$13") (pin "2") (pinfunction "2_2") (pintype "passive"))
    )
    (net (code "121") (name "Net-(R39-Pad2)") (class "Default")
      (node (ref "R39") (pin "2") (pinfunction "2_2") (pintype "passive"))
      (node (ref "U$13") (pin "3") (pinfunction "3_3") (pintype "passive"))
    )
    (net (code "122") (name "Net-(R40-Pad2)") (class "Default")
      (node (ref "R40") (pin "2") (pinfunction "2_2") (pintype "passive"))
      (node (ref "U$13") (pin "4") (pinfunction "4_4") (pintype "passive"))
    )
    (net (code "123") (name "Net-(R41-Pad2)") (class "Default")
      (node (ref "R41") (pin "2") (pinfunction "2_2") (pintype "passive"))
      (node (ref "U$13") (pin "5") (pinfunction "5_5") (pintype "passive"))
    )
    (net (code "124") (name "Net-(U$1I-EXTR)") (class "Default")
      (node (ref "R_EXTR") (pin "1") (pinfunction "1_1") (pintype "passive"))
      (node (ref "U$1") (pin "L7") (pinfunction "EXTR_L7") (pintype "power_in"))
    )
    (net (code "125") (name "Net-(U$3-FB)") (class "Default")
      (node (ref "R4") (pin "2") (pinfunction "2_2") (pintype "passive"))
      (node (ref "R5") (pin "1") (pinfunction "1_1") (pintype "passive"))
      (node (ref "U$3") (pin "5") (pinfunction "FB_5") (pintype "bidirectional"))
    )
    (net (code "126") (name "Net-(U$3-SW)") (class "Default")
      (node (ref "L1_2.2UH_2A") (pin "1") (pinfunction "1_1") (pintype "passive"))
      (node (ref "U$3") (pin "3") (pinfunction "SW_3") (pintype "bidirectional"))
    )
    (net (code "127") (name "Net-(U$4-FB)") (class "Default")
      (node (ref "R6") (pin "2") (pinfunction "2_2") (pintype "passive"))
      (node (ref "R7") (pin "1") (pinfunction "1_1") (pintype "passive"))
      (node (ref "U$4") (pin "5") (pinfunction "FB_5") (pintype "bidirectional"))
    )
    (net (code "128") (name "Net-(U$4-SW)") (class "Default")
      (node (ref "L2_2.2UH_2A") (pin "1") (pinfunction "1_1") (pintype "passive"))
      (node (ref "U$4") (pin "3") (pinfunction "SW_3") (pintype "bidirectional"))
    )
    (net (code "129") (name "Net-(U$5-FB)") (class "Default")
      (node (ref "R8") (pin "2") (pinfunction "2_2") (pintype "passive"))
      (node (ref "R9") (pin "1") (pinfunction "1_1") (pintype "passive"))
      (node (ref "U$5") (pin "5") (pinfunction "FB_5") (pintype "bidirectional"))
    )
    (net (code "130") (name "Net-(U$5-SW)") (class "Default")
      (node (ref "L3_2.2UH_2A") (pin "1") (pinfunction "1_1") (pintype "passive"))
      (node (ref "U$5") (pin "3") (pinfunction "SW_3") (pintype "bidirectional"))
    )
    (net (code "131") (name "Net-(U$14-LEDA)") (class "Default")
      (node (ref "R58") (pin "2") (pinfunction "2_2") (pintype "passive"))
      (node (ref "U$14") (pin "1") (pinfunction "LEDA_1") (pintype "passive"))
    )
    (net (code "132") (name "Net-(U$15-OUT)") (class "Default")
      (node (ref "R36") (pin "1") (pinfunction "1_1") (pintype "passive"))
      (node (ref "U$15") (pin "3") (pinfunction "OUT_3") (pintype "bidirectional"))
    )
    (net (code "133") (name "Net-(U$20-VIN)") (class "Default")
      (node (ref "C85") (pin "2") (pinfunction "2_2") (pintype "passive"))
      (node (ref "FB8") (pin "1") (pinfunction "1_1") (pintype "passive"))
      (node (ref "U$20") (pin "3") (pinfunction "VIN_3") (pintype "bidirectional"))
    )
    (net (code "134") (name "Net-(U1-1_VCORE)") (class "Default")
      (node (ref "C10") (pin "2") (pinfunction "2_2") (pintype "passive"))
      (node (ref "C9") (pin "2") (pinfunction "2_2") (pintype "passive"))
      (node (ref "U1") (pin "12") (pinfunction "1_VCORE_12") (pintype "power_in"))
      (node (ref "U1") (pin "37") (pinfunction "2_VCORE_37") (pintype "power_in"))
      (node (ref "U1") (pin "49") (pinfunction "VREGOUT_49") (pintype "power_in"))
      (node (ref "U1") (pin "64") (pinfunction "3_VCORE_64") (pintype "power_in"))
    )
    (net (code "135") (name "Net-(U1-ADBUS0)") (class "Default")
      (node (ref "R1") (pin "2") (pinfunction "2_2") (pintype "passive"))
      (node (ref "R93") (pin "2") (pinfunction "2_2") (pintype "passive"))
      (node (ref "U1") (pin "16") (pinfunction "ADBUS0_16") (pintype "bidirectional"))
    )
    (net (code "136") (name "Net-(U1-ADBUS1)") (class "Default")
      (node (ref "R90") (pin "2") (pinfunction "2_2") (pintype "passive"))
      (node (ref "U1") (pin "17") (pinfunction "ADBUS1_17") (pintype "bidirectional"))
    )
    (net (code "137") (name "Net-(U1-ADBUS2)") (class "Default")
      (node (ref "R91") (pin "2") (pinfunction "2_2") (pintype "passive"))
      (node (ref "U1") (pin "18") (pinfunction "ADBUS2_18") (pintype "bidirectional"))
    )
    (net (code "138") (name "Net-(U1-ADBUS3)") (class "Default")
      (node (ref "R92") (pin "2") (pinfunction "2_2") (pintype "passive"))
      (node (ref "U1") (pin "19") (pinfunction "ADBUS3_19") (pintype "bidirectional"))
    )
    (net (code "139") (name "Net-(U1-REF)") (class "Default")
      (node (ref "R3") (pin "2") (pinfunction "2_2") (pintype "passive"))
      (node (ref "U1") (pin "6") (pinfunction "REF_6") (pintype "input"))
    )
    (net (code "140") (name "Net-(U1-RESET#)") (class "Default")
      (node (ref "C57") (pin "1") (pinfunction "1_1") (pintype "passive"))
      (node (ref "R2") (pin "2") (pinfunction "2_2") (pintype "passive"))
      (node (ref "U1") (pin "14") (pinfunction "RESET#_14") (pintype "input"))
    )
    (net (code "141") (name "Net-(U2-CLK)") (class "Default")
      (node (ref "R55") (pin "2") (pinfunction "2_2") (pintype "passive"))
      (node (ref "R57") (pin "2") (pinfunction "2_2") (pintype "passive"))
      (node (ref "U2") (pin "6") (pinfunction "CLK_6") (pintype "input"))
    )
    (net (code "142") (name "Net-(U2-DI(IO0))") (class "Default")
      (node (ref "R54") (pin "1") (pinfunction "1_1") (pintype "passive"))
      (node (ref "U2") (pin "5") (pinfunction "DI(IO0)_5") (pintype "bidirectional"))
    )
    (net (code "143") (name "Net-(U2-DO(IO1))") (class "Default")
      (node (ref "R53") (pin "1") (pinfunction "1_1") (pintype "passive"))
      (node (ref "U2") (pin "2") (pinfunction "DO(IO1)_2") (pintype "bidirectional"))
    )
    (net (code "144") (name "Net-(U2-~{CS})") (class "Default")
      (node (ref "R56") (pin "2") (pinfunction "2_2") (pintype "passive"))
      (node (ref "U2") (pin "1") (pinfunction "~{CS}_1") (pintype "input"))
    )
    (net (code "145") (name "Net-(U2-~{HOLD}{slash}~{RESET}{slash}IO3)") (class "Default")
      (node (ref "R51") (pin "1") (pinfunction "1_1") (pintype "passive"))
      (node (ref "U2") (pin "7") (pinfunction "~{HOLD}/~{RESET}/IO3_7") (pintype "bidirectional"))
    )
    (net (code "146") (name "Net-(U2-~{WP}(IO2))") (class "Default")
      (node (ref "R52") (pin "1") (pinfunction "1_1") (pintype "passive"))
      (node (ref "U2") (pin "3") (pinfunction "~{WP}(IO2)_3") (pintype "bidirectional"))
    )
    (net (code "147") (name "Net-(U4-DIR)") (class "Default")
      (node (ref "R121") (pin "1") (pinfunction "1_1") (pintype "passive"))
      (node (ref "U4") (pin "5") (pinfunction "DIR_5") (pintype "bidirectional"))
    )
    (net (code "148") (name "OSCI") (class "Default")
      (node (ref "C16") (pin "2") (pinfunction "2_2") (pintype "passive"))
      (node (ref "U$2") (pin "1") (pinfunction "XIN_1") (pintype "bidirectional"))
      (node (ref "U1") (pin "2") (pinfunction "OSCI_2") (pintype "input"))
    )
    (net (code "149") (name "OSCO") (class "Default")
      (node (ref "C15") (pin "2") (pinfunction "2_2") (pintype "passive"))
      (node (ref "U$2") (pin "3") (pinfunction "XOUT_3") (pintype "bidirectional"))
      (node (ref "U1") (pin "3") (pinfunction "OSCO_3") (pintype "output"))
    )
    (net (code "150") (name "PHY_CRS{slash}CRS_DV") (class "Default")
      (node (ref "IC1") (pin "26") (pinfunction "CRS/CRS_DV_26") (pintype "bidirectional"))
      (node (ref "R114") (pin "2") (pinfunction "2_2") (pintype "passive"))
    )
    (net (code "151") (name "PHY_MDC") (class "Default")
      (node (ref "IC1") (pin "22") (pinfunction "MDC_22") (pintype "bidirectional"))
      (node (ref "R112") (pin "2") (pinfunction "2_2") (pintype "passive"))
    )
    (net (code "152") (name "PHY_MDIO") (class "Default")
      (node (ref "IC1") (pin "23") (pinfunction "MDI_O_23") (pintype "bidirectional"))
      (node (ref "R113") (pin "2") (pinfunction "2_2") (pintype "passive"))
    )
    (net (code "153") (name "PHY_RXD0") (class "Default")
      (node (ref "IC1") (pin "9") (pinfunction "RXD[0]_9") (pintype "bidirectional"))
      (node (ref "R117") (pin "2") (pinfunction "2_2") (pintype "passive"))
    )
    (net (code "154") (name "PHY_RXD1") (class "Default")
      (node (ref "IC1") (pin "10") (pinfunction "RXD[1]_10") (pintype "bidirectional"))
      (node (ref "R118") (pin "2") (pinfunction "2_2") (pintype "passive"))
      (node (ref "R99") (pin "2") (pinfunction "2_2") (pintype "passive"))
    )
    (net (code "155") (name "PHY_RXER{slash}FXEN") (class "Default")
      (node (ref "IC1") (pin "28") (pinfunction "RXER/FXEN_28") (pintype "bidirectional"))
      (node (ref "R103") (pin "1") (pinfunction "1_1") (pintype "passive"))
      (node (ref "R115") (pin "2") (pinfunction "2_2") (pintype "passive"))
    )
    (net (code "156") (name "PHY_TXCLK") (class "Default")
      (node (ref "IC1") (pin "15") (pinfunction "TXC_15") (pintype "bidirectional"))
      (node (ref "R108") (pin "2") (pinfunction "2_2") (pintype "passive"))
    )
    (net (code "157") (name "PHY_TXD0") (class "Default")
      (node (ref "IC1") (pin "16") (pinfunction "TXD[0]_16") (pintype "bidirectional"))
      (node (ref "R109") (pin "2") (pinfunction "2_2") (pintype "passive"))
    )
    (net (code "158") (name "PHY_TXD1") (class "Default")
      (node (ref "IC1") (pin "17") (pinfunction "TXD[1]_17") (pintype "bidirectional"))
      (node (ref "R110") (pin "2") (pinfunction "2_2") (pintype "passive"))
    )
    (net (code "159") (name "PHY_TXEN") (class "Default")
      (node (ref "IC1") (pin "20") (pinfunction "TXEN_20") (pintype "bidirectional"))
      (node (ref "R116") (pin "2") (pinfunction "2_2") (pintype "passive"))
    )
    (net (code "160") (name "PHY_~{RST}") (class "Default")
      (node (ref "C49") (pin "1") (pinfunction "1_1") (pintype "passive"))
      (node (ref "IC1") (pin "21") (pinfunction "PHYRSTB_21") (pintype "bidirectional"))
      (node (ref "R101") (pin "2") (pinfunction "2_2") (pintype "passive"))
      (node (ref "R111") (pin "2") (pinfunction "2_2") (pintype "passive"))
    )
    (net (code "161") (name "RTL_PHY_CRS{slash}CRS_DV") (class "Default")
      (node (ref "R114") (pin "1") (pinfunction "1_1") (pintype "passive"))
      (node (ref "U$1") (pin "C16") (pinfunction "IOT5A/DQ15_C16") (pintype "bidirectional"))
    )
    (net (code "162") (name "RTL_PHY_MDC{slash}DVP_SCL{slash}HDMI_SDA") (class "Default")
      (node (ref "Q2") (pin "2") (pinfunction "S_2") (pintype "passive"))
      (node (ref "R112") (pin "1") (pinfunction "1_1") (pintype "passive"))
      (node (ref "R140") (pin "2") (pinfunction "2_2") (pintype "passive"))
      (node (ref "U$1") (pin "F14") (pinfunction "IOT9A/DQS15_F14") (pintype "bidirectional"))
      (node (ref "U$24") (pin "P$6") (pinfunction "D1_P$6") (pintype "passive"))
    )
    (net (code "163") (name "RTL_PHY_MDIO{slash}DVP_SDA{slash}HDMI_SCL") (class "Default")
      (node (ref "Q4") (pin "2") (pinfunction "S_2") (pintype "passive"))
      (node (ref "R113") (pin "1") (pinfunction "1_1") (pintype "passive"))
      (node (ref "R139") (pin "2") (pinfunction "2_2") (pintype "passive"))
      (node (ref "U$1") (pin "F16") (pinfunction "IOT9B/DQS15_F16") (pintype "bidirectional"))
      (node (ref "U$24") (pin "P$3") (pinfunction "D2_P$3") (pintype "passive"))
    )
    (net (code "164") (name "RTL_PHY_RXD0") (class "Default")
      (node (ref "R117") (pin "1") (pinfunction "1_1") (pintype "passive"))
      (node (ref "U$1") (pin "D8") (pinfunction "IOL38A/LVDS/DQ2_D8") (pintype "bidirectional"))
    )
    (net (code "165") (name "RTL_PHY_RXD1") (class "Default")
      (node (ref "R118") (pin "1") (pinfunction "1_1") (pintype "passive"))
      (node (ref "U$1") (pin "D9") (pinfunction "IOL35B/LVDS/DQ2_D9") (pintype "bidirectional"))
    )
    (net (code "166") (name "RTL_PHY_RXER{slash}FXEN") (class "Default")
      (node (ref "R115") (pin "1") (pinfunction "1_1") (pintype "passive"))
      (node (ref "U$1") (pin "D15") (pinfunction "IOT5B/DQ15_D15") (pintype "bidirectional"))
    )
    (net (code "167") (name "RTL_PHY_TXCLK") (class "Default")
      (node (ref "R108") (pin "1") (pinfunction "1_1") (pintype "passive"))
      (node (ref "U$1") (pin "C8") (pinfunction "IOL29A/GCLKT_6/LVDS/DQ2_C8") (pintype "bidirectional"))
    )
    (net (code "168") (name "RTL_PHY_TXD0") (class "Default")
      (node (ref "R109") (pin "1") (pinfunction "1_1") (pintype "passive"))
      (node (ref "U$1") (pin "D10") (pinfunction "IOL17A/LVDS/DQ1_D10") (pintype "bidirectional"))
    )
    (net (code "169") (name "RTL_PHY_TXD1") (class "Default")
      (node (ref "R110") (pin "1") (pinfunction "1_1") (pintype "passive"))
      (node (ref "U$1") (pin "A11") (pinfunction "IOL15A/LVDS/DQ1_A11") (pintype "bidirectional"))
    )
    (net (code "170") (name "RTL_PHY_TXEN") (class "Default")
      (node (ref "R116") (pin "1") (pinfunction "1_1") (pintype "passive"))
      (node (ref "U$1") (pin "B11") (pinfunction "IOL13A/LVDS/DQ1_B11") (pintype "bidirectional"))
    )
    (net (code "171") (name "RTL_PHY_~{RST}") (class "Default")
      (node (ref "R111") (pin "1") (pinfunction "1_1") (pintype "passive"))
      (node (ref "U$1") (pin "A12") (pinfunction "IOL13B/LVDS/DQ1_A12") (pintype "bidirectional"))
    )
    (net (code "172") (name "RX0_N") (class "Default")
      (node (ref "IC1") (pin "6") (pinfunction "MDI_-[1]_6") (pintype "bidirectional"))
      (node (ref "R107") (pin "2") (pinfunction "2_2") (pintype "passive"))
    )
    (net (code "173") (name "RX0_P") (class "Default")
      (node (ref "IC1") (pin "5") (pinfunction "MDI+[1]_5") (pintype "bidirectional"))
      (node (ref "R106") (pin "2") (pinfunction "2_2") (pintype "passive"))
    )
    (net (code "174") (name "RX_N") (class "Default")
      (node (ref "J3") (pin "6") (pinfunction "RD-_6") (pintype "passive"))
      (node (ref "R107") (pin "1") (pinfunction "1_1") (pintype "passive"))
      (node (ref "U$18") (pin "1") (pinfunction "1_1") (pintype "bidirectional"))
    )
    (net (code "175") (name "RX_P") (class "Default")
      (node (ref "J3") (pin "3") (pinfunction "RD+_3") (pintype "passive"))
      (node (ref "R106") (pin "1") (pinfunction "1_1") (pintype "passive"))
      (node (ref "U$18") (pin "2") (pinfunction "2_2") (pintype "bidirectional"))
    )
    (net (code "176") (name "SCL") (class "Default")
      (node (ref "R60") (pin "2") (pinfunction "2_2") (pintype "passive"))
      (node (ref "U$14") (pin "6") (pinfunction "SCL_6") (pintype "passive"))
    )
    (net (code "177") (name "SDRAM_A0") (class "Default")
      (node (ref "U$1") (pin "E2") (pinfunction "IOB12A/LVDS/DQ5_E2") (pintype "bidirectional"))
      (node (ref "U5") (pin "23") (pinfunction "A0_23") (pintype "input"))
    )
    (net (code "178") (name "SDRAM_A1") (class "Default")
      (node (ref "U$1") (pin "D1") (pinfunction "IOB9B/DQS4_D1") (pintype "bidirectional"))
      (node (ref "U5") (pin "24") (pinfunction "A1_24") (pintype "input"))
    )
    (net (code "179") (name "SDRAM_A2") (class "Default")
      (node (ref "U$1") (pin "D2") (pinfunction "IOB14B/LVDS/DQ5_D2") (pintype "bidirectional"))
      (node (ref "U5") (pin "25") (pinfunction "A2_25") (pintype "input"))
    )
    (net (code "180") (name "SDRAM_A3") (class "Default")
      (node (ref "U$1") (pin "C1") (pinfunction "IOB14A/LVDS/DQ5_C1") (pintype "bidirectional"))
      (node (ref "U5") (pin "26") (pinfunction "A3_26") (pintype "input"))
    )
    (net (code "181") (name "SDRAM_A4") (class "Default")
      (node (ref "U$1") (pin "J1") (pinfunction "IOB27A/GCLKT_5/DQ5_J1") (pintype "bidirectional"))
      (node (ref "U5") (pin "29") (pinfunction "A4_29") (pintype "input"))
    )
    (net (code "182") (name "SDRAM_A5") (class "Default")
      (node (ref "U$1") (pin "J2") (pinfunction "IOB34A/LVDS/DQ6_J2") (pintype "bidirectional"))
      (node (ref "U5") (pin "30") (pinfunction "A5_30") (pintype "input"))
    )
    (net (code "183") (name "SDRAM_A6") (class "Default")
      (node (ref "U$1") (pin "K1") (pinfunction "IOB34B/LVDS/DQ6_K1") (pintype "bidirectional"))
      (node (ref "U5") (pin "31") (pinfunction "A6_31") (pintype "input"))
    )
    (net (code "184") (name "SDRAM_A7") (class "Default")
      (node (ref "U$1") (pin "K2") (pinfunction "IOB36B/LVDS/DQ6_K2") (pintype "bidirectional"))
      (node (ref "U5") (pin "32") (pinfunction "A7_32") (pintype "input"))
    )
    (net (code "185") (name "SDRAM_A8") (class "Default")
      (node (ref "U$1") (pin "L1") (pinfunction "IOB38A/LVDS/DQ6_L1") (pintype "bidirectional"))
      (node (ref "U5") (pin "33") (pinfunction "A8_33") (pintype "input"))
    )
    (net (code "186") (name "SDRAM_A9") (class "Default")
      (node (ref "U$1") (pin "L2") (pinfunction "IOB30A/GCLKT_4/LVDS/DQ6_L2") (pintype "bidirectional"))
      (node (ref "U5") (pin "34") (pinfunction "A9_34") (pintype "input"))
    )
    (net (code "187") (name "SDRAM_A10") (class "Default")
      (node (ref "U$1") (pin "E1") (pinfunction "IOB16A/LVDS/DQ5_E1") (pintype "bidirectional"))
      (node (ref "U5") (pin "22") (pinfunction "A10_22") (pintype "input"))
    )
    (net (code "188") (name "SDRAM_A11") (class "Default")
      (node (ref "U$1") (pin "M1") (pinfunction "IOB30B/GCLKC_4/LVDS/DQ6_M1") (pintype "bidirectional"))
      (node (ref "U5") (pin "35") (pinfunction "A11_35") (pintype "input"))
    )
    (net (code "189") (name "SDRAM_A12") (class "Default")
      (node (ref "U$1") (pin "M2") (pinfunction "IOB43A/DQ6_M2") (pintype "bidirectional"))
      (node (ref "U5") (pin "36") (pinfunction "A12_36") (pintype "input"))
    )
    (net (code "190") (name "SDRAM_BA0") (class "Default")
      (node (ref "U$1") (pin "F1") (pinfunction "IOB19B/DQ5_F1") (pintype "bidirectional"))
      (node (ref "U5") (pin "20") (pinfunction "BA0_20") (pintype "input"))
    )
    (net (code "191") (name "SDRAM_BA1") (class "Default")
      (node (ref "U$1") (pin "F2") (pinfunction "IOB16B/LVDS/DQ5_F2") (pintype "bidirectional"))
      (node (ref "U5") (pin "21") (pinfunction "BA1_21") (pintype "input"))
    )
    (net (code "192") (name "SDRAM_CKE") (class "Default")
      (node (ref "U$1") (pin "N1") (pinfunction "IOB42B/LVDS/DQ6_N1") (pintype "bidirectional"))
      (node (ref "U5") (pin "37") (pinfunction "CKE_37") (pintype "input"))
    )
    (net (code "193") (name "SDRAM_CLK") (class "Default")
      (node (ref "U$1") (pin "N2") (pinfunction "IOB41A/DQ6_N2") (pintype "bidirectional"))
      (node (ref "U5") (pin "38") (pinfunction "CLK_38") (pintype "input"))
    )
    (net (code "194") (name "SDRAM_DQ0") (class "Default")
      (node (ref "U$1") (pin "F4") (pinfunction "IOB18A/LVDS/DQ5_F4") (pintype "bidirectional"))
      (node (ref "U5") (pin "2") (pinfunction "DQ0_2") (pintype "bidirectional"))
    )
    (net (code "195") (name "SDRAM_DQ1") (class "Default")
      (node (ref "U$1") (pin "F3") (pinfunction "IOB19A/DQ5_F3") (pintype "bidirectional"))
      (node (ref "U5") (pin "4") (pinfunction "DQ1_4") (pintype "bidirectional"))
    )
    (net (code "196") (name "SDRAM_DQ2") (class "Default")
      (node (ref "U$1") (pin "E3") (pinfunction "IOB12B/LVDS/DQ5_E3") (pintype "bidirectional"))
      (node (ref "U5") (pin "5") (pinfunction "DQ2_5") (pintype "bidirectional"))
    )
    (net (code "197") (name "SDRAM_DQ3") (class "Default")
      (node (ref "U$1") (pin "C5") (pinfunction "IOB2B/LVDS/DQ4_C5") (pintype "bidirectional"))
      (node (ref "U5") (pin "7") (pinfunction "DQ3_7") (pintype "bidirectional"))
    )
    (net (code "198") (name "SDRAM_DQ4") (class "Default")
      (node (ref "U$1") (pin "D3") (pinfunction "IOB9A/DQS4_D3") (pintype "bidirectional"))
      (node (ref "U5") (pin "8") (pinfunction "DQ4_8") (pintype "bidirectional"))
    )
    (net (code "199") (name "SDRAM_DQ5") (class "Default")
      (node (ref "U$1") (pin "C4") (pinfunction "IOL47A/LPLL2_T_FB/LVDS/DQ3_C4") (pintype "bidirectional"))
      (node (ref "U5") (pin "10") (pinfunction "DQ5_10") (pintype "bidirectional"))
    )
    (net (code "200") (name "SDRAM_DQ6") (class "Default")
      (node (ref "U$1") (pin "C2") (pinfunction "IOB8B/LVDS/DQ4_C2") (pintype "bidirectional"))
      (node (ref "U5") (pin "11") (pinfunction "DQ6_11") (pintype "bidirectional"))
    )
    (net (code "201") (name "SDRAM_DQ7") (class "Default")
      (node (ref "U$1") (pin "B3") (pinfunction "IOB13A/DQ5_B3") (pintype "bidirectional"))
      (node (ref "U5") (pin "13") (pinfunction "DQ7_13") (pintype "bidirectional"))
    )
    (net (code "202") (name "SDRAM_DQ8") (class "Default")
      (node (ref "U$1") (pin "P2") (pinfunction "IOB44B/LVDS/DQ6_P2") (pintype "bidirectional"))
      (node (ref "U5") (pin "42") (pinfunction "DQ8_42") (pintype "bidirectional"))
    )
    (net (code "203") (name "SDRAM_DQ9") (class "Default")
      (node (ref "U$1") (pin "R1") (pinfunction "IOB44A/LVDS/DQ6_R1") (pintype "bidirectional"))
      (node (ref "U5") (pin "44") (pinfunction "DQ9_44") (pintype "bidirectional"))
    )
    (net (code "204") (name "SDRAM_DQ10") (class "Default")
      (node (ref "U$1") (pin "J4") (pinfunction "IOB35B/DQ6_J4") (pintype "bidirectional"))
      (node (ref "U5") (pin "45") (pinfunction "DQ10_45") (pintype "bidirectional"))
    )
    (net (code "205") (name "SDRAM_DQ11") (class "Default")
      (node (ref "U$1") (pin "J3") (pinfunction "IOB27B/GCLKC_5/DQ5_J3") (pintype "bidirectional"))
      (node (ref "U5") (pin "47") (pinfunction "DQ11_47") (pintype "bidirectional"))
    )
    (net (code "206") (name "SDRAM_DQ12") (class "Default")
      (node (ref "U$1") (pin "K4") (pinfunction "IOB39A/DQ6_K4") (pintype "bidirectional"))
      (node (ref "U5") (pin "48") (pinfunction "DQ12_48") (pintype "bidirectional"))
    )
    (net (code "207") (name "SDRAM_DQ13") (class "Default")
      (node (ref "U$1") (pin "K3") (pinfunction "IOB36A/LVDS/DQ6_K3") (pintype "bidirectional"))
      (node (ref "U5") (pin "50") (pinfunction "DQ13_50") (pintype "bidirectional"))
    )
    (net (code "208") (name "SDRAM_DQ14") (class "Default")
      (node (ref "U$1") (pin "L4") (pinfunction "IOB40B/LVDS/DQ6_L4") (pintype "bidirectional"))
      (node (ref "U5") (pin "51") (pinfunction "DQ14_51") (pintype "bidirectional"))
    )
    (net (code "209") (name "SDRAM_DQ15") (class "Default")
      (node (ref "U$1") (pin "L3") (pinfunction "IOB38B/LVDS/DQ6_L3") (pintype "bidirectional"))
      (node (ref "U5") (pin "53") (pinfunction "DQ15_53") (pintype "bidirectional"))
    )
    (net (code "210") (name "SDRAM_DQMH") (class "Default")
      (node (ref "U$1") (pin "P1") (pinfunction "IOB41B/DQ6_P1") (pintype "bidirectional"))
      (node (ref "U5") (pin "39") (pinfunction "DQMH_39") (pintype "input"))
    )
    (net (code "211") (name "SDRAM_DQML") (class "Default")
      (node (ref "U$1") (pin "B1") (pinfunction "IOB8A/LVDS/DQ4_B1") (pintype "bidirectional"))
      (node (ref "U5") (pin "15") (pinfunction "DQML_15") (pintype "input"))
    )
    (net (code "212") (name "SDRAM_~{CAS}") (class "Default")
      (node (ref "U$1") (pin "H2") (pinfunction "IOB24B/LVDS/DQ5_H2") (pintype "bidirectional"))
      (node (ref "U5") (pin "17") (pinfunction "~{CAS}_17") (pintype "input"))
    )
    (net (code "213") (name "SDRAM_~{CS}") (class "Default")
      (node (ref "U$1") (pin "G2") (pinfunction "IOB21A/DQS5_G2") (pintype "bidirectional"))
      (node (ref "U5") (pin "19") (pinfunction "~{CS}_19") (pintype "input"))
    )
    (net (code "214") (name "SDRAM_~{RAS}") (class "Default")
      (node (ref "U$1") (pin "G1") (pinfunction "IOB24A/LVDS/DQ5_G1") (pintype "bidirectional"))
      (node (ref "U5") (pin "18") (pinfunction "~{RAS}_18") (pintype "input"))
    )
    (net (code "215") (name "SDRAM_~{WE}") (class "Default")
      (node (ref "U$1") (pin "H1") (pinfunction "IOB32B/LVDS/DQ6_H1") (pintype "bidirectional"))
      (node (ref "U5") (pin "16") (pinfunction "~{WE}_16") (pintype "input"))
    )
    (net (code "216") (name "SD_CLK") (class "Default")
      (node (ref "R48") (pin "1") (pinfunction "1_1") (pintype "passive"))
      (node (ref "U$1") (pin "N10") (pinfunction "IOR27A/GCLKT_2/DQ10_N10") (pintype "bidirectional"))
    )
    (net (code "217") (name "SD_CMD") (class "Default")
      (node (ref "R47") (pin "1") (pinfunction "1_1") (pintype "passive"))
      (node (ref "U$1") (pin "R9") (pinfunction "IOR35A/FASTRD_N/D3/LVDS/DQ9_R9") (pintype "bidirectional"))
    )
    (net (code "218") (name "SD_D0") (class "Default")
      (node (ref "R49") (pin "1") (pinfunction "1_1") (pintype "passive"))
      (node (ref "U$1") (pin "T9") (pinfunction "IOR38A/DIN/LVDS/DQ9_T9") (pintype "bidirectional"))
    )
    (net (code "219") (name "SD_D1") (class "Default")
      (node (ref "R50") (pin "1") (pinfunction "1_1") (pintype "passive"))
      (node (ref "U$1") (pin "P9") (pinfunction "IOR38B/DOUT/LVDS/DQ9_P9") (pintype "bidirectional"))
    )
    (net (code "220") (name "SD_D2") (class "Default")
      (node (ref "R158") (pin "2") (pinfunction "2_2") (pintype "passive"))
      (node (ref "U$1") (pin "R8") (pinfunction "IOR29B/GCLKC_3/LVDS/DQ9_R8") (pintype "bidirectional"))
    )
    (net (code "221") (name "SD_D3") (class "Default")
      (node (ref "R63") (pin "2") (pinfunction "2_2") (pintype "passive"))
      (node (ref "U$1") (pin "T8") (pinfunction "IOR42B/LVDS/DQ9_T8") (pintype "bidirectional"))
    )
    (net (code "222") (name "SD_SW_A") (class "Default")
      (node (ref "J2") (pin "9") (pinfunction "SW_A_9") (pintype "bidirectional"))
      (node (ref "R35") (pin "1") (pinfunction "1_1") (pintype "passive"))
      (node (ref "U$1") (pin "T7") (pinfunction "IOR29A/GCLKT_3/LVDS/DQ9_T7") (pintype "bidirectional"))
    )
    (net (code "223") (name "SF_CLK") (class "Default")
      (node (ref "R55") (pin "1") (pinfunction "1_1") (pintype "passive"))
      (node (ref "U$1") (pin "L10") (pinfunction "IOR34B/MCLK/D4/DQ9_L10") (pintype "bidirectional"))
    )
    (net (code "224") (name "SF_SI") (class "Default")
      (node (ref "R54") (pin "2") (pinfunction "2_2") (pintype "passive"))
      (node (ref "U$1") (pin "R10") (pinfunction "IOR33B/MO/D6/LVDS/DQ9_R10") (pintype "bidirectional"))
    )
    (net (code "225") (name "SF_SO") (class "Default")
      (node (ref "R53") (pin "2") (pinfunction "2_2") (pintype "passive"))
      (node (ref "U$1") (pin "P10") (pinfunction "IOR33A/MI/D7/LVDS/DQ9_P10") (pintype "bidirectional"))
    )
    (net (code "226") (name "SF_~{CS}") (class "Default")
      (node (ref "R56") (pin "1") (pinfunction "1_1") (pintype "passive"))
      (node (ref "U$1") (pin "M9") (pinfunction "IOR34A/MCS_N/D5/DQ9_M9") (pintype "bidirectional"))
    )
    (net (code "227") (name "TX0_N") (class "Default")
      (node (ref "IC1") (pin "4") (pinfunction "MDI_-[0]_4") (pintype "bidirectional"))
      (node (ref "R105") (pin "2") (pinfunction "2_2") (pintype "passive"))
    )
    (net (code "228") (name "TX0_P") (class "Default")
      (node (ref "IC1") (pin "3") (pinfunction "MDI+[0]_3") (pintype "bidirectional"))
      (node (ref "R104") (pin "2") (pinfunction "2_2") (pintype "passive"))
    )
    (net (code "229") (name "TX_N") (class "Default")
      (node (ref "J3") (pin "2") (pinfunction "TD-_2") (pintype "passive"))
      (node (ref "R105") (pin "1") (pinfunction "1_1") (pintype "passive"))
      (node (ref "U$19") (pin "2") (pinfunction "2_2") (pintype "bidirectional"))
    )
    (net (code "230") (name "TX_P") (class "Default")
      (node (ref "J3") (pin "1") (pinfunction "TD+_1") (pintype "passive"))
      (node (ref "R104") (pin "1") (pinfunction "1_1") (pintype "passive"))
      (node (ref "U$19") (pin "1") (pinfunction "1_1") (pintype "bidirectional"))
    )
    (net (code "231") (name "USB_5V") (class "Default")
      (node (ref "C1") (pin "2") (pinfunction "2_2") (pintype "passive"))
      (node (ref "C11") (pin "2") (pinfunction "2_2") (pintype "passive"))
      (node (ref "C12") (pin "2") (pinfunction "2_2") (pintype "passive"))
      (node (ref "C17") (pin "2") (pinfunction "2_2") (pintype "passive"))
      (node (ref "C4") (pin "2") (pinfunction "2_2") (pintype "passive"))
      (node (ref "C7") (pin "2") (pinfunction "2_2") (pintype "passive"))
      (node (ref "C8") (pin "2") (pinfunction "2_2") (pintype "passive"))
      (node (ref "J1") (pin "A4-B9") (pinfunction "1_VBUS_A4-B9") (pintype "power_in"))
      (node (ref "J1") (pin "B4-A9") (pinfunction "2_VBUS_B4-A9") (pintype "power_in"))
      (node (ref "J6") (pin "9") (pinfunction "9_9") (pintype "passive"))
      (node (ref "U$26") (pin "2") (pinfunction "2_2") (pintype "bidirectional"))
      (node (ref "U$3") (pin "1") (pinfunction "EN_1") (pintype "bidirectional"))
      (node (ref "U$3") (pin "4") (pinfunction "IN_4") (pintype "bidirectional"))
      (node (ref "U$4") (pin "1") (pinfunction "EN_1") (pintype "bidirectional"))
      (node (ref "U$4") (pin "4") (pinfunction "IN_4") (pintype "bidirectional"))
      (node (ref "U$5") (pin "1") (pinfunction "EN_1") (pintype "bidirectional"))
      (node (ref "U$5") (pin "4") (pinfunction "IN_4") (pintype "bidirectional"))
      (node (ref "U$6") (pin "1") (pinfunction "1_1") (pintype "passive"))
    )
    (net (code "232") (name "USB_DN") (class "Default")
      (node (ref "D2") (pin "1") (pinfunction "1_1") (pintype "passive"))
      (node (ref "J1") (pin "A7") (pinfunction "DN1_A7") (pintype "passive"))
      (node (ref "J1") (pin "B7") (pinfunction "DN2_B7") (pintype "passive"))
      (node (ref "U1") (pin "7") (pinfunction "DM_7") (pintype "input"))
    )
    (net (code "233") (name "USB_DP") (class "Default")
      (node (ref "D3") (pin "1") (pinfunction "1_1") (pintype "passive"))
      (node (ref "J1") (pin "A6") (pinfunction "DP1_A6") (pintype "passive"))
      (node (ref "J1") (pin "B6") (pinfunction "DP2_B6") (pintype "passive"))
      (node (ref "U1") (pin "8") (pinfunction "DP_8") (pintype "input"))
    )
    (net (code "234") (name "VCCPLLL") (class "Default")
      (node (ref "C51") (pin "2") (pinfunction "2_2") (pintype "passive"))
      (node (ref "C52") (pin "2") (pinfunction "2_2") (pintype "passive"))
      (node (ref "C53") (pin "2") (pinfunction "2_2") (pintype "passive"))
      (node (ref "FB4") (pin "2") (pinfunction "2_2") (pintype "passive"))
      (node (ref "U$1") (pin "G10") (pinfunction "VCCPLLL_G10_G10") (pintype "power_in"))
    )
    (net (code "235") (name "VCCPLLR") (class "Default")
      (node (ref "C54") (pin "2") (pinfunction "2_2") (pintype "passive"))
      (node (ref "C55") (pin "2") (pinfunction "2_2") (pintype "passive"))
      (node (ref "C56") (pin "2") (pinfunction "2_2") (pintype "passive"))
      (node (ref "FB5") (pin "2") (pinfunction "2_2") (pintype "passive"))
      (node (ref "U$1") (pin "K7") (pinfunction "VCCPLLR_K7_K7") (pintype "power_in"))
    )
    (net (code "236") (name "unconnected-(IC1-COL-Pad27)") (class "Default")
      (node (ref "IC1") (pin "27") (pinfunction "COL_27") (pintype "bidirectional"))
    )
    (net (code "237") (name "unconnected-(IC1-RXC-Pad13)") (class "Default")
      (node (ref "IC1") (pin "13") (pinfunction "RXC_13") (pintype "bidirectional"))
    )
    (net (code "238") (name "unconnected-(IC1-RXD[2]{slash}INTB-Pad11)") (class "Default")
      (node (ref "IC1") (pin "11") (pinfunction "RXD[2]/INTB_11") (pintype "bidirectional"))
    )
    (net (code "239") (name "unconnected-(IC1-RXD[3]{slash}CLK_CTL-Pad12)") (class "Default")
      (node (ref "IC1") (pin "12") (pinfunction "RXD[3]/CLK_CTL_12") (pintype "bidirectional"))
    )
    (net (code "240") (name "unconnected-(IC1-TXD[2]-Pad18)") (class "Default")
      (node (ref "IC1") (pin "18") (pinfunction "TXD[2]_18") (pintype "bidirectional"))
    )
    (net (code "241") (name "unconnected-(IC1-TXD[3]-Pad19)") (class "Default")
      (node (ref "IC1") (pin "19") (pinfunction "TXD[3]_19") (pintype "bidirectional"))
    )
    (net (code "242") (name "unconnected-(J1A-SBU1-PadA8)") (class "Default")
      (node (ref "J1") (pin "A8") (pinfunction "SBU1_A8") (pintype "passive"))
    )
    (net (code "243") (name "unconnected-(J1A-SBU2-PadB8)") (class "Default")
      (node (ref "J1") (pin "B8") (pinfunction "SBU2_B8") (pintype "passive"))
    )
    (net (code "244") (name "unconnected-(S1-Pad2)") (class "Default")
      (node (ref "S1") (pin "2") (pinfunction "2_2") (pintype "bidirectional"))
    )
    (net (code "245") (name "unconnected-(S1-Pad3)") (class "Default")
      (node (ref "S1") (pin "3") (pinfunction "3_3") (pintype "bidirectional"))
    )
    (net (code "246") (name "unconnected-(S2-Pad2)") (class "Default")
      (node (ref "S2") (pin "2") (pinfunction "2_2") (pintype "bidirectional"))
    )
    (net (code "247") (name "unconnected-(S2-Pad3)") (class "Default")
      (node (ref "S2") (pin "3") (pinfunction "3_3") (pintype "bidirectional"))
    )
    (net (code "248") (name "unconnected-(S3-Pad2)") (class "Default")
      (node (ref "S3") (pin "2") (pinfunction "2_2") (pintype "bidirectional"))
    )
    (net (code "249") (name "unconnected-(S3-Pad3)") (class "Default")
      (node (ref "S3") (pin "3") (pinfunction "3_3") (pintype "bidirectional"))
    )
    (net (code "250") (name "unconnected-(S4-Pad2)") (class "Default")
      (node (ref "S4") (pin "2") (pinfunction "2_2") (pintype "bidirectional"))
    )
    (net (code "251") (name "unconnected-(S4-Pad3)") (class "Default")
      (node (ref "S4") (pin "3") (pinfunction "3_3") (pintype "bidirectional"))
    )
    (net (code "252") (name "unconnected-(S5-Pad2)") (class "Default")
      (node (ref "S5") (pin "2") (pinfunction "2_2") (pintype "bidirectional"))
    )
    (net (code "253") (name "unconnected-(S5-Pad3)") (class "Default")
      (node (ref "S5") (pin "3") (pinfunction "3_3") (pintype "bidirectional"))
    )
    (net (code "254") (name "unconnected-(U$1A-IOT4A{slash}LVDS{slash}DQ15-PadD16)") (class "Default")
      (node (ref "U$1") (pin "D16") (pinfunction "IOT4A/LVDS/DQ15_D16") (pintype "bidirectional"))
    )
    (net (code "255") (name "unconnected-(U$1A-IOT4B{slash}LVDS{slash}DQ15-PadE14)") (class "Default")
      (node (ref "U$1") (pin "E14") (pinfunction "IOT4B/LVDS/DQ15_E14") (pintype "bidirectional"))
    )
    (net (code "256") (name "unconnected-(U$1A-IOT6A{slash}LVDS{slash}DQ15-PadE16)") (class "Default")
      (node (ref "U$1") (pin "E16") (pinfunction "IOT6A/LVDS/DQ15_E16") (pintype "bidirectional"))
    )
    (net (code "257") (name "unconnected-(U$1A-IOT6B{slash}LVDS{slash}DQ15-PadF15)") (class "Default")
      (node (ref "U$1") (pin "F15") (pinfunction "IOT6B/LVDS/DQ15_F15") (pintype "bidirectional"))
    )
    (net (code "258") (name "unconnected-(U$1A-IOT8A{slash}LVDS{slash}DQ15-PadF13)") (class "Default")
      (node (ref "U$1") (pin "F13") (pinfunction "IOT8A/LVDS/DQ15_F13") (pintype "bidirectional"))
    )
    (net (code "259") (name "unconnected-(U$1A-IOT14A{slash}LVDS{slash}DQ14-PadG11)") (class "Default")
      (node (ref "U$1") (pin "G11") (pinfunction "IOT14A/LVDS/DQ14_G11") (pintype "bidirectional"))
    )
    (net (code "260") (name "unconnected-(U$1A-IOT14B{slash}LVDS{slash}DQ14-PadH12)") (class "Default")
      (node (ref "U$1") (pin "H12") (pinfunction "IOT14B/LVDS/DQ14_H12") (pintype "bidirectional"))
    )
    (net (code "261") (name "unconnected-(U$1A-IOT18B{slash}LVDS{slash}DQ14-PadJ12)") (class "Default")
      (node (ref "U$1") (pin "J12") (pinfunction "IOT18B/LVDS/DQ14_J12") (pintype "bidirectional"))
    )
    (net (code "262") (name "unconnected-(U$1A-IOT27B{slash}GCLKC_0{slash}DQ14-PadJ13)") (class "Default")
      (node (ref "U$1") (pin "J13") (pinfunction "IOT27B/GCLKC_0/DQ14_J13") (pintype "bidirectional"))
    )
    (net (code "263") (name "unconnected-(U$1B-IOT32A{slash}LVDS{slash}DQ13-PadJ11)") (class "Default")
      (node (ref "U$1") (pin "J11") (pinfunction "IOT32A/LVDS/DQ13_J11") (pintype "bidirectional"))
    )
    (net (code "264") (name "unconnected-(U$1B-IOT32B{slash}LVDS{slash}DQ13-PadL12)") (class "Default")
      (node (ref "U$1") (pin "L12") (pinfunction "IOT32B/LVDS/DQ13_L12") (pintype "bidirectional"))
    )
    (net (code "265") (name "unconnected-(U$1B-IOT36A{slash}LVDS{slash}DQ13-PadK13)") (class "Default")
      (node (ref "U$1") (pin "K13") (pinfunction "IOT36A/LVDS/DQ13_K13") (pintype "bidirectional"))
    )
    (net (code "266") (name "unconnected-(U$1B-IOT36B{slash}LVDS{slash}DQ13-PadK12)") (class "Default")
      (node (ref "U$1") (pin "K12") (pinfunction "IOT36B/LVDS/DQ13_K12") (pintype "bidirectional"))
    )
    (net (code "267") (name "unconnected-(U$1B-IOT38A{slash}LVDS{slash}DQ13-PadK11)") (class "Default")
      (node (ref "U$1") (pin "K11") (pinfunction "IOT38A/LVDS/DQ13_K11") (pintype "bidirectional"))
    )
    (net (code "268") (name "unconnected-(U$1B-IOT38B{slash}LVDS{slash}DQ13-PadL13)") (class "Default")
      (node (ref "U$1") (pin "L13") (pinfunction "IOT38B/LVDS/DQ13_L13") (pintype "bidirectional"))
    )
    (net (code "269") (name "unconnected-(U$1B-IOT44A{slash}LVDS{slash}DQ13-PadD14)") (class "Default")
      (node (ref "U$1") (pin "D14") (pinfunction "IOT44A/LVDS/DQ13_D14") (pintype "bidirectional"))
    )
    (net (code "270") (name "unconnected-(U$1B-IOT44B{slash}LVDS{slash}DQ13-PadE15)") (class "Default")
      (node (ref "U$1") (pin "E15") (pinfunction "IOT44B/LVDS/DQ13_E15") (pintype "bidirectional"))
    )
    (net (code "271") (name "unconnected-(U$1B-IOT52B{slash}LVDS{slash}DQ12-PadN14)") (class "Default")
      (node (ref "U$1") (pin "N14") (pinfunction "IOT52B/LVDS/DQ12_N14") (pintype "bidirectional"))
    )
    (net (code "272") (name "unconnected-(U$1B-IOT54A{slash}LVDS{slash}DQ12-PadP15)") (class "Default")
      (node (ref "U$1") (pin "P15") (pinfunction "IOT54A/LVDS/DQ12_P15") (pintype "bidirectional"))
    )
    (net (code "273") (name "unconnected-(U$1B-IOT54B{slash}LVDS{slash}DQ12-PadR16)") (class "Default")
      (node (ref "U$1") (pin "R16") (pinfunction "IOT54B/LVDS/DQ12_R16") (pintype "bidirectional"))
    )
    (net (code "274") (name "unconnected-(U$1C-IOR8A{slash}RPLL1_T_FB{slash}LVDS{slash}DQ11-PadP12)") (class "Default")
      (node (ref "U$1") (pin "P12") (pinfunction "IOR8A/RPLL1_T_FB/LVDS/DQ11_P12") (pintype "bidirectional"))
    )
    (net (code "275") (name "unconnected-(U$1C-IOR11B{slash}LVDS{slash}DQ10-PadP13)") (class "Default")
      (node (ref "U$1") (pin "P13") (pinfunction "IOR11B/LVDS/DQ10_P13") (pintype "bidirectional"))
    )
    (net (code "276") (name "unconnected-(U$1C-IOR17A{slash}LVDS{slash}DQ10-PadR11)") (class "Default")
      (node (ref "U$1") (pin "R11") (pinfunction "IOR17A/LVDS/DQ10_R11") (pintype "bidirectional"))
    )
    (net (code "277") (name "unconnected-(U$1C-IOR17B{slash}LVDS{slash}DQ10-PadT12)") (class "Default")
      (node (ref "U$1") (pin "T12") (pinfunction "IOR17B/LVDS/DQ10_T12") (pintype "bidirectional"))
    )
    (net (code "278") (name "unconnected-(U$1C-IOR22A{slash}LVDS{slash}DQS10-PadM10)") (class "Default")
      (node (ref "U$1") (pin "M10") (pinfunction "IOR22A/LVDS/DQS10_M10") (pintype "bidirectional"))
    )
    (net (code "279") (name "unconnected-(U$1C-IOR22B{slash}LVDS{slash}DQS10-PadN11)") (class "Default")
      (node (ref "U$1") (pin "N11") (pinfunction "IOR22B/LVDS/DQS10_N11") (pintype "bidirectional"))
    )
    (net (code "280") (name "unconnected-(U$1C-IOR24A{slash}LVDS{slash}DQ10-PadT11)") (class "Default")
      (node (ref "U$1") (pin "T11") (pinfunction "IOR24A/LVDS/DQ10_T11") (pintype "bidirectional"))
    )
    (net (code "281") (name "unconnected-(U$1C-IOR24B{slash}LVDS{slash}DQ10-PadP11)") (class "Default")
      (node (ref "U$1") (pin "P11") (pinfunction "IOR24B/LVDS/DQ10_P11") (pintype "bidirectional"))
    )
    (net (code "282") (name "unconnected-(U$1C-IOR27B{slash}GCLKC_2{slash}DQ10-PadM11)") (class "Default")
      (node (ref "U$1") (pin "M11") (pinfunction "IOR27B/GCLKC_2/DQ10_M11") (pintype "bidirectional"))
    )
    (net (code "283") (name "unconnected-(U$1D-IOR36A{slash}D1{slash}DQS9-PadM8)") (class "Default")
      (node (ref "U$1") (pin "M8") (pinfunction "IOR36A/D1/DQS9_M8") (pintype "bidirectional"))
    )
    (net (code "284") (name "unconnected-(U$1D-IOR36B{slash}D0{slash}DQS9-PadN9)") (class "Default")
      (node (ref "U$1") (pin "N9") (pinfunction "IOR36B/D0/DQS9_N9") (pintype "bidirectional"))
    )
    (net (code "285") (name "unconnected-(U$1D-IOR39A{slash}SCLK{slash}DQ9-PadC10)") (class "Default")
      (node (ref "U$1") (pin "C10") (pinfunction "IOR39A/SCLK/DQ9_C10") (pintype "bidirectional"))
    )
    (net (code "286") (name "unconnected-(U$1D-IOR40A{slash}LVDS{slash}DQ9-PadN8)") (class "Default")
      (node (ref "U$1") (pin "N8") (pinfunction "IOR40A/LVDS/DQ9_N8") (pintype "bidirectional"))
    )
    (net (code "287") (name "unconnected-(U$1D-IOR40B{slash}LVDS{slash}DQ9-PadL9)") (class "Default")
      (node (ref "U$1") (pin "L9") (pinfunction "IOR40B/LVDS/DQ9_L9") (pintype "bidirectional"))
    )
    (net (code "288") (name "unconnected-(U$1D-IOR42A{slash}LVDS{slash}DQ9-PadP8)") (class "Default")
      (node (ref "U$1") (pin "P8") (pinfunction "IOR42A/LVDS/DQ9_P8") (pintype "bidirectional"))
    )
    (net (code "289") (name "unconnected-(U$1D-IOR44A{slash}LVDS{slash}DQ9-PadM6)") (class "Default")
      (node (ref "U$1") (pin "M6") (pinfunction "IOR44A/LVDS/DQ9_M6") (pintype "bidirectional"))
    )
    (net (code "290") (name "unconnected-(U$1D-IOR44B{slash}LVDS{slash}DQ9-PadL8)") (class "Default")
      (node (ref "U$1") (pin "L8") (pinfunction "IOR44B/LVDS/DQ9_L8") (pintype "bidirectional"))
    )
    (net (code "291") (name "unconnected-(U$1D-IOR47A{slash}RPLL2_T_FB{slash}LVDS{slash}DQ8-PadM7)") (class "Default")
      (node (ref "U$1") (pin "M7") (pinfunction "IOR47A/RPLL2_T_FB/LVDS/DQ8_M7") (pintype "bidirectional"))
    )
    (net (code "292") (name "unconnected-(U$1D-IOR47B{slash}RPLL2_C_FB{slash}LVDS{slash}DQ8-PadN7)") (class "Default")
      (node (ref "U$1") (pin "N7") (pinfunction "IOR47B/RPLL2_C_FB/LVDS/DQ8_N7") (pintype "bidirectional"))
    )
    (net (code "293") (name "unconnected-(U$1D-IOR49A{slash}LVDS{slash}DQ8-PadR7)") (class "Default")
      (node (ref "U$1") (pin "R7") (pinfunction "IOR49A/LVDS/DQ8_R7") (pintype "bidirectional"))
    )
    (net (code "294") (name "unconnected-(U$1D-IOR49B{slash}LVDS{slash}DQ8-PadP7)") (class "Default")
      (node (ref "U$1") (pin "P7") (pinfunction "IOR49B/LVDS/DQ8_P7") (pintype "bidirectional"))
    )
    (net (code "295") (name "unconnected-(U$1D-IOR51A{slash}LVDS{slash}DQ8-PadN6)") (class "Default")
      (node (ref "U$1") (pin "N6") (pinfunction "IOR51A/LVDS/DQ8_N6") (pintype "bidirectional"))
    )
    (net (code "296") (name "unconnected-(U$1D-IOR53A{slash}LVDS{slash}DQ8-PadP6)") (class "Default")
      (node (ref "U$1") (pin "P6") (pinfunction "IOR53A/LVDS/DQ8_P6") (pintype "bidirectional"))
    )
    (net (code "297") (name "unconnected-(U$1D-IOR53B{slash}LVDS{slash}DQ8-PadT6)") (class "Default")
      (node (ref "U$1") (pin "T6") (pinfunction "IOR53B/LVDS/DQ8_T6") (pintype "bidirectional"))
    )
    (net (code "298") (name "unconnected-(U$1E-IOB35A{slash}DQ6-PadH5)") (class "Default")
      (node (ref "U$1") (pin "H5") (pinfunction "IOB35A/DQ6_H5") (pintype "bidirectional"))
    )
    (net (code "299") (name "unconnected-(U$1E-IOB37A{slash}DQS6-PadJ5)") (class "Default")
      (node (ref "U$1") (pin "J5") (pinfunction "IOB37A/DQS6_J5") (pintype "bidirectional"))
    )
    (net (code "300") (name "unconnected-(U$1E-IOB37B{slash}DQS6-PadK6)") (class "Default")
      (node (ref "U$1") (pin "K6") (pinfunction "IOB37B/DQS6_K6") (pintype "bidirectional"))
    )
    (net (code "301") (name "unconnected-(U$1E-IOB39B{slash}DQ6-PadL5)") (class "Default")
      (node (ref "U$1") (pin "L5") (pinfunction "IOB39B/DQ6_L5") (pintype "bidirectional"))
    )
    (net (code "302") (name "unconnected-(U$1E-IOB40A{slash}LVDS{slash}DQ6-PadK5)") (class "Default")
      (node (ref "U$1") (pin "K5") (pinfunction "IOB40A/LVDS/DQ6_K5") (pintype "bidirectional"))
    )
    (net (code "303") (name "unconnected-(U$1E-IOB42A{slash}LVDS{slash}DQ6-PadM3)") (class "Default")
      (node (ref "U$1") (pin "M3") (pinfunction "IOB42A/LVDS/DQ6_M3") (pintype "bidirectional"))
    )
    (net (code "304") (name "unconnected-(U$1E-IOB43B{slash}DQ6-PadN3)") (class "Default")
      (node (ref "U$1") (pin "N3") (pinfunction "IOB43B/DQ6_N3") (pintype "bidirectional"))
    )
    (net (code "305") (name "unconnected-(U$1E-IOB45A{slash}DQ6-PadP4)") (class "Default")
      (node (ref "U$1") (pin "P4") (pinfunction "IOB45A/DQ6_P4") (pintype "bidirectional"))
    )
    (net (code "306") (name "unconnected-(U$1E-IOB45B{slash}DQ6-PadT4)") (class "Default")
      (node (ref "U$1") (pin "T4") (pinfunction "IOB45B/DQ6_T4") (pintype "bidirectional"))
    )
    (net (code "307") (name "unconnected-(U$1E-IOB48A{slash}LVDS{slash}DQS7-PadR3)") (class "Default")
      (node (ref "U$1") (pin "R3") (pinfunction "IOB48A/LVDS/DQS7_R3") (pintype "bidirectional"))
    )
    (net (code "308") (name "unconnected-(U$1E-IOB48B{slash}LVDS{slash}DQS7-PadT2)") (class "Default")
      (node (ref "U$1") (pin "T2") (pinfunction "IOB48B/LVDS/DQS7_T2") (pintype "bidirectional"))
    )
    (net (code "309") (name "unconnected-(U$1E-IOB50A{slash}LVDS{slash}DQ7-PadP5)") (class "Default")
      (node (ref "U$1") (pin "P5") (pinfunction "IOB50A/LVDS/DQ7_P5") (pintype "bidirectional"))
    )
    (net (code "310") (name "unconnected-(U$1E-IOB50B{slash}LVDS{slash}DQ7-PadR5)") (class "Default")
      (node (ref "U$1") (pin "R5") (pinfunction "IOB50B/LVDS/DQ7_R5") (pintype "bidirectional"))
    )
    (net (code "311") (name "unconnected-(U$1E-IOB52A{slash}LVDS{slash}DQ7-PadR4)") (class "Default")
      (node (ref "U$1") (pin "R4") (pinfunction "IOB52A/LVDS/DQ7_R4") (pintype "bidirectional"))
    )
    (net (code "312") (name "unconnected-(U$1E-IOB52B{slash}LVDS{slash}DQ7-PadT3)") (class "Default")
      (node (ref "U$1") (pin "T3") (pinfunction "IOB52B/LVDS/DQ7_T3") (pintype "bidirectional"))
    )
    (net (code "313") (name "unconnected-(U$1E-IOB54A{slash}LVDS{slash}DQ7-PadR6)") (class "Default")
      (node (ref "U$1") (pin "R6") (pinfunction "IOB54A/LVDS/DQ7_R6") (pintype "bidirectional"))
    )
    (net (code "314") (name "unconnected-(U$1E-IOB54B{slash}LVDS{slash}DQ7-PadT5)") (class "Default")
      (node (ref "U$1") (pin "T5") (pinfunction "IOB54B/LVDS/DQ7_T5") (pintype "bidirectional"))
    )
    (net (code "315") (name "unconnected-(U$1F-IOB2A{slash}LVDS{slash}DQ4-PadA4)") (class "Default")
      (node (ref "U$1") (pin "A4") (pinfunction "IOB2A/LVDS/DQ4_A4") (pintype "bidirectional"))
    )
    (net (code "316") (name "unconnected-(U$1F-IOB3A{slash}DQ4-PadD6)") (class "Default")
      (node (ref "U$1") (pin "D6") (pinfunction "IOB3A/DQ4_D6") (pintype "bidirectional"))
    )
    (net (code "317") (name "unconnected-(U$1F-IOB3B{slash}DQ4-PadE7)") (class "Default")
      (node (ref "U$1") (pin "E7") (pinfunction "IOB3B/DQ4_E7") (pintype "bidirectional"))
    )
    (net (code "318") (name "unconnected-(U$1F-IOB4A{slash}LVDS{slash}DQ4-PadA3)") (class "Default")
      (node (ref "U$1") (pin "A3") (pinfunction "IOB4A/LVDS/DQ4_A3") (pintype "bidirectional"))
    )
    (net (code "319") (name "unconnected-(U$1F-IOB4B{slash}LVDS{slash}DQ4-PadB4)") (class "Default")
      (node (ref "U$1") (pin "B4") (pinfunction "IOB4B/LVDS/DQ4_B4") (pintype "bidirectional"))
    )
    (net (code "320") (name "unconnected-(U$1F-IOB7A{slash}DQ4-PadA5)") (class "Default")
      (node (ref "U$1") (pin "A5") (pinfunction "IOB7A/DQ4_A5") (pintype "bidirectional"))
    )
    (net (code "321") (name "unconnected-(U$1F-IOB7B{slash}DQ4-PadB6)") (class "Default")
      (node (ref "U$1") (pin "B6") (pinfunction "IOB7B/DQ4_B6") (pintype "bidirectional"))
    )
    (net (code "322") (name "unconnected-(U$1F-IOB13B{slash}DQ5-PadA2)") (class "Default")
      (node (ref "U$1") (pin "A2") (pinfunction "IOB13B/DQ5_A2") (pintype "bidirectional"))
    )
    (net (code "323") (name "unconnected-(U$1F-IOB18B{slash}LVDS{slash}DQ5-PadG6)") (class "Default")
      (node (ref "U$1") (pin "G6") (pinfunction "IOB18B/LVDS/DQ5_G6") (pintype "bidirectional"))
    )
    (net (code "324") (name "unconnected-(U$1F-IOB20A{slash}LVDS{slash}DQ5-PadG5)") (class "Default")
      (node (ref "U$1") (pin "G5") (pinfunction "IOB20A/LVDS/DQ5_G5") (pintype "bidirectional"))
    )
    (net (code "325") (name "unconnected-(U$1F-IOB22A{slash}LVDS{slash}DQ5-PadF5)") (class "Default")
      (node (ref "U$1") (pin "F5") (pinfunction "IOB22A/LVDS/DQ5_F5") (pintype "bidirectional"))
    )
    (net (code "326") (name "unconnected-(U$1F-IOB22B{slash}LVDS{slash}DQ5-PadH6)") (class "Default")
      (node (ref "U$1") (pin "H6") (pinfunction "IOB22B/LVDS/DQ5_H6") (pintype "bidirectional"))
    )
    (net (code "327") (name "unconnected-(U$1F-IOB26B{slash}LVDS{slash}DQ5-PadJ6)") (class "Default")
      (node (ref "U$1") (pin "J6") (pinfunction "IOB26B/LVDS/DQ5_J6") (pintype "bidirectional"))
    )
    (net (code "328") (name "unconnected-(U$1G-IOL31A{slash}LVDS{slash}DQ2-PadF9)") (class "Default")
      (node (ref "U$1") (pin "F9") (pinfunction "IOL31A/LVDS/DQ2_F9") (pintype "bidirectional"))
    )
    (net (code "329") (name "unconnected-(U$1G-IOL31B{slash}LVDS{slash}DQ2-PadE11)") (class "Default")
      (node (ref "U$1") (pin "E11") (pinfunction "IOL31B/LVDS/DQ2_E11") (pintype "bidirectional"))
    )
    (net (code "330") (name "unconnected-(U$1G-IOL35A{slash}LVDS{slash}DQ2-PadF8)") (class "Default")
      (node (ref "U$1") (pin "F8") (pinfunction "IOL35A/LVDS/DQ2_F8") (pintype "bidirectional"))
    )
    (net (code "331") (name "unconnected-(U$1G-IOL38B{slash}LVDS{slash}DQ2-PadE9)") (class "Default")
      (node (ref "U$1") (pin "E9") (pinfunction "IOL38B/LVDS/DQ2_E9") (pintype "bidirectional"))
    )
    (net (code "332") (name "unconnected-(U$1G-IOL40A{slash}LVDS{slash}DQ2-PadB7)") (class "Default")
      (node (ref "U$1") (pin "B7") (pinfunction "IOL40A/LVDS/DQ2_B7") (pintype "bidirectional"))
    )
    (net (code "333") (name "unconnected-(U$1G-IOL40B{slash}LVDS{slash}DQ2-PadC7)") (class "Default")
      (node (ref "U$1") (pin "C7") (pinfunction "IOL40B/LVDS/DQ2_C7") (pintype "bidirectional"))
    )
    (net (code "334") (name "unconnected-(U$1G-IOL45A{slash}LPLL2_T_IN{slash}DQ2-PadF7)") (class "Default")
      (node (ref "U$1") (pin "F7") (pinfunction "IOL45A/LPLL2_T_IN/DQ2_F7") (pintype "bidirectional"))
    )
    (net (code "335") (name "unconnected-(U$1G-IOL45B{slash}LPLL2_C_IN{slash}DQ2-PadE8)") (class "Default")
      (node (ref "U$1") (pin "E8") (pinfunction "IOL45B/LPLL2_C_IN/DQ2_E8") (pintype "bidirectional"))
    )
    (net (code "336") (name "unconnected-(U$1G-IOL47B{slash}LPLL2_C_FB{slash}LVDS{slash}DQ3-PadB5)") (class "Default")
      (node (ref "U$1") (pin "B5") (pinfunction "IOL47B/LPLL2_C_FB/LVDS/DQ3_B5") (pintype "bidirectional"))
    )
    (net (code "337") (name "unconnected-(U$1G-IOL53A{slash}LVDS{slash}DQ3-PadE6)") (class "Default")
      (node (ref "U$1") (pin "E6") (pinfunction "IOL53A/LVDS/DQ3_E6") (pintype "bidirectional"))
    )
    (net (code "338") (name "unconnected-(U$1G-IOL53B{slash}LVDS{slash}DQ3-PadD7)") (class "Default")
      (node (ref "U$1") (pin "D7") (pinfunction "IOL53B/LVDS/DQ3_D7") (pintype "bidirectional"))
    )
    (net (code "339") (name "unconnected-(U$1H-IOL2A{slash}LVDS{slash}DQ0-PadB14)") (class "Default")
      (node (ref "U$1") (pin "B14") (pinfunction "IOL2A/LVDS/DQ0_B14") (pintype "bidirectional"))
    )
    (net (code "340") (name "unconnected-(U$1H-IOL7A{slash}LPLL1_T_IN{slash}DQ0-PadC12)") (class "Default")
      (node (ref "U$1") (pin "C12") (pinfunction "IOL7A/LPLL1_T_IN/DQ0_C12") (pintype "bidirectional"))
    )
    (net (code "341") (name "unconnected-(U$1H-IOL11A{slash}LVDS{slash}DQ1-PadF10)") (class "Default")
      (node (ref "U$1") (pin "F10") (pinfunction "IOL11A/LVDS/DQ1_F10") (pintype "bidirectional"))
    )
    (net (code "342") (name "unconnected-(U$1H-IOL15B{slash}LVDS{slash}DQ1-PadC11)") (class "Default")
      (node (ref "U$1") (pin "C11") (pinfunction "IOL15B/LVDS/DQ1_C11") (pintype "bidirectional"))
    )
    (net (code "343") (name "unconnected-(U$1H-IOL17B{slash}LVDS{slash}DQ1-PadE10)") (class "Default")
      (node (ref "U$1") (pin "E10") (pinfunction "IOL17B/LVDS/DQ1_E10") (pintype "bidirectional"))
    )
    (net (code "344") (name "unconnected-(U$1H-IOL22A{slash}LVDS{slash}DQS1-PadD11)") (class "Default")
      (node (ref "U$1") (pin "D11") (pinfunction "IOL22A/LVDS/DQS1_D11") (pintype "bidirectional"))
    )
    (net (code "345") (name "unconnected-(U$1H-IOL27B{slash}GCLKC_7{slash}DQ1-PadC9)") (class "Default")
      (node (ref "U$1") (pin "C9") (pinfunction "IOL27B/GCLKC_7/DQ1_C9") (pintype "bidirectional"))
    )
    (net (code "346") (name "unconnected-(U$23-NC{slash}STROBE-Pad1)") (class "Default")
      (node (ref "U$23") (pin "1") (pinfunction "NC/STROBE_1") (pintype "bidirectional"))
    )
    (net (code "347") (name "unconnected-(U$23-Y0{slash}AFGND-Pad24)") (class "Default")
      (node (ref "U$23") (pin "24") (pinfunction "Y0/AFGND_24") (pintype "bidirectional"))
    )
    (net (code "348") (name "unconnected-(U$23-Y1{slash}AFVCC-Pad23)") (class "Default")
      (node (ref "U$23") (pin "23") (pinfunction "Y1/AFVCC_23") (pintype "bidirectional"))
    )
    (net (code "349") (name "unconnected-(U$27-SH-PadP$20)") (class "Default")
      (node (ref "U$27") (pin "P$20") (pinfunction "SH_P$20") (pintype "bidirectional"))
    )
    (net (code "350") (name "unconnected-(U$27-UTIL-Pad14)") (class "Default")
      (node (ref "U$27") (pin "14") (pinfunction "UTIL_14") (pintype "bidirectional"))
    )
    (net (code "351") (name "unconnected-(U1-ACBUS0-Pad26)") (class "Default")
      (node (ref "U1") (pin "26") (pinfunction "ACBUS0_26") (pintype "bidirectional"))
    )
    (net (code "352") (name "unconnected-(U1-ACBUS1-Pad27)") (class "Default")
      (node (ref "U1") (pin "27") (pinfunction "ACBUS1_27") (pintype "bidirectional"))
    )
    (net (code "353") (name "unconnected-(U1-ACBUS2-Pad28)") (class "Default")
      (node (ref "U1") (pin "28") (pinfunction "ACBUS2_28") (pintype "bidirectional"))
    )
    (net (code "354") (name "unconnected-(U1-ACBUS3-Pad29)") (class "Default")
      (node (ref "U1") (pin "29") (pinfunction "ACBUS3_29") (pintype "bidirectional"))
    )
    (net (code "355") (name "unconnected-(U1-ACBUS4-Pad30)") (class "Default")
      (node (ref "U1") (pin "30") (pinfunction "ACBUS4_30") (pintype "bidirectional"))
    )
    (net (code "356") (name "unconnected-(U1-ACBUS5-Pad32)") (class "Default")
      (node (ref "U1") (pin "32") (pinfunction "ACBUS5_32") (pintype "bidirectional"))
    )
    (net (code "357") (name "unconnected-(U1-ACBUS6-Pad33)") (class "Default")
      (node (ref "U1") (pin "33") (pinfunction "ACBUS6_33") (pintype "bidirectional"))
    )
    (net (code "358") (name "unconnected-(U1-ACBUS7-Pad34)") (class "Default")
      (node (ref "U1") (pin "34") (pinfunction "ACBUS7_34") (pintype "bidirectional"))
    )
    (net (code "359") (name "unconnected-(U1-ADBUS4-Pad21)") (class "Default")
      (node (ref "U1") (pin "21") (pinfunction "ADBUS4_21") (pintype "bidirectional"))
    )
    (net (code "360") (name "unconnected-(U1-ADBUS5-Pad22)") (class "Default")
      (node (ref "U1") (pin "22") (pinfunction "ADBUS5_22") (pintype "bidirectional"))
    )
    (net (code "361") (name "unconnected-(U1-ADBUS6-Pad23)") (class "Default")
      (node (ref "U1") (pin "23") (pinfunction "ADBUS6_23") (pintype "bidirectional"))
    )
    (net (code "362") (name "unconnected-(U1-ADBUS7-Pad24)") (class "Default")
      (node (ref "U1") (pin "24") (pinfunction "ADBUS7_24") (pintype "bidirectional"))
    )
    (net (code "363") (name "unconnected-(U1-BCBUS0-Pad48)") (class "Default")
      (node (ref "U1") (pin "48") (pinfunction "BCBUS0_48") (pintype "bidirectional"))
    )
    (net (code "364") (name "unconnected-(U1-BCBUS1-Pad52)") (class "Default")
      (node (ref "U1") (pin "52") (pinfunction "BCBUS1_52") (pintype "bidirectional"))
    )
    (net (code "365") (name "unconnected-(U1-BCBUS2-Pad53)") (class "Default")
      (node (ref "U1") (pin "53") (pinfunction "BCBUS2_53") (pintype "bidirectional"))
    )
    (net (code "366") (name "unconnected-(U1-BCBUS3-Pad54)") (class "Default")
      (node (ref "U1") (pin "54") (pinfunction "BCBUS3_54") (pintype "bidirectional"))
    )
    (net (code "367") (name "unconnected-(U1-BCBUS4-Pad55)") (class "Default")
      (node (ref "U1") (pin "55") (pinfunction "BCBUS4_55") (pintype "bidirectional"))
    )
    (net (code "368") (name "unconnected-(U1-BCBUS5-Pad57)") (class "Default")
      (node (ref "U1") (pin "57") (pinfunction "BCBUS5_57") (pintype "bidirectional"))
    )
    (net (code "369") (name "unconnected-(U1-BCBUS6-Pad58)") (class "Default")
      (node (ref "U1") (pin "58") (pinfunction "BCBUS6_58") (pintype "bidirectional"))
    )
    (net (code "370") (name "unconnected-(U1-BCBUS7-Pad59)") (class "Default")
      (node (ref "U1") (pin "59") (pinfunction "BCBUS7_59") (pintype "bidirectional"))
    )
    (net (code "371") (name "unconnected-(U1-BDBUS0-Pad38)") (class "Default")
      (node (ref "U1") (pin "38") (pinfunction "BDBUS0_38") (pintype "bidirectional"))
    )
    (net (code "372") (name "unconnected-(U1-BDBUS1-Pad39)") (class "Default")
      (node (ref "U1") (pin "39") (pinfunction "BDBUS1_39") (pintype "bidirectional"))
    )
    (net (code "373") (name "unconnected-(U1-BDBUS2-Pad40)") (class "Default")
      (node (ref "U1") (pin "40") (pinfunction "BDBUS2_40") (pintype "bidirectional"))
    )
    (net (code "374") (name "unconnected-(U1-BDBUS3-Pad41)") (class "Default")
      (node (ref "U1") (pin "41") (pinfunction "BDBUS3_41") (pintype "bidirectional"))
    )
    (net (code "375") (name "unconnected-(U1-BDBUS4-Pad43)") (class "Default")
      (node (ref "U1") (pin "43") (pinfunction "BDBUS4_43") (pintype "bidirectional"))
    )
    (net (code "376") (name "unconnected-(U1-BDBUS5-Pad44)") (class "Default")
      (node (ref "U1") (pin "44") (pinfunction "BDBUS5_44") (pintype "bidirectional"))
    )
    (net (code "377") (name "unconnected-(U1-BDBUS6-Pad45)") (class "Default")
      (node (ref "U1") (pin "45") (pinfunction "BDBUS6_45") (pintype "bidirectional"))
    )
    (net (code "378") (name "unconnected-(U1-BDBUS7-Pad46)") (class "Default")
      (node (ref "U1") (pin "46") (pinfunction "BDBUS7_46") (pintype "bidirectional"))
    )
    (net (code "379") (name "unconnected-(U1-EECLK-Pad62)") (class "Default")
      (node (ref "U1") (pin "62") (pinfunction "EECLK_62") (pintype "output"))
    )
    (net (code "380") (name "unconnected-(U1-EECS-Pad63)") (class "Default")
      (node (ref "U1") (pin "63") (pinfunction "EECS_63") (pintype "bidirectional"))
    )
    (net (code "381") (name "unconnected-(U1-EEDATA-Pad61)") (class "Default")
      (node (ref "U1") (pin "61") (pinfunction "EEDATA_61") (pintype "bidirectional"))
    )
    (net (code "382") (name "unconnected-(U1-PWREN#-Pad60)") (class "Default")
      (node (ref "U1") (pin "60") (pinfunction "PWREN#_60") (pintype "output"))
    )
    (net (code "383") (name "unconnected-(U1-SUSPEND#-Pad36)") (class "Default")
      (node (ref "U1") (pin "36") (pinfunction "SUSPEND#_36") (pintype "output"))
    )
    (net (code "384") (name "unconnected-(U5B-NC-Pad40)") (class "Default")
      (node (ref "U5") (pin "40") (pinfunction "NC_40") (pintype "passive"))
    )
  )
)
